# pandashield.net
KiCad netlist of a schematic drawn in EAGLE
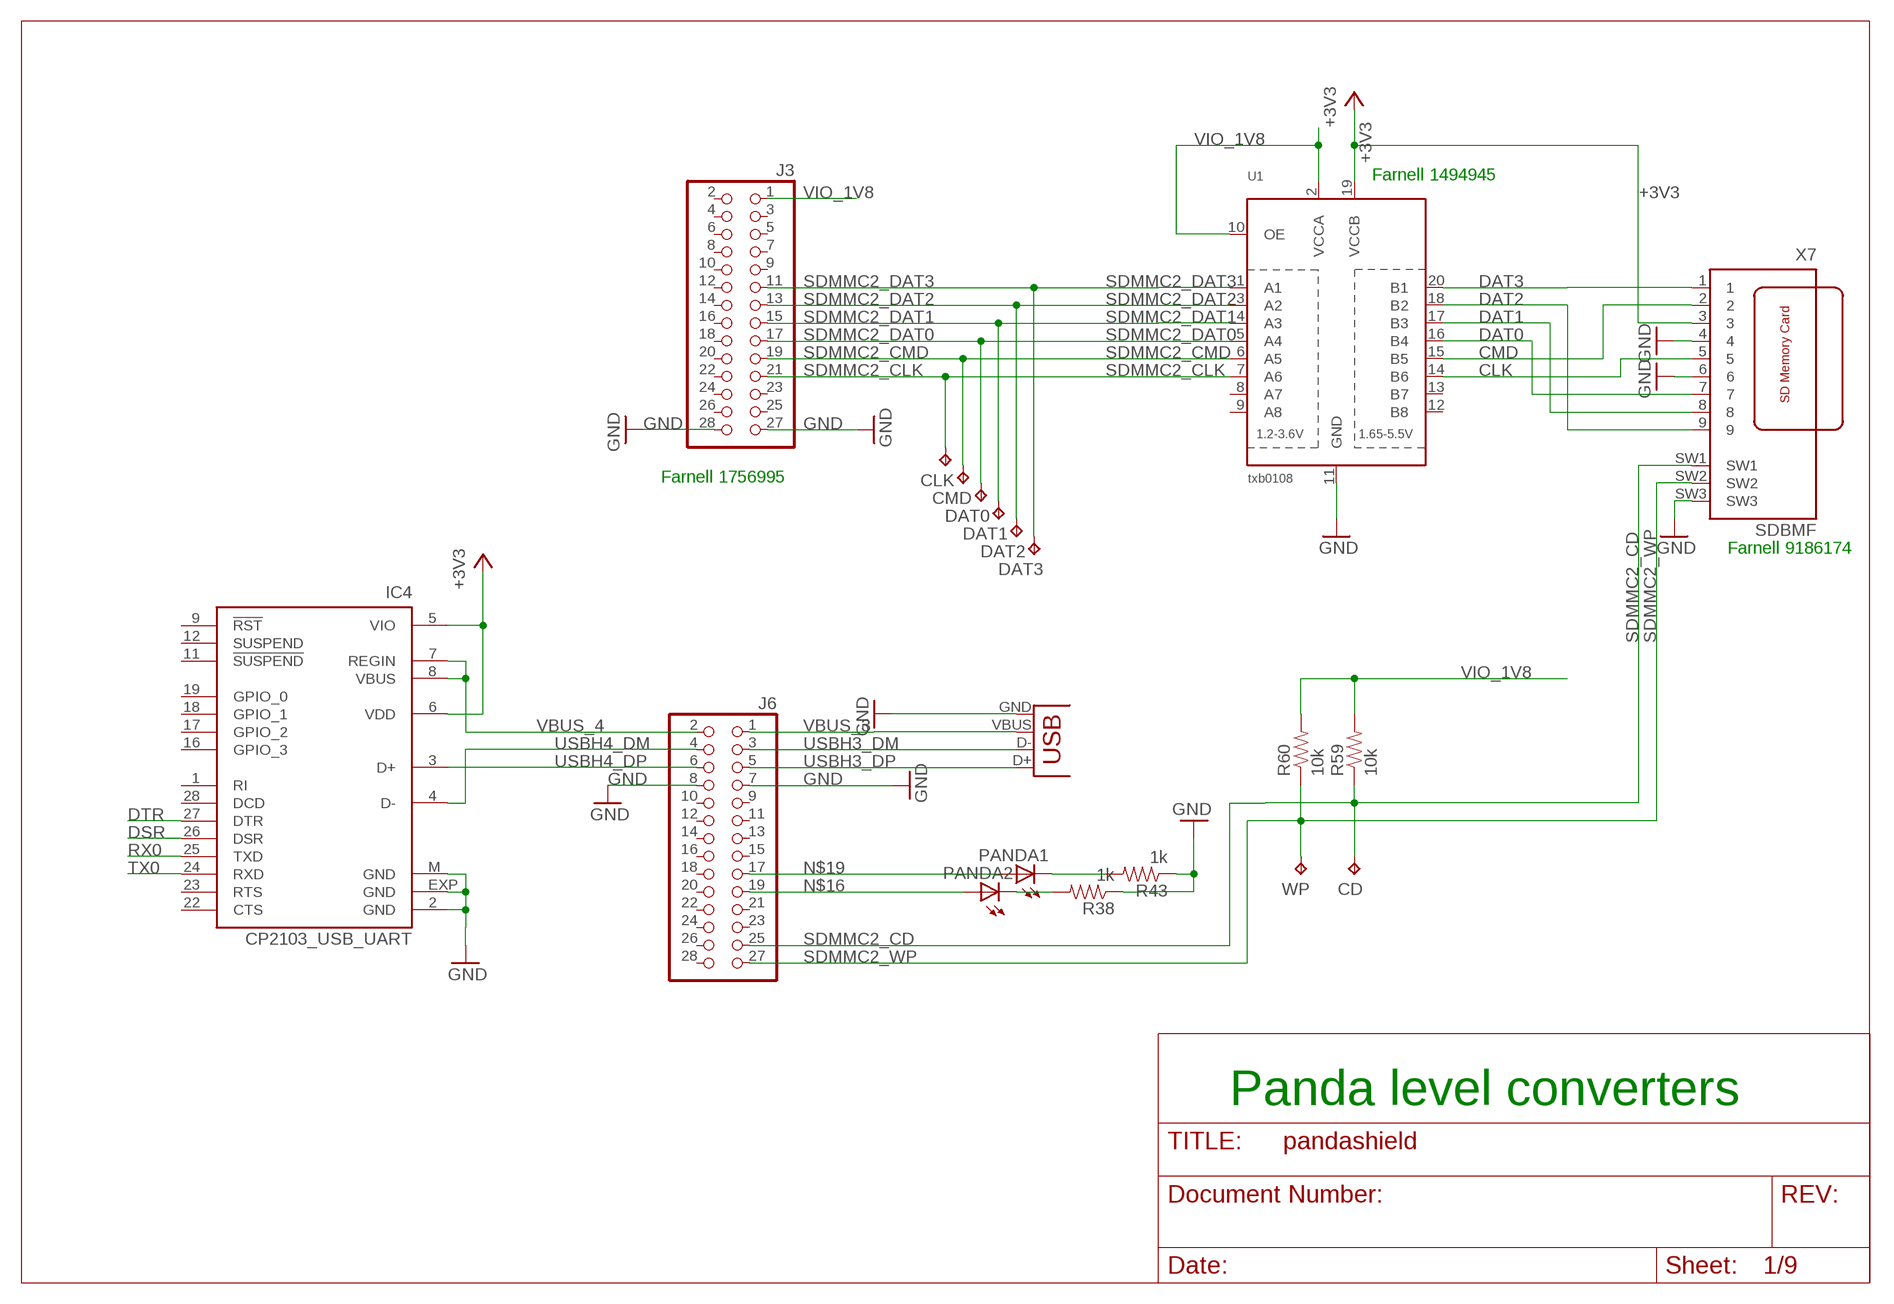
[diagram p0: schematic, sheet 1]
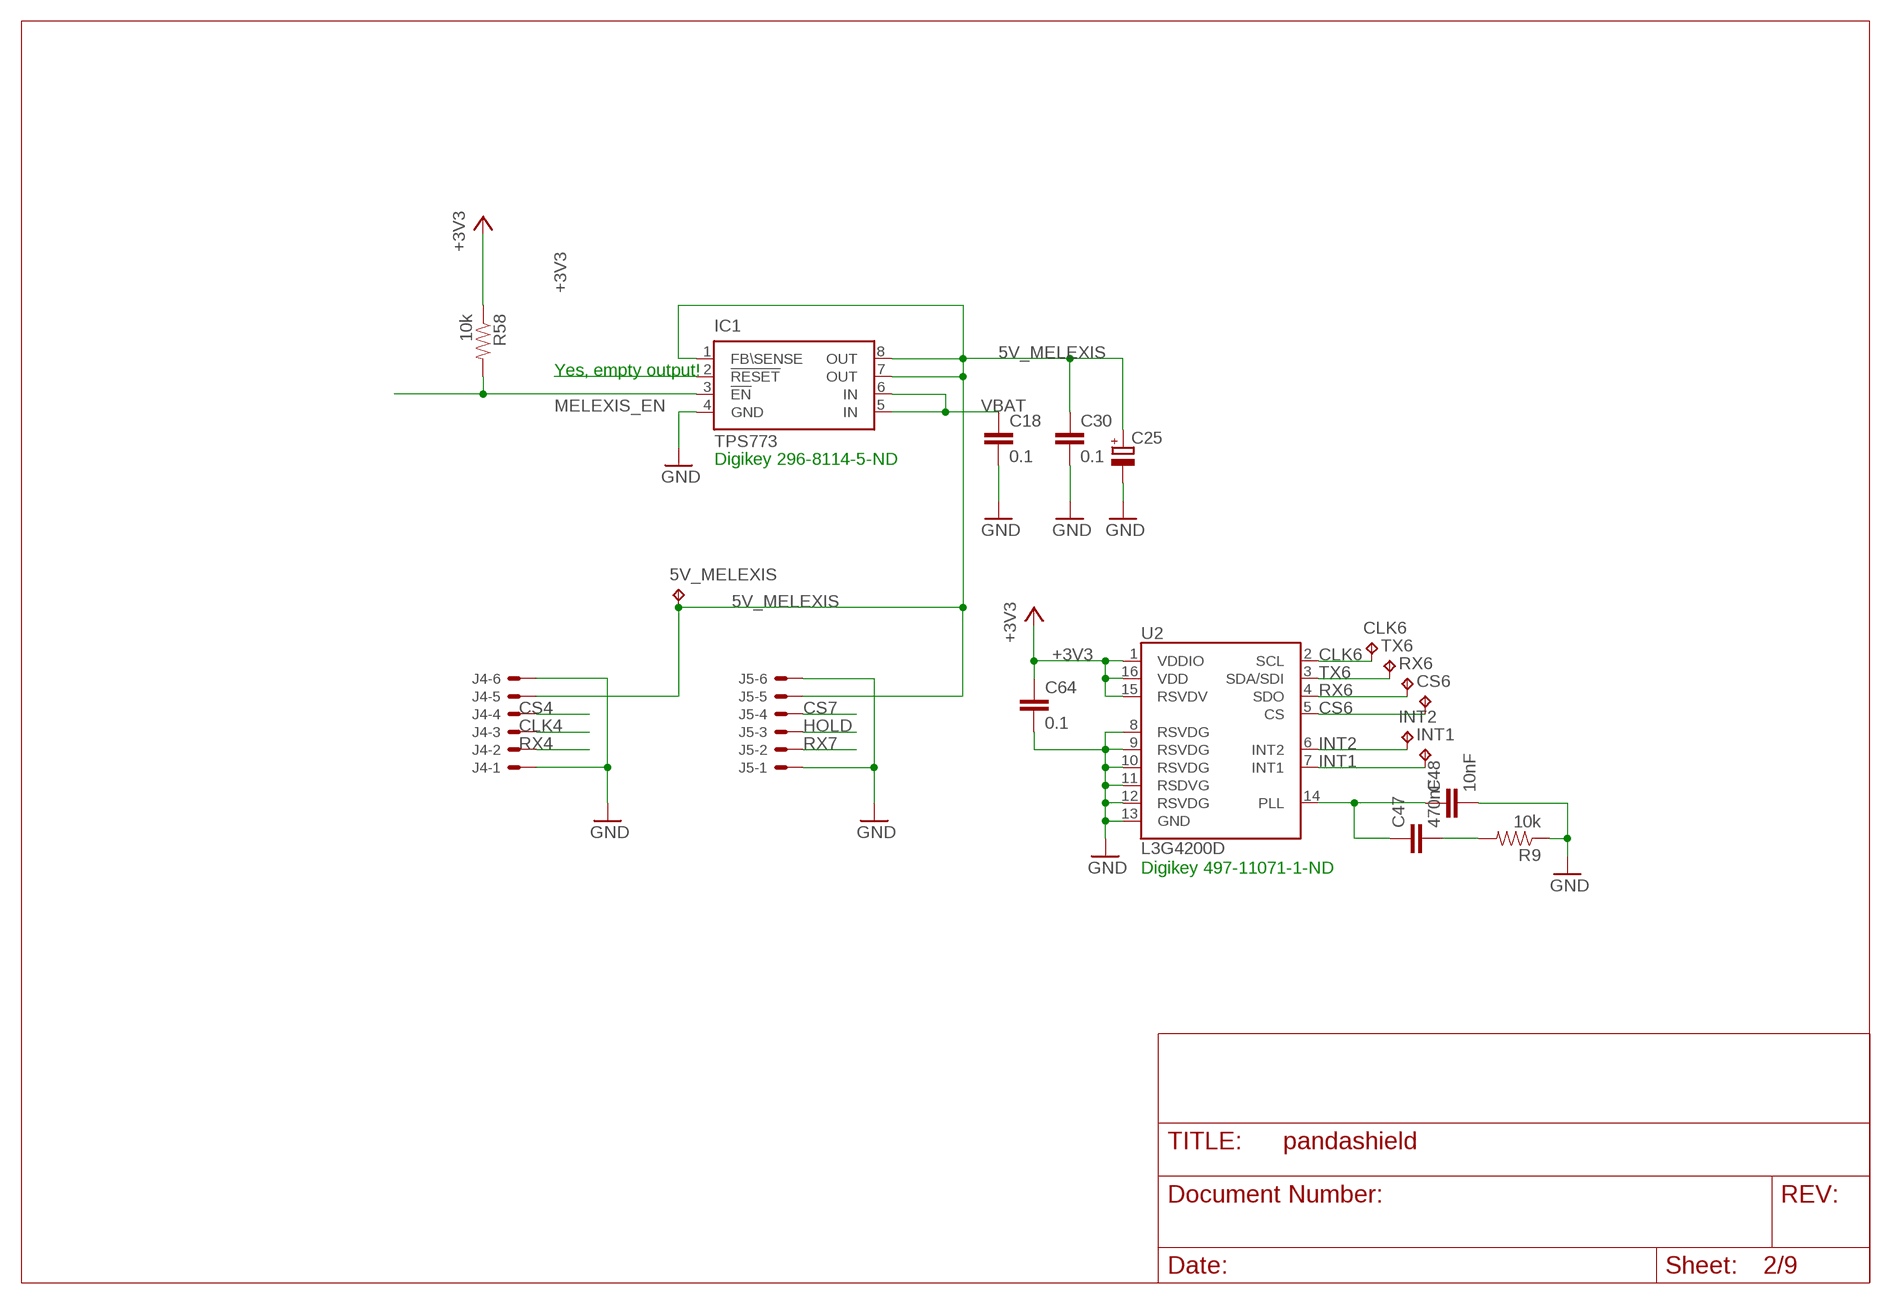
[diagram p1: schematic, sheet 2]
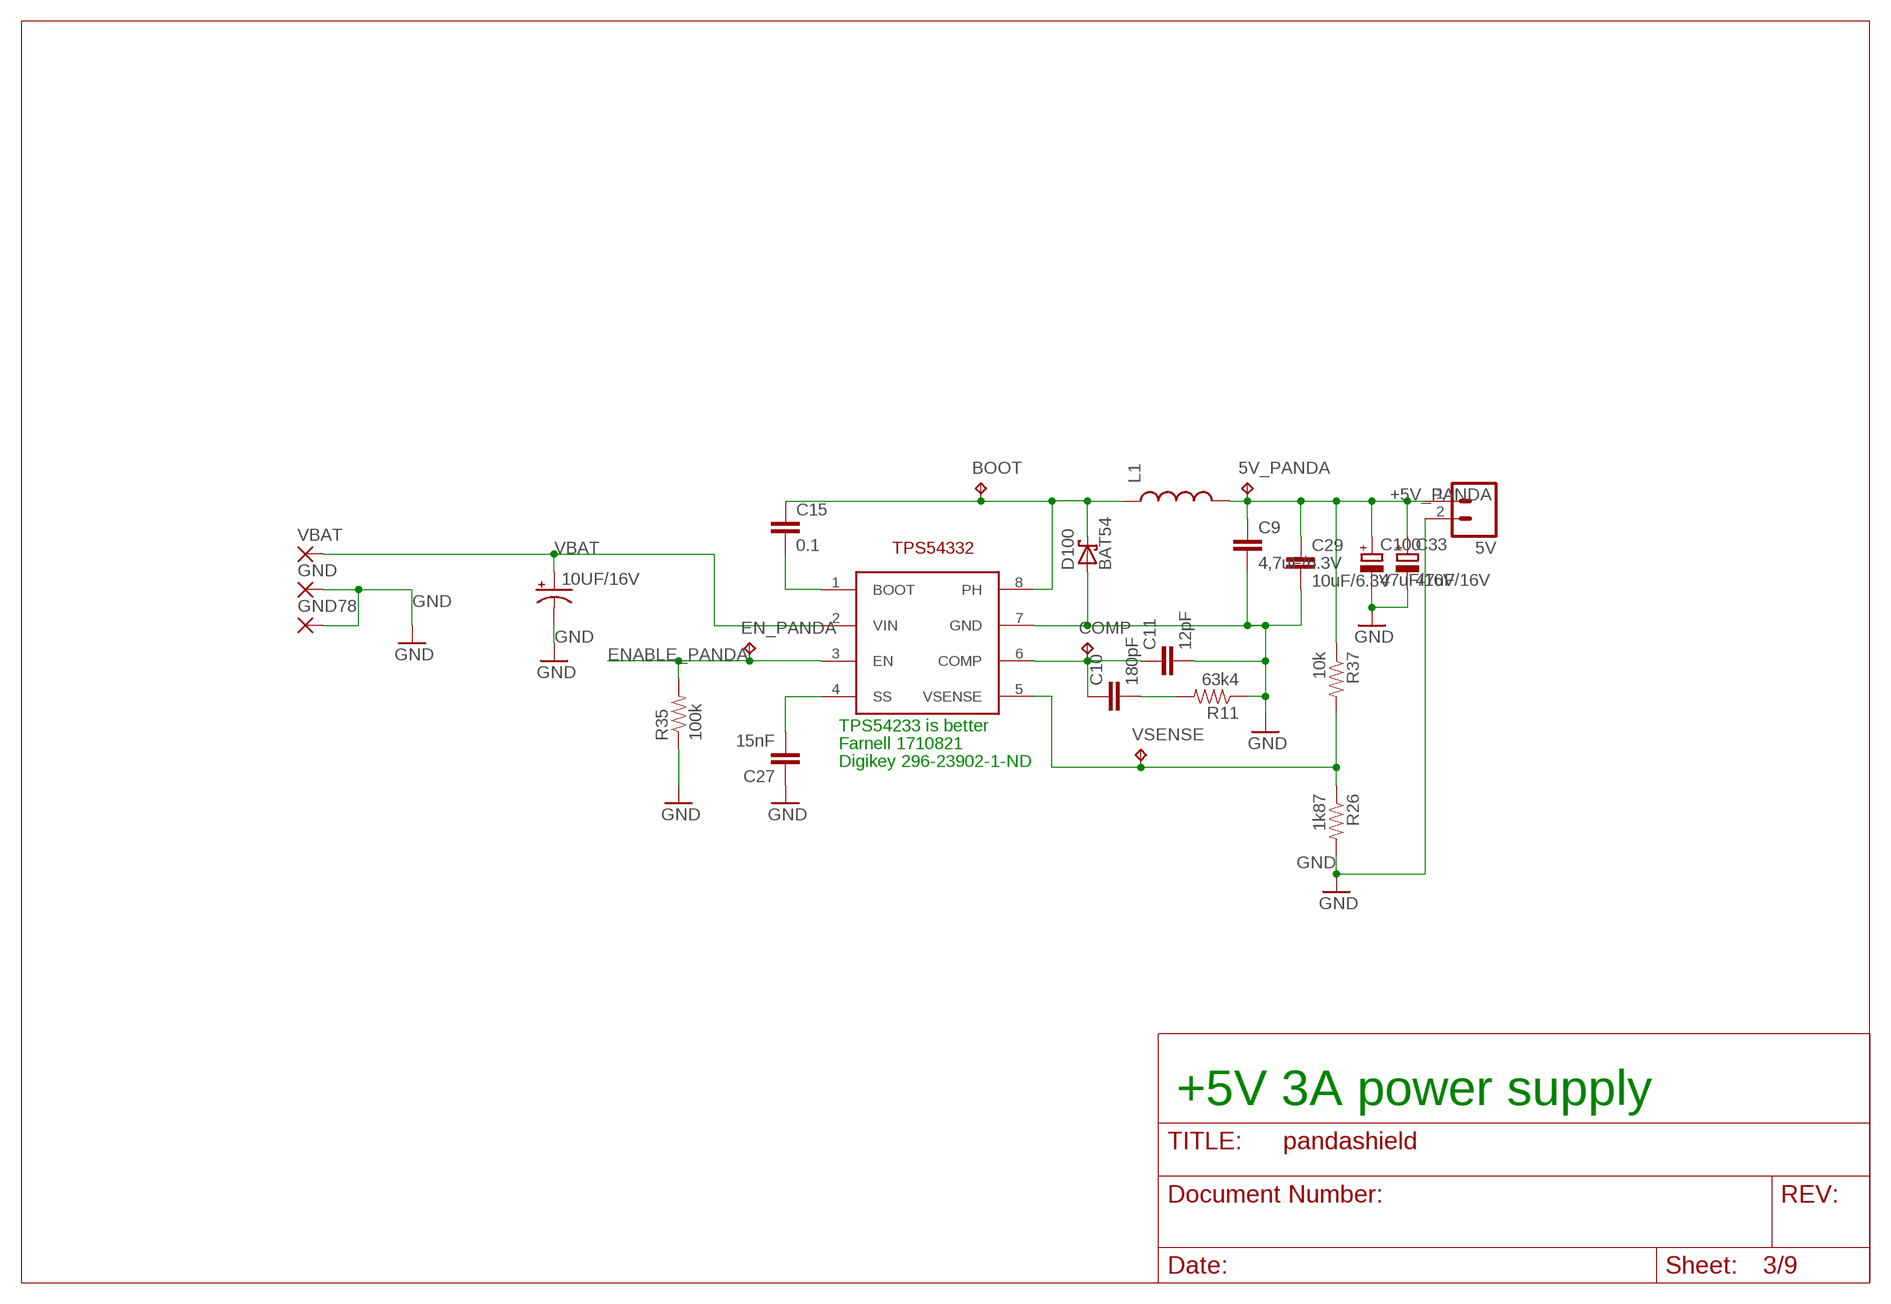
[diagram p2: schematic, sheet 3]
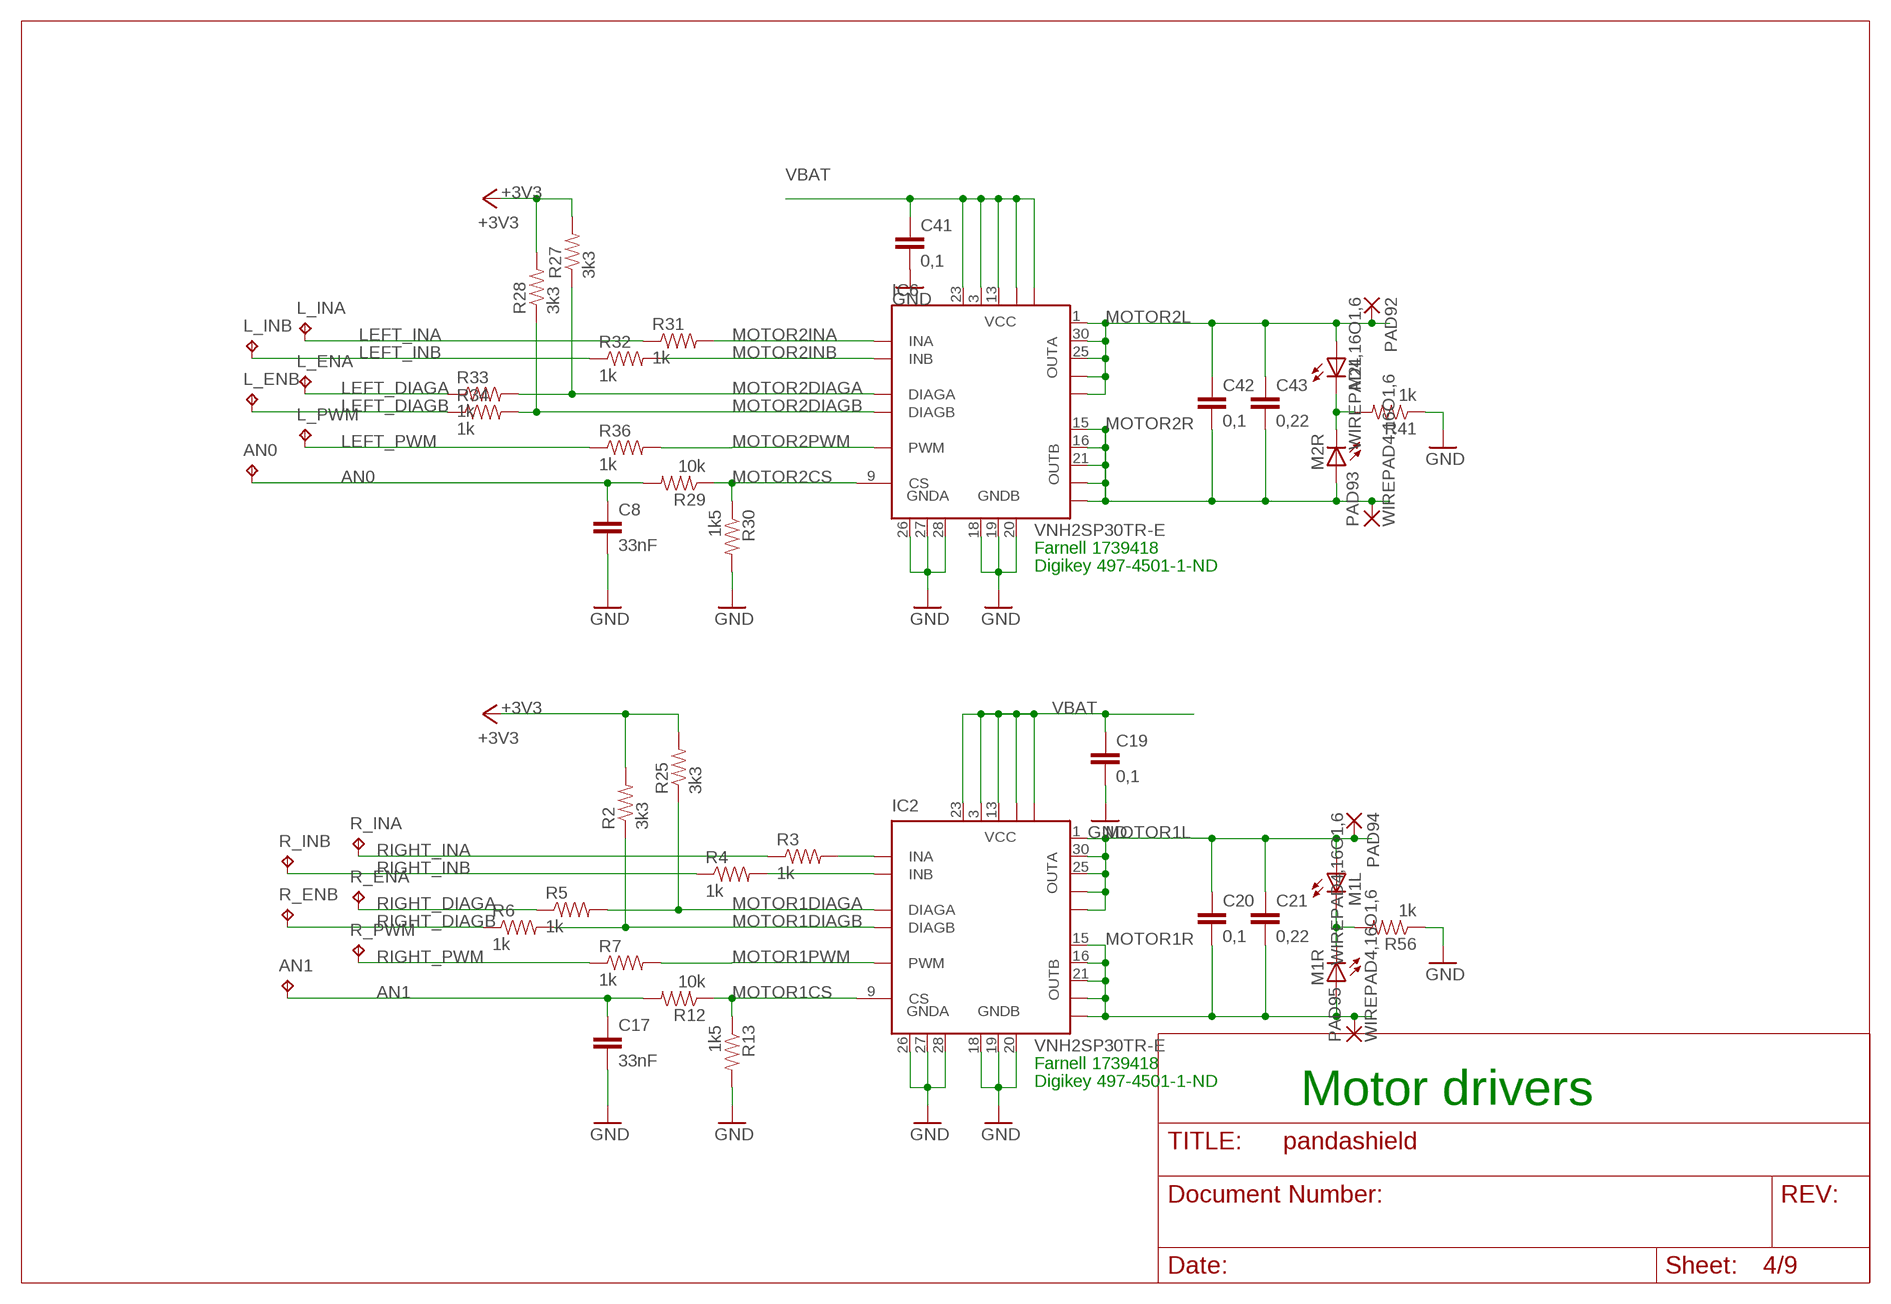
[diagram p3: schematic, sheet 4]
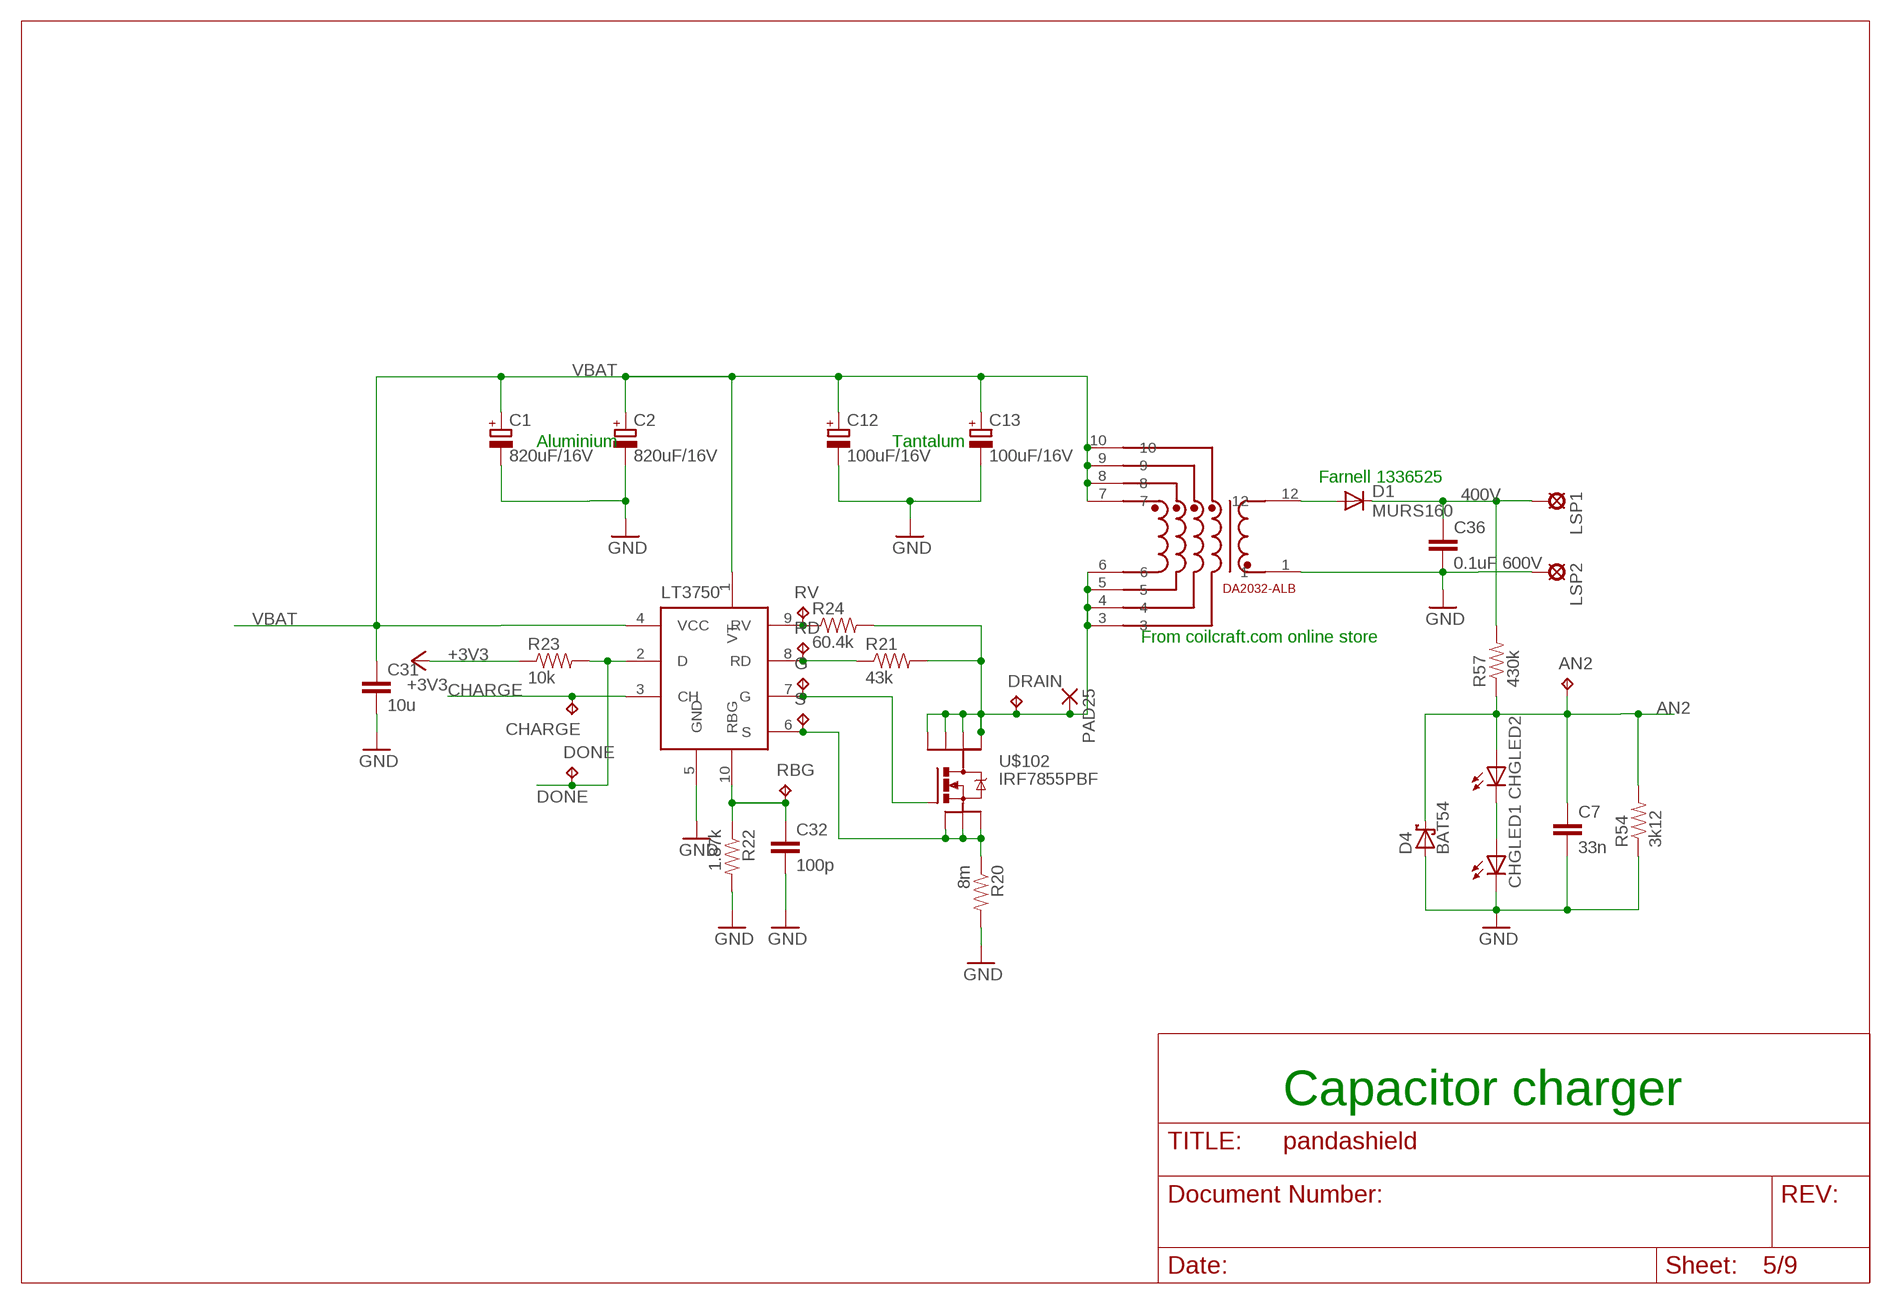
[diagram p4: schematic, sheet 5]
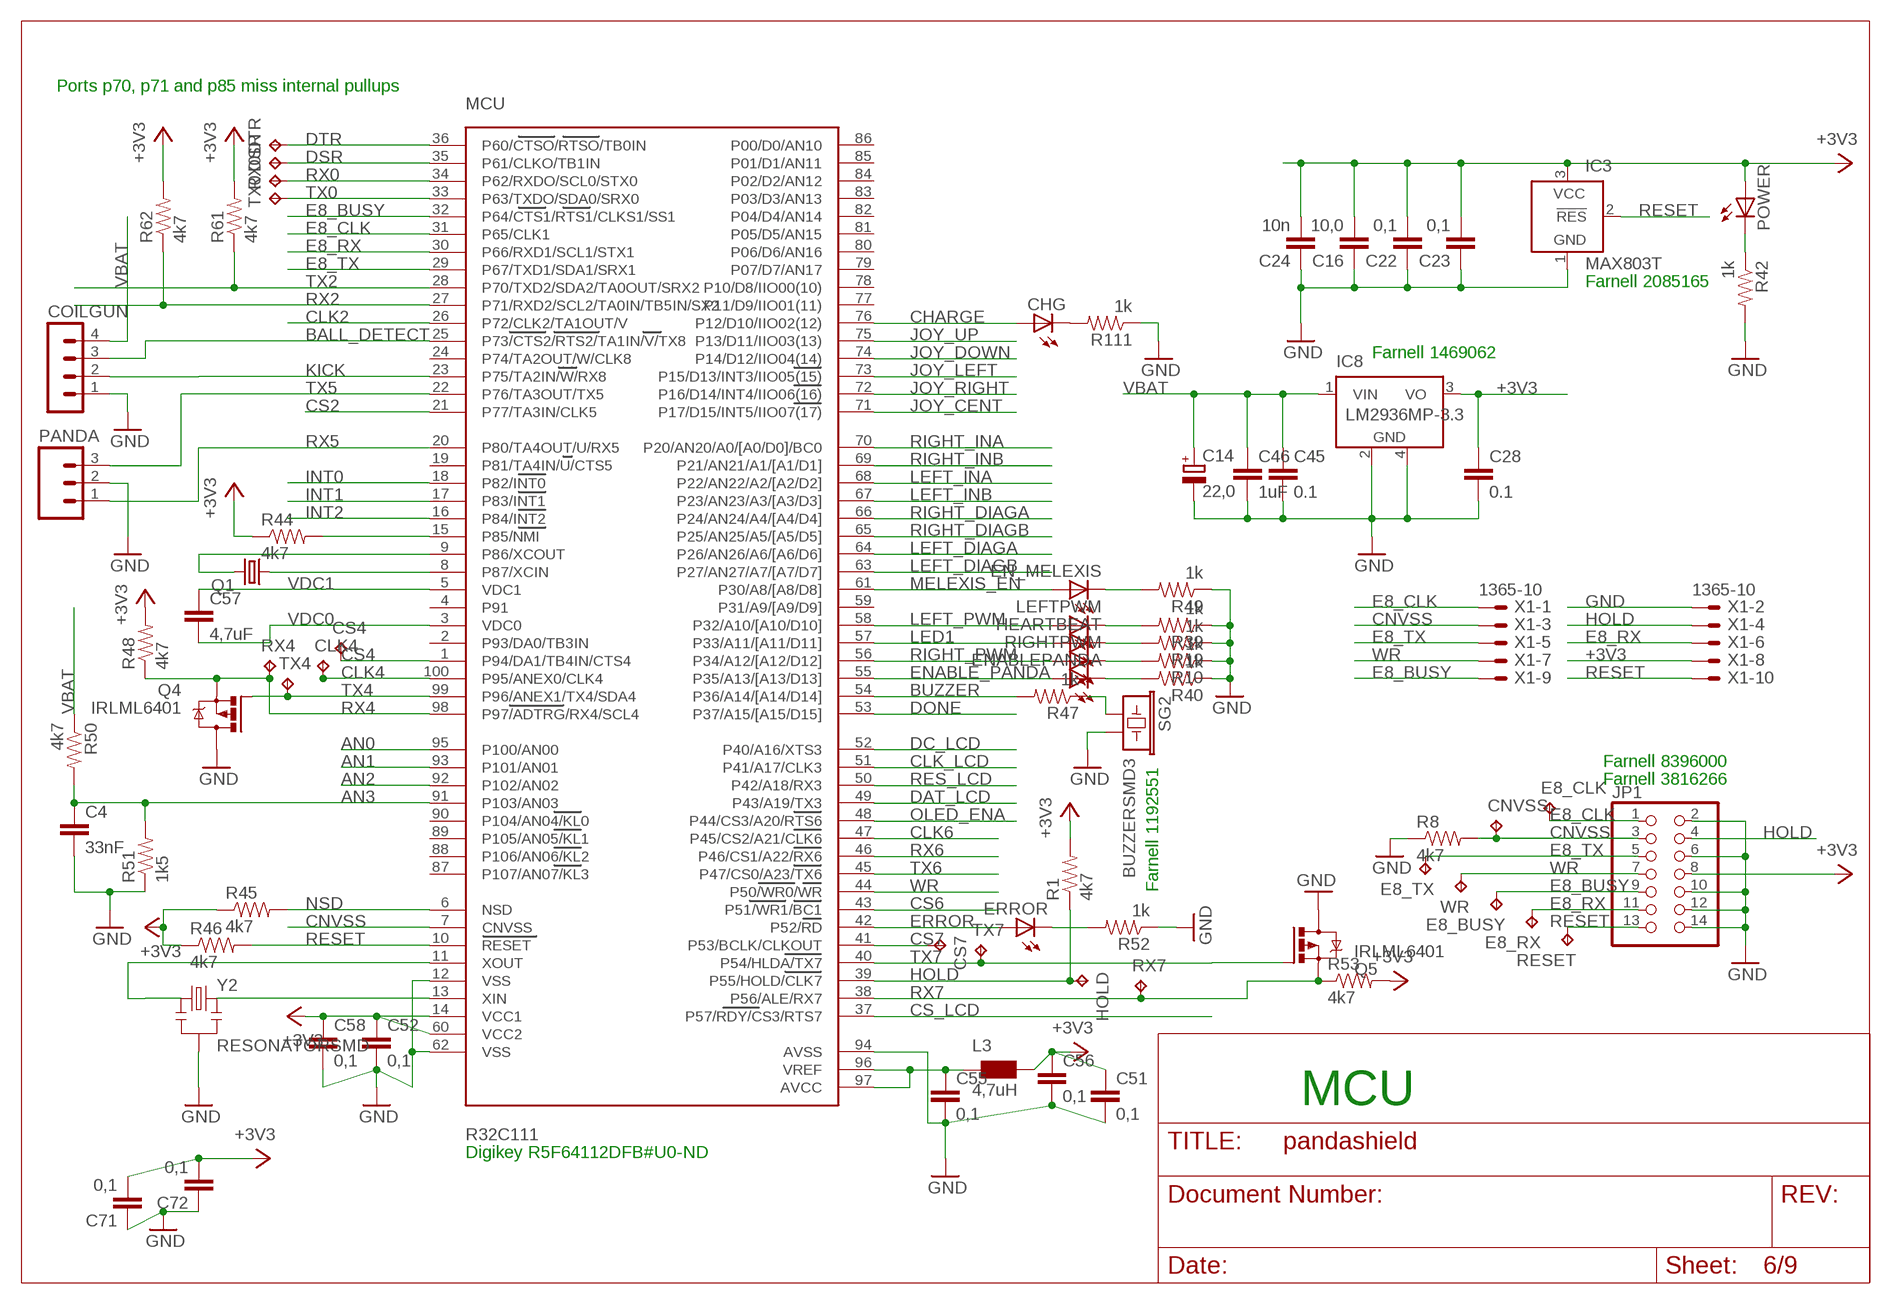
[diagram p5: schematic, sheet 6]
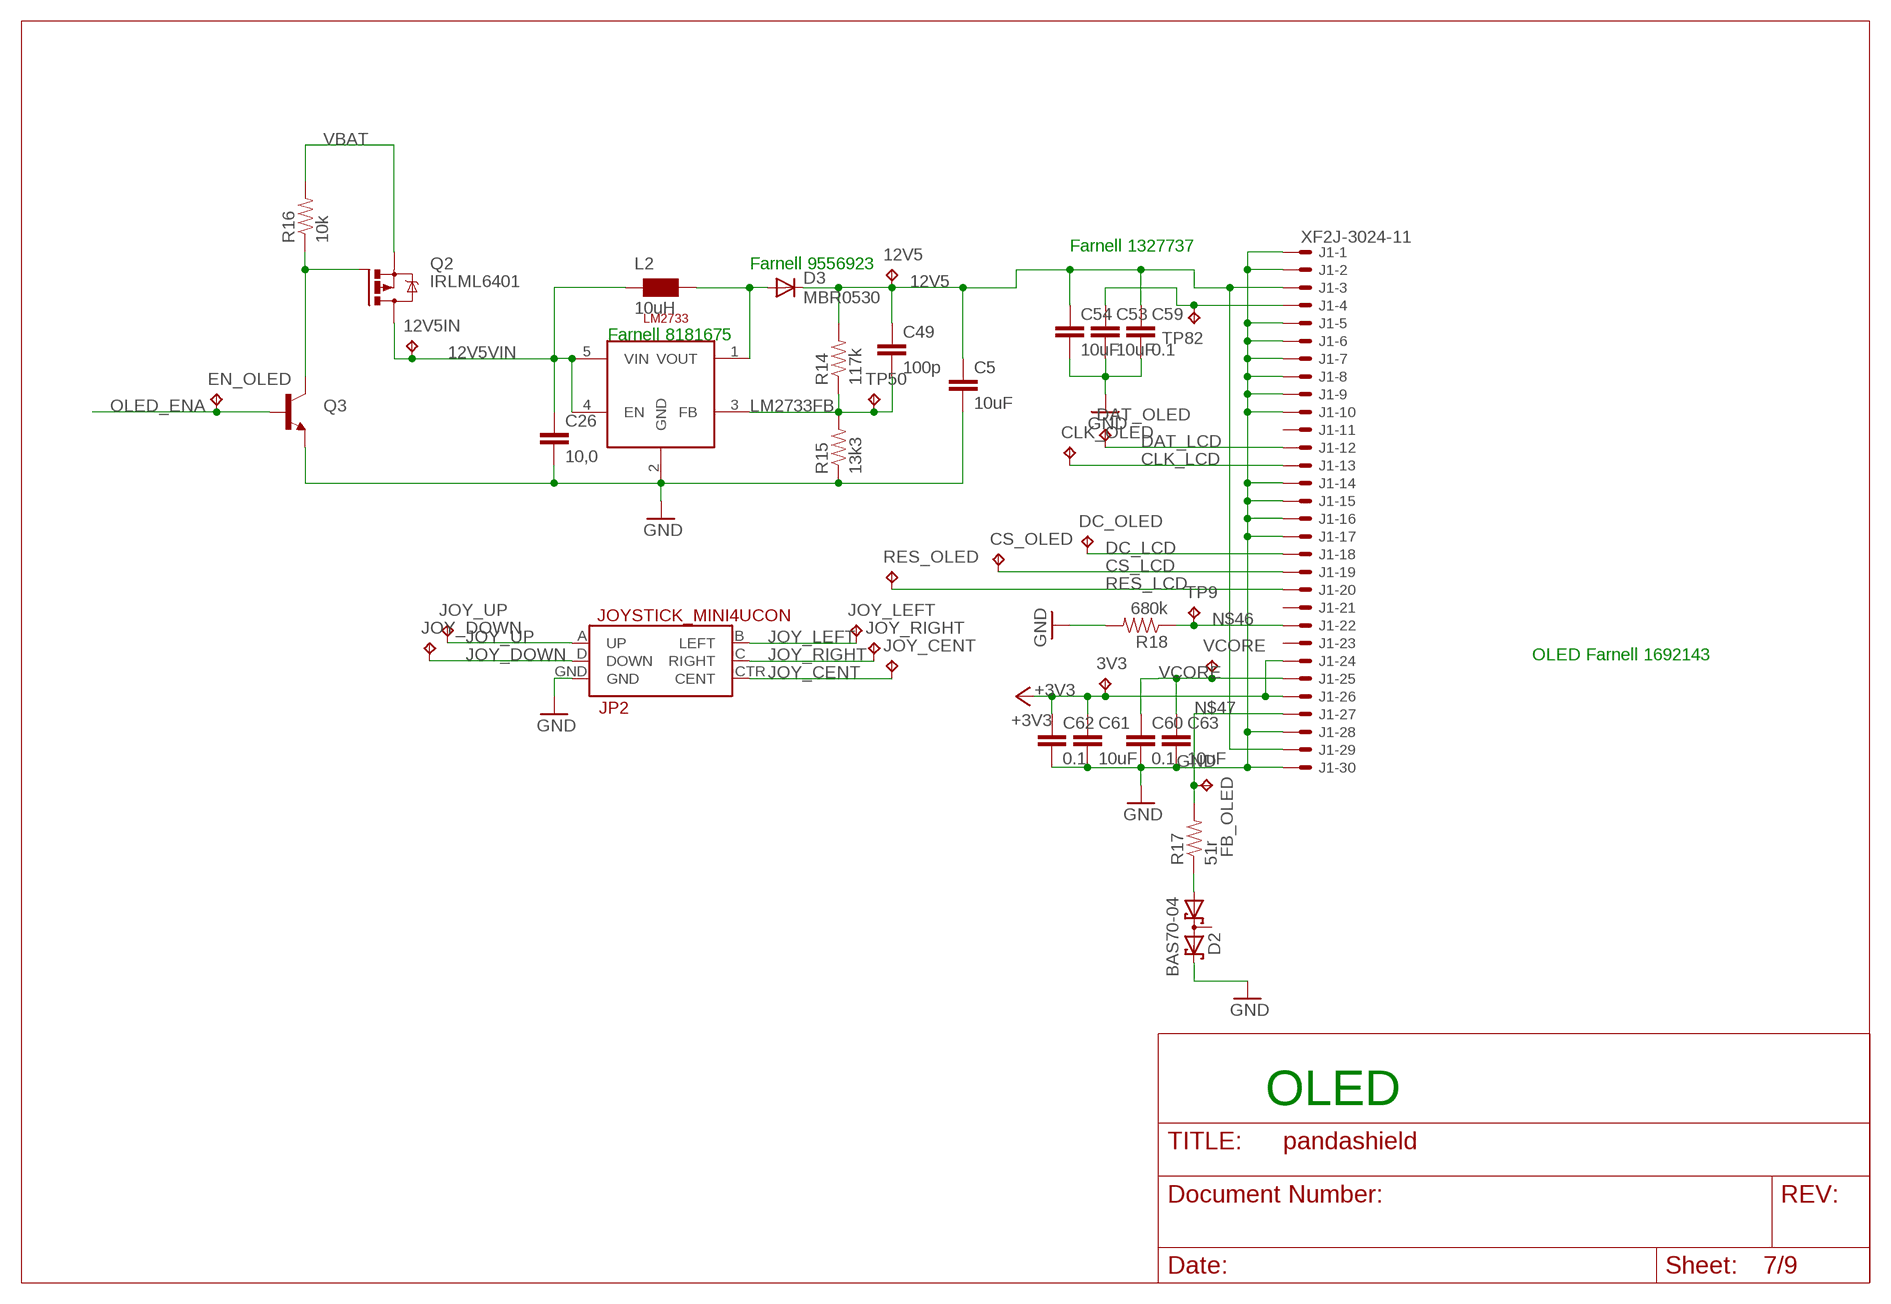
[diagram p6: schematic, sheet 7]
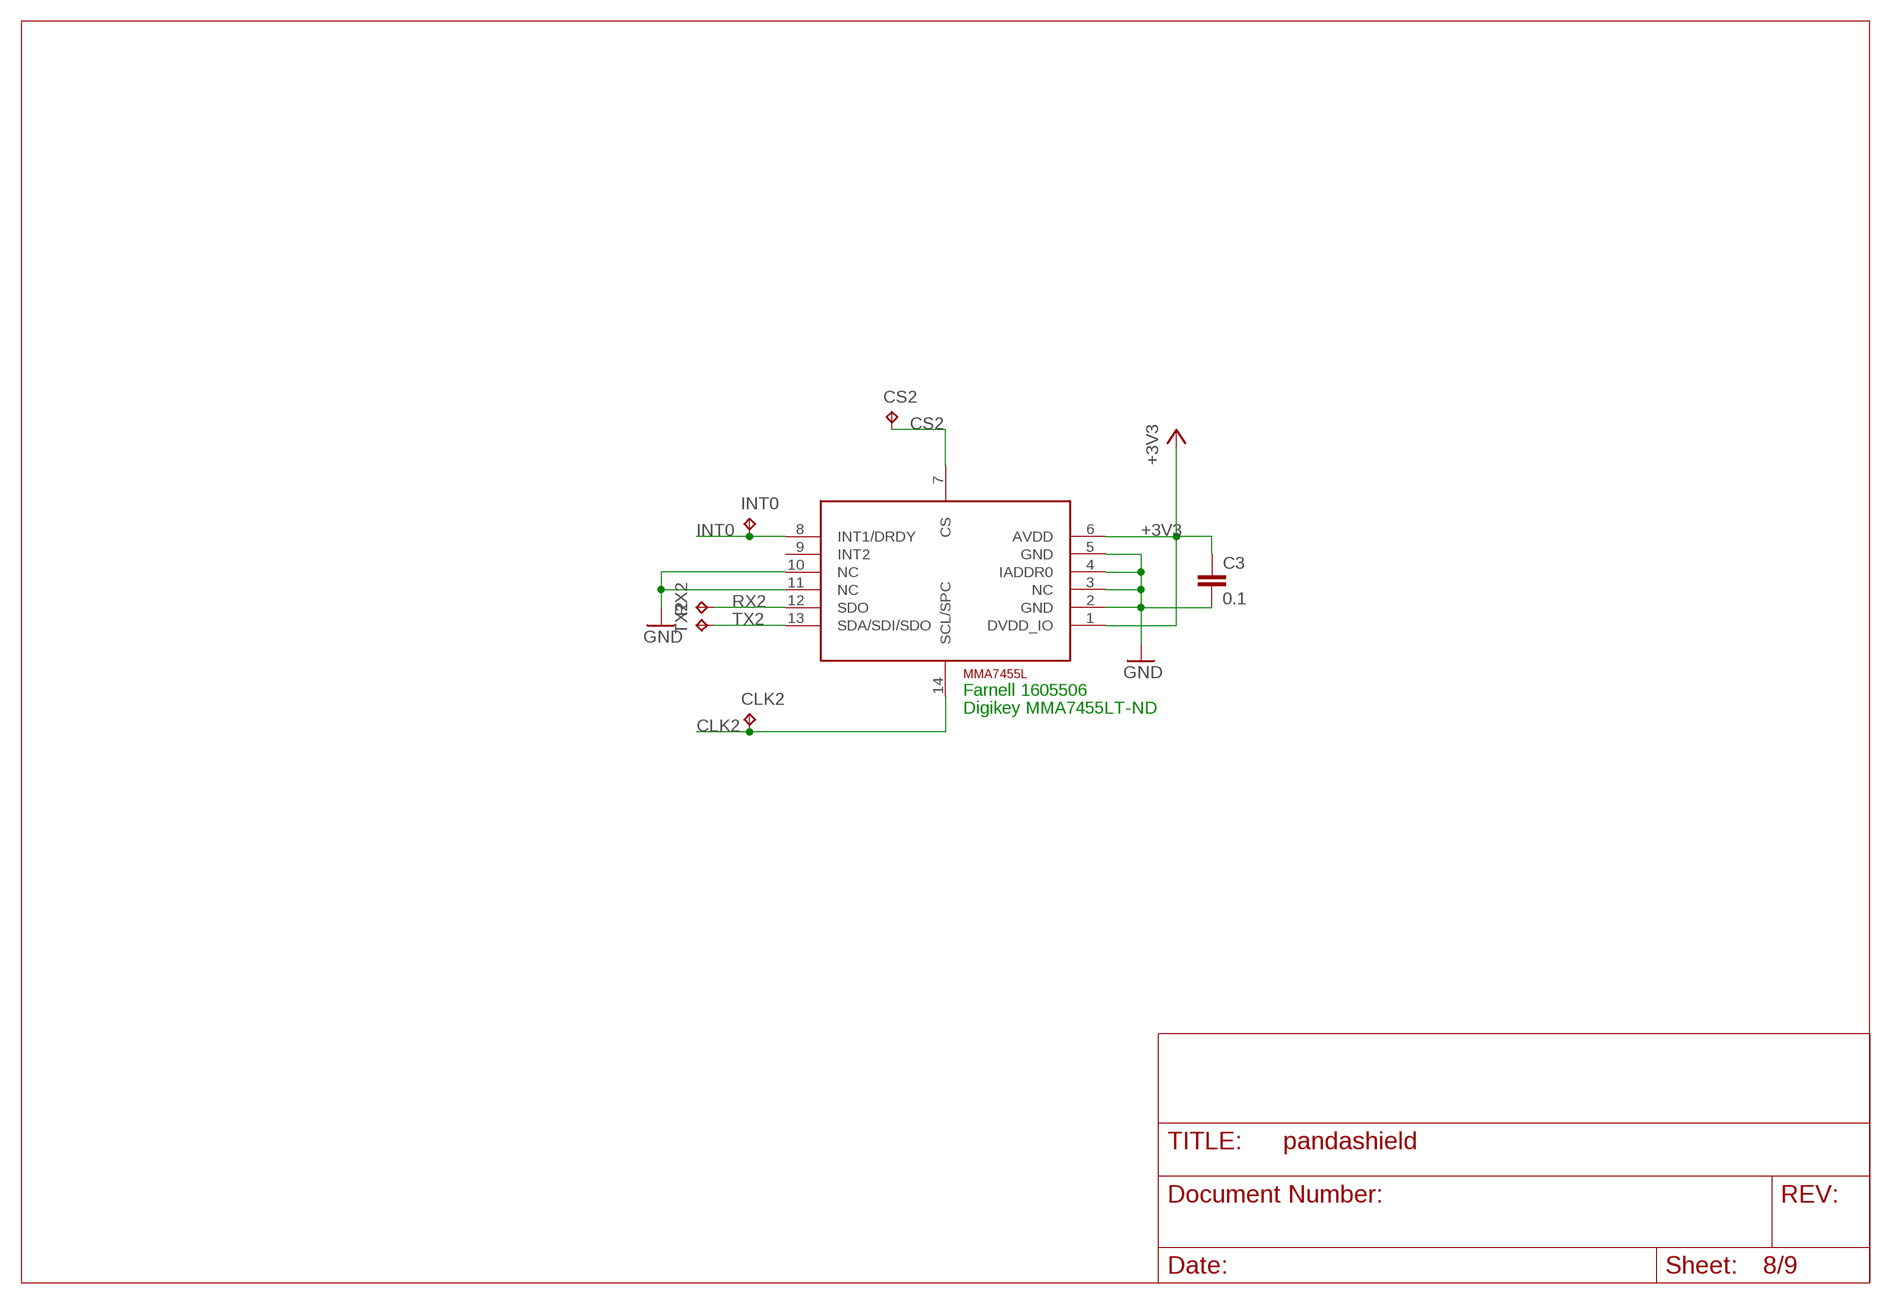
[diagram p7: schematic, sheet 8]
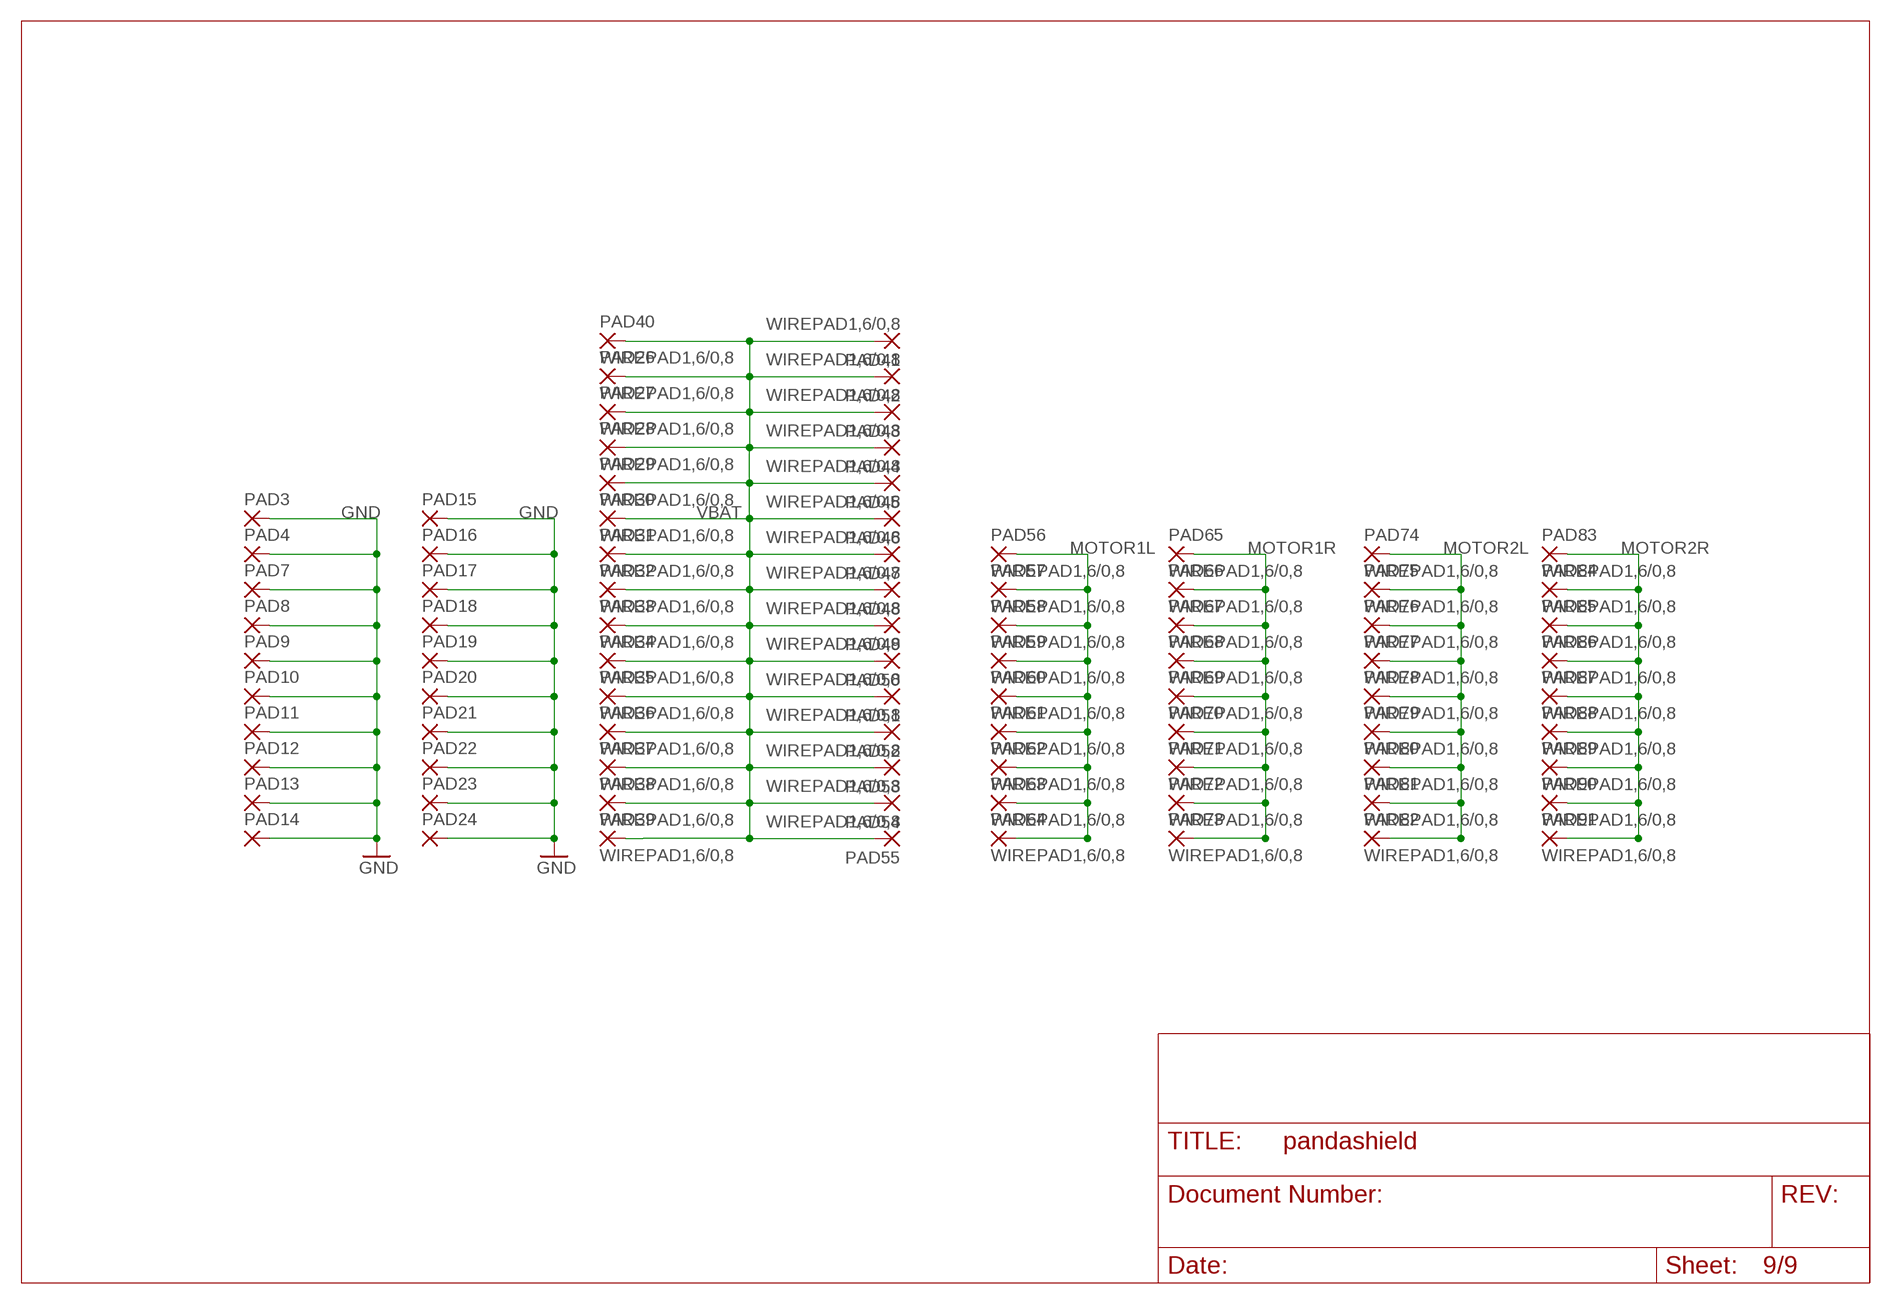
[diagram p8: schematic, sheet 9]

(export (version "E")
  (design (tool "Eeschema 10.0.6"))
  (components
    (comp (ref "AN2")
      (value "TPB1,27")
      (footprint "eagle-import:B1,27")
      (libsource (lib "eagle-import") (part "TPB1,27"))
    )
    (comp (ref "C1")
      (value "820uF/16V")
      (footprint "eagle-import:153CLV-1014")
      (libsource (lib "eagle-import") (part "CPOL-EU153CLV-1014"))
    )
    (comp (ref "C2")
      (value "820uF/16V")
      (footprint "eagle-import:153CLV-1014")
      (libsource (lib "eagle-import") (part "CPOL-EU153CLV-1014"))
    )
    (comp (ref "C7")
      (value "33n")
      (footprint "eagle-import:0603-CAP")
      (libsource (lib "eagle-import") (part "CAP0603-CAP"))
    )
    (comp (ref "C12")
      (value "100uF/16V")
      (footprint "eagle-import:C_6032-28R")
      (libsource (lib "eagle-import") (part "CPOL-EUC/6032-28R"))
    )
    (comp (ref "C13")
      (value "100uF/16V")
      (footprint "eagle-import:C_6032-28R")
      (libsource (lib "eagle-import") (part "CPOL-EUC/6032-28R"))
    )
    (comp (ref "C31")
      (value "10u")
      (footprint "eagle-import:C1210")
      (libsource (lib "eagle-import") (part "C-EUC1210"))
    )
    (comp (ref "C32")
      (value "100p")
      (footprint "eagle-import:0603-CAP")
      (libsource (lib "eagle-import") (part "CAP0603-CAP"))
    )
    (comp (ref "C36")
      (value "0.1uF 600V")
      (footprint "eagle-import:C1812")
      (libsource (lib "eagle-import") (part "C-EUC1812"))
    )
    (comp (ref "CHARGE")
      (value "TPB1,27")
      (footprint "eagle-import:B1,27")
      (libsource (lib "eagle-import") (part "TPB1,27"))
    )
    (comp (ref "CHGLED1")
      (value "LEDCHIPLED_0603")
      (footprint "eagle-import:CHIPLED_0603")
      (libsource (lib "eagle-import") (part "LEDCHIPLED_0603"))
    )
    (comp (ref "CHGLED2")
      (value "LEDCHIPLED_0603")
      (footprint "eagle-import:CHIPLED_0603")
      (libsource (lib "eagle-import") (part "LEDCHIPLED_0603"))
    )
    (comp (ref "D1")
      (value "MURS160")
      (footprint "eagle-import:SMB")
      (libsource (lib "eagle-import") (part "ES2D"))
    )
    (comp (ref "D4")
      (value "BAT54")
      (footprint "eagle-import:SOT23")
      (libsource (lib "eagle-import") (part "BAT54"))
    )
    (comp (ref "DONE")
      (value "TPB1,27")
      (footprint "eagle-import:B1,27")
      (libsource (lib "eagle-import") (part "TPB1,27"))
    )
    (comp (ref "DRAIN")
      (value "TPB1,27")
      (footprint "eagle-import:B1,27")
      (libsource (lib "eagle-import") (part "TPB1,27"))
    )
    (comp (ref "G")
      (value "TPB1,27")
      (footprint "eagle-import:B1,27")
      (libsource (lib "eagle-import") (part "TPB1,27"))
    )
    (comp (ref "LSP1")
      (value "LSP11")
      (footprint "eagle-import:LSP11")
      (libsource (lib "eagle-import") (part "LSP11"))
    )
    (comp (ref "LSP2")
      (value "LSP11")
      (footprint "eagle-import:LSP11")
      (libsource (lib "eagle-import") (part "LSP11"))
    )
    (comp (ref "LT3750")
      (value "LT3750")
      (footprint "eagle-import:MSOP")
      (libsource (lib "eagle-import") (part "LT3750"))
    )
    (comp (ref "PAD25")
      (value "1,6/0,9")
      (footprint "eagle-import:1,6_0,9")
      (libsource (lib "eagle-import") (part "1,6/0,9"))
    )
    (comp (ref "R20")
      (value "8m")
      (footprint "eagle-import:1206")
      (libsource (lib "eagle-import") (part "RESISTOR1206"))
    )
    (comp (ref "R21")
      (value "43k")
      (footprint "eagle-import:0603-RES")
      (libsource (lib "eagle-import") (part "RESISTOR0603-RES"))
    )
    (comp (ref "R22")
      (value "1.87k")
      (footprint "eagle-import:0603-RES")
      (libsource (lib "eagle-import") (part "RESISTOR0603-RES"))
    )
    (comp (ref "R23")
      (value "10k")
      (footprint "eagle-import:0603-RES")
      (libsource (lib "eagle-import") (part "RESISTOR0603-RES"))
    )
    (comp (ref "R24")
      (value "60.4k")
      (footprint "eagle-import:0603-RES")
      (libsource (lib "eagle-import") (part "RESISTOR0603-RES"))
    )
    (comp (ref "R54")
      (value "3k12")
      (footprint "eagle-import:0603-RES")
      (libsource (lib "eagle-import") (part "RESISTOR0603-RES"))
    )
    (comp (ref "R57")
      (value "430k")
      (footprint "eagle-import:1206")
      (libsource (lib "eagle-import") (part "RESISTOR1206"))
    )
    (comp (ref "RBG")
      (value "TPB1,27")
      (footprint "eagle-import:B1,27")
      (libsource (lib "eagle-import") (part "TPB1,27"))
    )
    (comp (ref "RD")
      (value "TPB1,27")
      (footprint "eagle-import:B1,27")
      (libsource (lib "eagle-import") (part "TPB1,27"))
    )
    (comp (ref "RV")
      (value "TPB1,27")
      (footprint "eagle-import:B1,27")
      (libsource (lib "eagle-import") (part "TPB1,27"))
    )
    (comp (ref "S")
      (value "TPB1,27")
      (footprint "eagle-import:B1,27")
      (libsource (lib "eagle-import") (part "TPB1,27"))
    )
    (comp (ref "U$1")
      (value "DA2032-ALBDA2032-ALB")
      (footprint "eagle-import:DA2032-ALB")
      (libsource (lib "eagle-import") (part "DA2032-ALBDA2032-ALB"))
    )
    (comp (ref "U$102")
      (value "IRF7855PBF")
      (footprint "eagle-import:SO8")
      (libsource (lib "eagle-import") (part "IRF8252"))
    )
    (comp (ref "C4")
      (value "33nF")
      (footprint "eagle-import:0603-CAP")
      (libsource (lib "eagle-import") (part "CAP0603-CAP"))
    )
    (comp (ref "C14")
      (value "22,0")
      (footprint "eagle-import:CT3528")
      (libsource (lib "eagle-import") (part "CPOL-EUCT3528"))
    )
    (comp (ref "C16")
      (value "10,0")
      (footprint "eagle-import:1210")
      (libsource (lib "eagle-import") (part "CAP1210"))
    )
    (comp (ref "C22")
      (value "0,1")
      (footprint "eagle-import:0603-CAP")
      (libsource (lib "eagle-import") (part "CAP0603-CAP"))
    )
    (comp (ref "C23")
      (value "0,1")
      (footprint "eagle-import:0603-CAP")
      (libsource (lib "eagle-import") (part "CAP0603-CAP"))
    )
    (comp (ref "C24")
      (value "10n")
      (footprint "eagle-import:0603-CAP")
      (libsource (lib "eagle-import") (part "CAP0603-CAP"))
    )
    (comp (ref "C28")
      (value "0.1")
      (footprint "eagle-import:0603-CAP")
      (libsource (lib "eagle-import") (part "CAP0603-CAP"))
    )
    (comp (ref "C45")
      (value "0.1")
      (footprint "eagle-import:0603-CAP")
      (libsource (lib "eagle-import") (part "CAP0603-CAP"))
    )
    (comp (ref "C46")
      (value "1uF")
      (footprint "eagle-import:0603-CAP")
      (libsource (lib "eagle-import") (part "CAP0603-CAP"))
    )
    (comp (ref "C51")
      (value "0,1")
      (footprint "eagle-import:0603-CAP")
      (libsource (lib "eagle-import") (part "CAP0603-CAP"))
    )
    (comp (ref "C52")
      (value "0,1")
      (footprint "eagle-import:0603-CAP")
      (libsource (lib "eagle-import") (part "CAP0603-CAP"))
    )
    (comp (ref "C55")
      (value "0,1")
      (footprint "eagle-import:0603-CAP")
      (libsource (lib "eagle-import") (part "CAP0603-CAP"))
    )
    (comp (ref "C56")
      (value "0,1")
      (footprint "eagle-import:0603-CAP")
      (libsource (lib "eagle-import") (part "CAP0603-CAP"))
    )
    (comp (ref "C57")
      (value "4,7uF")
      (footprint "eagle-import:0805")
      (libsource (lib "eagle-import") (part "CAP0805"))
    )
    (comp (ref "C58")
      (value "0,1")
      (footprint "eagle-import:0603-CAP")
      (libsource (lib "eagle-import") (part "CAP0603-CAP"))
    )
    (comp (ref "C71")
      (value "0,1")
      (footprint "eagle-import:0603-CAP")
      (libsource (lib "eagle-import") (part "CAP0603-CAP"))
    )
    (comp (ref "C72")
      (value "0,1")
      (footprint "eagle-import:0603-CAP")
      (libsource (lib "eagle-import") (part "CAP0603-CAP"))
    )
    (comp (ref "CHG")
      (value "LED0603")
      (footprint "eagle-import:LED-0603")
      (libsource (lib "eagle-import") (part "LED0603"))
    )
    (comp (ref "CLK4")
      (value "TPB1,27")
      (footprint "eagle-import:B1,27")
      (libsource (lib "eagle-import") (part "TPB1,27"))
    )
    (comp (ref "CNVSS")
      (value "TPB1,27")
      (footprint "eagle-import:B1,27")
      (libsource (lib "eagle-import") (part "TPB1,27"))
    )
    (comp (ref "COILGUN")
      (value "MA04-1")
      (footprint "eagle-import:MA04-1")
      (libsource (lib "eagle-import") (part "MA04-1"))
    )
    (comp (ref "CS4")
      (value "TPB1,27")
      (footprint "eagle-import:B1,27")
      (libsource (lib "eagle-import") (part "TPB1,27"))
    )
    (comp (ref "CS7")
      (value "TPB1,27")
      (footprint "eagle-import:B1,27")
      (libsource (lib "eagle-import") (part "TPB1,27"))
    )
    (comp (ref "DSR")
      (value "TPB1,27")
      (footprint "eagle-import:B1,27")
      (libsource (lib "eagle-import") (part "TPB1,27"))
    )
    (comp (ref "DTR")
      (value "TPB1,27")
      (footprint "eagle-import:B1,27")
      (libsource (lib "eagle-import") (part "TPB1,27"))
    )
    (comp (ref "E8_BUSY")
      (value "TPB1,27")
      (footprint "eagle-import:B1,27")
      (libsource (lib "eagle-import") (part "TPB1,27"))
    )
    (comp (ref "E8_CLK")
      (value "TPB1,27")
      (footprint "eagle-import:B1,27")
      (libsource (lib "eagle-import") (part "TPB1,27"))
    )
    (comp (ref "E8_RX")
      (value "TPB1,27")
      (footprint "eagle-import:B1,27")
      (libsource (lib "eagle-import") (part "TPB1,27"))
    )
    (comp (ref "E8_TX")
      (value "TPB1,27")
      (footprint "eagle-import:B1,27")
      (libsource (lib "eagle-import") (part "TPB1,27"))
    )
    (comp (ref "ENABLEPANDA")
      (value "LED0603")
      (footprint "eagle-import:LED-0603")
      (libsource (lib "eagle-import") (part "LED0603"))
    )
    (comp (ref "EN_MELEXIS")
      (value "LED0603")
      (footprint "eagle-import:LED-0603")
      (libsource (lib "eagle-import") (part "LED0603"))
    )
    (comp (ref "ERROR")
      (value "LED0603")
      (footprint "eagle-import:LED-0603")
      (libsource (lib "eagle-import") (part "LED0603"))
    )
    (comp (ref "HEARTBEAT")
      (value "LED0603")
      (footprint "eagle-import:LED-0603")
      (libsource (lib "eagle-import") (part "LED0603"))
    )
    (comp (ref "HOLD")
      (value "TPB1,27")
      (footprint "eagle-import:B1,27")
      (libsource (lib "eagle-import") (part "TPB1,27"))
    )
    (comp (ref "IC3")
      (value "MAX803T")
      (footprint "eagle-import:SOT23B-3")
      (fields (field (name "MF") "MICROCHIP") (field (name "MPN") "TCM809MENB713"))
      (libsource (lib "eagle-import") (part "TCM809"))
    )
    (comp (ref "IC8")
      (value "LM2936MP-3.3")
      (footprint "eagle-import:SOT223")
      (fields (field (name "MF") "NATIONAL SEMICONDUCTOR") (field (name "MPN") "LM2936MP-3.0/NOPB"))
      (libsource (lib "eagle-import") (part "LM2936MP?-3.0"))
    )
    (comp (ref "JP1")
      (value "PINHD-2X7")
      (footprint "eagle-import:2X07")
      (libsource (lib "eagle-import") (part "PINHD-2X7"))
    )
    (comp (ref "L3")
      (value "4,7uH")
      (footprint "eagle-import:WE-KI_0805_B")
      (libsource (lib "eagle-import") (part "WE-KIHQ_0805"))
    )
    (comp (ref "LEFTPWM")
      (value "LED0603")
      (footprint "eagle-import:LED-0603")
      (libsource (lib "eagle-import") (part "LED0603"))
    )
    (comp (ref "MCU")
      (value "R32C111")
      (footprint "eagle-import:100P6Q-A")
      (libsource (lib "eagle-import") (part "R32C111"))
    )
    (comp (ref "PANDA")
      (value "MA03")
      (footprint "eagle-import:03P")
      (libsource (lib "eagle-import") (part "MA03"))
    )
    (comp (ref "POWER")
      (value "LED0603")
      (footprint "eagle-import:LED-0603")
      (libsource (lib "eagle-import") (part "LED0603"))
    )
    (comp (ref "Q1")
      (value "CRYSTALMM20SS")
      (footprint "eagle-import:MM20SS")
      (libsource (lib "eagle-import") (part "CRYSTALMM20SS"))
    )
    (comp (ref "Q4")
      (value "IRLML6401")
      (footprint "eagle-import:MICRO3")
      (libsource (lib "eagle-import") (part "IRLML5203"))
    )
    (comp (ref "Q5")
      (value "IRLML6401")
      (footprint "eagle-import:MICRO3")
      (libsource (lib "eagle-import") (part "IRLML5203"))
    )
    (comp (ref "R1")
      (value "4k7")
      (footprint "eagle-import:0603-RES")
      (libsource (lib "eagle-import") (part "RESISTOR0603-RES"))
    )
    (comp (ref "R8")
      (value "4k7")
      (footprint "eagle-import:0603-RES")
      (libsource (lib "eagle-import") (part "RESISTOR0603-RES"))
    )
    (comp (ref "R10")
      (value "1k")
      (footprint "eagle-import:0603-RES")
      (libsource (lib "eagle-import") (part "RESISTOR0603-RES"))
    )
    (comp (ref "R19")
      (value "1k")
      (footprint "eagle-import:0603-RES")
      (libsource (lib "eagle-import") (part "RESISTOR0603-RES"))
    )
    (comp (ref "R39")
      (value "1k")
      (footprint "eagle-import:0603-RES")
      (libsource (lib "eagle-import") (part "RESISTOR0603-RES"))
    )
    (comp (ref "R40")
      (value "1k")
      (footprint "eagle-import:0603-RES")
      (libsource (lib "eagle-import") (part "RESISTOR0603-RES"))
    )
    (comp (ref "R42")
      (value "1k")
      (footprint "eagle-import:0603-RES")
      (libsource (lib "eagle-import") (part "RESISTOR0603-RES"))
    )
    (comp (ref "R44")
      (value "4k7")
      (footprint "eagle-import:0603-RES")
      (libsource (lib "eagle-import") (part "RESISTOR0603-RES"))
    )
    (comp (ref "R45")
      (value "4k7")
      (footprint "eagle-import:0603-RES")
      (libsource (lib "eagle-import") (part "RESISTOR0603-RES"))
    )
    (comp (ref "R46")
      (value "4k7")
      (footprint "eagle-import:0603-RES")
      (libsource (lib "eagle-import") (part "RESISTOR0603-RES"))
    )
    (comp (ref "R47")
      (value "1k")
      (footprint "eagle-import:0603-RES")
      (libsource (lib "eagle-import") (part "RESISTOR0603-RES"))
    )
    (comp (ref "R48")
      (value "4k7")
      (footprint "eagle-import:0603-RES")
      (libsource (lib "eagle-import") (part "RESISTOR0603-RES"))
    )
    (comp (ref "R49")
      (value "1k")
      (footprint "eagle-import:0603-RES")
      (libsource (lib "eagle-import") (part "RESISTOR0603-RES"))
    )
    (comp (ref "R50")
      (value "4k7")
      (footprint "eagle-import:0603-RES")
      (libsource (lib "eagle-import") (part "RESISTOR0603-RES"))
    )
    (comp (ref "R51")
      (value "1k5")
      (footprint "eagle-import:0603-RES")
      (libsource (lib "eagle-import") (part "RESISTOR0603-RES"))
    )
    (comp (ref "R52")
      (value "1k")
      (footprint "eagle-import:0603-RES")
      (libsource (lib "eagle-import") (part "RESISTOR0603-RES"))
    )
    (comp (ref "R53")
      (value "4k7")
      (footprint "eagle-import:0603-RES")
      (libsource (lib "eagle-import") (part "RESISTOR0603-RES"))
    )
    (comp (ref "R61")
      (value "4k7")
      (footprint "eagle-import:0603-RES")
      (libsource (lib "eagle-import") (part "RESISTOR0603-RES"))
    )
    (comp (ref "R62")
      (value "4k7")
      (footprint "eagle-import:0603-RES")
      (libsource (lib "eagle-import") (part "RESISTOR0603-RES"))
    )
    (comp (ref "R111")
      (value "1k")
      (footprint "eagle-import:0603-RES")
      (libsource (lib "eagle-import") (part "RESISTOR0603-RES"))
    )
    (comp (ref "RESET")
      (value "TPB1,27")
      (footprint "eagle-import:B1,27")
      (libsource (lib "eagle-import") (part "TPB1,27"))
    )
    (comp (ref "RIGHTPWM")
      (value "LED0603")
      (footprint "eagle-import:LED-0603")
      (libsource (lib "eagle-import") (part "LED0603"))
    )
    (comp (ref "RX0")
      (value "TPB1,27")
      (footprint "eagle-import:B1,27")
      (libsource (lib "eagle-import") (part "TPB1,27"))
    )
    (comp (ref "RX4")
      (value "TPB1,27")
      (footprint "eagle-import:B1,27")
      (libsource (lib "eagle-import") (part "TPB1,27"))
    )
    (comp (ref "RX7")
      (value "TPB1,27")
      (footprint "eagle-import:B1,27")
      (libsource (lib "eagle-import") (part "TPB1,27"))
    )
    (comp (ref "SG2")
      (value "BUZZERSMD3")
      (footprint "eagle-import:BUZZER-CMT1102")
      (libsource (lib "eagle-import") (part "BUZZERSMD3"))
    )
    (comp (ref "TX0")
      (value "TPB1,27")
      (footprint "eagle-import:B1,27")
      (libsource (lib "eagle-import") (part "TPB1,27"))
    )
    (comp (ref "TX4")
      (value "TPB1,27")
      (footprint "eagle-import:B1,27")
      (libsource (lib "eagle-import") (part "TPB1,27"))
    )
    (comp (ref "TX7")
      (value "TPB1,27")
      (footprint "eagle-import:B1,27")
      (libsource (lib "eagle-import") (part "TPB1,27"))
    )
    (comp (ref "WR")
      (value "TPB1,27")
      (footprint "eagle-import:B1,27")
      (libsource (lib "eagle-import") (part "TPB1,27"))
    )
    (comp (ref "X1")
      (value "1365-10")
      (footprint "eagle-import:1365-10")
      (libsource (lib "eagle-import") (part "1365-10"))
    )
    (comp (ref "Y2")
      (value "RESONATORSMD")
      (footprint "eagle-import:RESONATOR-SMD")
      (libsource (lib "eagle-import") (part "RESONATORSMD"))
    )
    (comp (ref "AN0")
      (value "TPB1,27")
      (footprint "eagle-import:B1,27")
      (libsource (lib "eagle-import") (part "TPB1,27"))
    )
    (comp (ref "AN1")
      (value "TPB1,27")
      (footprint "eagle-import:B1,27")
      (libsource (lib "eagle-import") (part "TPB1,27"))
    )
    (comp (ref "C8")
      (value "33nF")
      (footprint "eagle-import:0603-CAP")
      (libsource (lib "eagle-import") (part "CAP0603-CAP"))
    )
    (comp (ref "C17")
      (value "33nF")
      (footprint "eagle-import:0603-CAP")
      (libsource (lib "eagle-import") (part "CAP0603-CAP"))
    )
    (comp (ref "C19")
      (value "0,1")
      (footprint "eagle-import:0603-CAP")
      (libsource (lib "eagle-import") (part "CAP0603-CAP"))
    )
    (comp (ref "C20")
      (value "0,1")
      (footprint "eagle-import:0603-CAP")
      (libsource (lib "eagle-import") (part "CAP0603-CAP"))
    )
    (comp (ref "C21")
      (value "0,22")
      (footprint "eagle-import:0603-CAP")
      (libsource (lib "eagle-import") (part "CAP0603-CAP"))
    )
    (comp (ref "C41")
      (value "0,1")
      (footprint "eagle-import:0603-CAP")
      (libsource (lib "eagle-import") (part "CAP0603-CAP"))
    )
    (comp (ref "C42")
      (value "0,1")
      (footprint "eagle-import:0603-CAP")
      (libsource (lib "eagle-import") (part "CAP0603-CAP"))
    )
    (comp (ref "C43")
      (value "0,22")
      (footprint "eagle-import:0603-CAP")
      (libsource (lib "eagle-import") (part "CAP0603-CAP"))
    )
    (comp (ref "IC2")
      (value "VNH2SP30TR-E")
      (footprint "eagle-import:MULTIPOWERSO-30")
      (libsource (lib "eagle-import") (part "VNH3ASP30-E"))
    )
    (comp (ref "IC6")
      (value "VNH2SP30TR-E")
      (footprint "eagle-import:MULTIPOWERSO-30")
      (libsource (lib "eagle-import") (part "VNH3ASP30-E"))
    )
    (comp (ref "L_ENA")
      (value "TPB1,27")
      (footprint "eagle-import:B1,27")
      (libsource (lib "eagle-import") (part "TPB1,27"))
    )
    (comp (ref "L_ENB")
      (value "TPB1,27")
      (footprint "eagle-import:B1,27")
      (libsource (lib "eagle-import") (part "TPB1,27"))
    )
    (comp (ref "L_INA")
      (value "TPB1,27")
      (footprint "eagle-import:B1,27")
      (libsource (lib "eagle-import") (part "TPB1,27"))
    )
    (comp (ref "L_INB")
      (value "TPB1,27")
      (footprint "eagle-import:B1,27")
      (libsource (lib "eagle-import") (part "TPB1,27"))
    )
    (comp (ref "L_PWM")
      (value "TPB1,27")
      (footprint "eagle-import:B1,27")
      (libsource (lib "eagle-import") (part "TPB1,27"))
    )
    (comp (ref "M1L")
      (value "LEDCHIP-LED0603")
      (footprint "eagle-import:CHIP-LED0603")
      (libsource (lib "eagle-import") (part "LEDCHIP-LED0603"))
    )
    (comp (ref "M1R")
      (value "LEDCHIP-LED0603")
      (footprint "eagle-import:CHIP-LED0603")
      (libsource (lib "eagle-import") (part "LEDCHIP-LED0603"))
    )
    (comp (ref "M2L")
      (value "LEDCHIP-LED0603")
      (footprint "eagle-import:CHIP-LED0603")
      (libsource (lib "eagle-import") (part "LEDCHIP-LED0603"))
    )
    (comp (ref "M2R")
      (value "LEDCHIP-LED0603")
      (footprint "eagle-import:CHIP-LED0603")
      (libsource (lib "eagle-import") (part "LEDCHIP-LED0603"))
    )
    (comp (ref "PAD92")
      (value "WIREPAD4,16O1,6")
      (footprint "eagle-import:4,16O1,6")
      (libsource (lib "eagle-import") (part "WIREPAD4,16O1,6"))
    )
    (comp (ref "PAD93")
      (value "WIREPAD4,16O1,6")
      (footprint "eagle-import:4,16O1,6")
      (libsource (lib "eagle-import") (part "WIREPAD4,16O1,6"))
    )
    (comp (ref "PAD94")
      (value "WIREPAD4,16O1,6")
      (footprint "eagle-import:4,16O1,6")
      (libsource (lib "eagle-import") (part "WIREPAD4,16O1,6"))
    )
    (comp (ref "PAD95")
      (value "WIREPAD4,16O1,6")
      (footprint "eagle-import:4,16O1,6")
      (libsource (lib "eagle-import") (part "WIREPAD4,16O1,6"))
    )
    (comp (ref "R2")
      (value "3k3")
      (footprint "eagle-import:0603-RES")
      (libsource (lib "eagle-import") (part "RESISTOR0603-RES"))
    )
    (comp (ref "R3")
      (value "1k")
      (footprint "eagle-import:0603-RES")
      (libsource (lib "eagle-import") (part "RESISTOR0603-RES"))
    )
    (comp (ref "R4")
      (value "1k")
      (footprint "eagle-import:0603-RES")
      (libsource (lib "eagle-import") (part "RESISTOR0603-RES"))
    )
    (comp (ref "R5")
      (value "1k")
      (footprint "eagle-import:0603-RES")
      (libsource (lib "eagle-import") (part "RESISTOR0603-RES"))
    )
    (comp (ref "R6")
      (value "1k")
      (footprint "eagle-import:0603-RES")
      (libsource (lib "eagle-import") (part "RESISTOR0603-RES"))
    )
    (comp (ref "R7")
      (value "1k")
      (footprint "eagle-import:0603-RES")
      (libsource (lib "eagle-import") (part "RESISTOR0603-RES"))
    )
    (comp (ref "R12")
      (value "10k")
      (footprint "eagle-import:0603-RES")
      (libsource (lib "eagle-import") (part "RESISTOR0603-RES"))
    )
    (comp (ref "R13")
      (value "1k5")
      (footprint "eagle-import:0603-RES")
      (libsource (lib "eagle-import") (part "RESISTOR0603-RES"))
    )
    (comp (ref "R25")
      (value "3k3")
      (footprint "eagle-import:0603-RES")
      (libsource (lib "eagle-import") (part "RESISTOR0603-RES"))
    )
    (comp (ref "R27")
      (value "3k3")
      (footprint "eagle-import:0603-RES")
      (libsource (lib "eagle-import") (part "RESISTOR0603-RES"))
    )
    (comp (ref "R28")
      (value "3k3")
      (footprint "eagle-import:0603-RES")
      (libsource (lib "eagle-import") (part "RESISTOR0603-RES"))
    )
    (comp (ref "R29")
      (value "10k")
      (footprint "eagle-import:0603-RES")
      (libsource (lib "eagle-import") (part "RESISTOR0603-RES"))
    )
    (comp (ref "R30")
      (value "1k5")
      (footprint "eagle-import:0603-RES")
      (libsource (lib "eagle-import") (part "RESISTOR0603-RES"))
    )
    (comp (ref "R31")
      (value "1k")
      (footprint "eagle-import:0603-RES")
      (libsource (lib "eagle-import") (part "RESISTOR0603-RES"))
    )
    (comp (ref "R32")
      (value "1k")
      (footprint "eagle-import:0603-RES")
      (libsource (lib "eagle-import") (part "RESISTOR0603-RES"))
    )
    (comp (ref "R33")
      (value "1k")
      (footprint "eagle-import:0603-RES")
      (libsource (lib "eagle-import") (part "RESISTOR0603-RES"))
    )
    (comp (ref "R34")
      (value "1k")
      (footprint "eagle-import:0603-RES")
      (libsource (lib "eagle-import") (part "RESISTOR0603-RES"))
    )
    (comp (ref "R36")
      (value "1k")
      (footprint "eagle-import:0603-RES")
      (libsource (lib "eagle-import") (part "RESISTOR0603-RES"))
    )
    (comp (ref "R41")
      (value "1k")
      (footprint "eagle-import:0603-RES")
      (libsource (lib "eagle-import") (part "RESISTOR0603-RES"))
    )
    (comp (ref "R56")
      (value "1k")
      (footprint "eagle-import:0603-RES")
      (libsource (lib "eagle-import") (part "RESISTOR0603-RES"))
    )
    (comp (ref "R_ENA")
      (value "TPB1,27")
      (footprint "eagle-import:B1,27")
      (libsource (lib "eagle-import") (part "TPB1,27"))
    )
    (comp (ref "R_ENB")
      (value "TPB1,27")
      (footprint "eagle-import:B1,27")
      (libsource (lib "eagle-import") (part "TPB1,27"))
    )
    (comp (ref "R_INA")
      (value "TPB1,27")
      (footprint "eagle-import:B1,27")
      (libsource (lib "eagle-import") (part "TPB1,27"))
    )
    (comp (ref "R_INB")
      (value "TPB1,27")
      (footprint "eagle-import:B1,27")
      (libsource (lib "eagle-import") (part "TPB1,27"))
    )
    (comp (ref "R_PWM")
      (value "TPB1,27")
      (footprint "eagle-import:B1,27")
      (libsource (lib "eagle-import") (part "TPB1,27"))
    )
    (comp (ref "3V3")
      (value "TPB1,27")
      (footprint "eagle-import:B1,27")
      (libsource (lib "eagle-import") (part "TPB1,27"))
    )
    (comp (ref "12V5")
      (value "TPB1,27")
      (footprint "eagle-import:B1,27")
      (libsource (lib "eagle-import") (part "TPB1,27"))
    )
    (comp (ref "12V5IN")
      (value "TPB1,27")
      (footprint "eagle-import:B1,27")
      (libsource (lib "eagle-import") (part "TPB1,27"))
    )
    (comp (ref "C5")
      (value "10uF")
      (footprint "eagle-import:1210")
      (libsource (lib "eagle-import") (part "CAP1210"))
    )
    (comp (ref "C26")
      (value "10,0")
      (footprint "eagle-import:1210")
      (libsource (lib "eagle-import") (part "CAP1210"))
    )
    (comp (ref "C49")
      (value "100p")
      (footprint "eagle-import:0603-CAP")
      (libsource (lib "eagle-import") (part "CAP0603-CAP"))
    )
    (comp (ref "C53")
      (value "10uF")
      (footprint "eagle-import:1210")
      (libsource (lib "eagle-import") (part "CAP1210"))
    )
    (comp (ref "C54")
      (value "10uF")
      (footprint "eagle-import:1210")
      (libsource (lib "eagle-import") (part "CAP1210"))
    )
    (comp (ref "C59")
      (value "0.1")
      (footprint "eagle-import:0603-CAP")
      (libsource (lib "eagle-import") (part "CAP0603-CAP"))
    )
    (comp (ref "C60")
      (value "0.1")
      (footprint "eagle-import:0603-CAP")
      (libsource (lib "eagle-import") (part "CAP0603-CAP"))
    )
    (comp (ref "C61")
      (value "10uF")
      (footprint "eagle-import:1210")
      (libsource (lib "eagle-import") (part "CAP1210"))
    )
    (comp (ref "C62")
      (value "0.1")
      (footprint "eagle-import:0603-CAP")
      (libsource (lib "eagle-import") (part "CAP0603-CAP"))
    )
    (comp (ref "C63")
      (value "10uF")
      (footprint "eagle-import:1210")
      (libsource (lib "eagle-import") (part "CAP1210"))
    )
    (comp (ref "CLK_OLED")
      (value "TPB1,27")
      (footprint "eagle-import:B1,27")
      (libsource (lib "eagle-import") (part "TPB1,27"))
    )
    (comp (ref "CS_OLED")
      (value "TPB1,27")
      (footprint "eagle-import:B1,27")
      (libsource (lib "eagle-import") (part "TPB1,27"))
    )
    (comp (ref "D2")
      (value "BAS70-04")
      (footprint "eagle-import:SOT23")
      (libsource (lib "eagle-import") (part "BAS70-04"))
    )
    (comp (ref "D3")
      (value "MBR0530")
      (footprint "eagle-import:SOD123")
      (libsource (lib "eagle-import") (part "MBR0520LT"))
    )
    (comp (ref "DAT_OLED")
      (value "TPB1,27")
      (footprint "eagle-import:B1,27")
      (libsource (lib "eagle-import") (part "TPB1,27"))
    )
    (comp (ref "DC_OLED")
      (value "TPB1,27")
      (footprint "eagle-import:B1,27")
      (libsource (lib "eagle-import") (part "TPB1,27"))
    )
    (comp (ref "EN_OLED")
      (value "TPB1,27")
      (footprint "eagle-import:B1,27")
      (libsource (lib "eagle-import") (part "TPB1,27"))
    )
    (comp (ref "FB_OLED")
      (value "TPB1,27")
      (footprint "eagle-import:B1,27")
      (libsource (lib "eagle-import") (part "TPB1,27"))
    )
    (comp (ref "J1")
      (value "XF2J-3024-11")
      (footprint "eagle-import:XF2J-3024-11")
      (libsource (lib "eagle-import") (part "XF2-30?24-11J"))
    )
    (comp (ref "JOY_CENT")
      (value "TPB1,27")
      (footprint "eagle-import:B1,27")
      (libsource (lib "eagle-import") (part "TPB1,27"))
    )
    (comp (ref "JOY_DOWN")
      (value "TPB1,27")
      (footprint "eagle-import:B1,27")
      (libsource (lib "eagle-import") (part "TPB1,27"))
    )
    (comp (ref "JOY_LEFT")
      (value "TPB1,27")
      (footprint "eagle-import:B1,27")
      (libsource (lib "eagle-import") (part "TPB1,27"))
    )
    (comp (ref "JOY_RIGHT")
      (value "TPB1,27")
      (footprint "eagle-import:B1,27")
      (libsource (lib "eagle-import") (part "TPB1,27"))
    )
    (comp (ref "JOY_UP")
      (value "TPB1,27")
      (footprint "eagle-import:B1,27")
      (libsource (lib "eagle-import") (part "TPB1,27"))
    )
    (comp (ref "JP2")
      (value "JOYSTICK_MINI4UCON")
      (footprint "eagle-import:JOYSTICK_MINI")
      (libsource (lib "eagle-import") (part "JOYSTICK_MINI4UCON"))
    )
    (comp (ref "L2")
      (value "10uH")
      (footprint "eagle-import:WE-KI_0805_B")
      (libsource (lib "eagle-import") (part "WE-KIHQ_0805"))
    )
    (comp (ref "Q2")
      (value "IRLML6401")
      (footprint "eagle-import:MICRO3")
      (libsource (lib "eagle-import") (part "IRLML5203"))
    )
    (comp (ref "Q3")
      (value "TRANSISTOR_NPNSOT23-3")
      (footprint "eagle-import:SOT23-3")
      (libsource (lib "eagle-import") (part "TRANSISTOR_NPNSOT23-3"))
    )
    (comp (ref "R14")
      (value "117k")
      (footprint "eagle-import:0603-RES")
      (libsource (lib "eagle-import") (part "RESISTOR0603-RES"))
    )
    (comp (ref "R15")
      (value "13k3")
      (footprint "eagle-import:0603-RES")
      (libsource (lib "eagle-import") (part "RESISTOR0603-RES"))
    )
    (comp (ref "R16")
      (value "10k")
      (footprint "eagle-import:0603-RES")
      (libsource (lib "eagle-import") (part "RESISTOR0603-RES"))
    )
    (comp (ref "R17")
      (value "51r")
      (footprint "eagle-import:0603-RES")
      (libsource (lib "eagle-import") (part "RESISTOR0603-RES"))
    )
    (comp (ref "R18")
      (value "680k")
      (footprint "eagle-import:0603-RES")
      (libsource (lib "eagle-import") (part "RESISTOR0603-RES"))
    )
    (comp (ref "RES_OLED")
      (value "TPB1,27")
      (footprint "eagle-import:B1,27")
      (libsource (lib "eagle-import") (part "TPB1,27"))
    )
    (comp (ref "TP9")
      (value "TPB1,27")
      (footprint "eagle-import:B1,27")
      (libsource (lib "eagle-import") (part "TPB1,27"))
    )
    (comp (ref "TP50")
      (value "TPB1,27")
      (footprint "eagle-import:B1,27")
      (libsource (lib "eagle-import") (part "TPB1,27"))
    )
    (comp (ref "TP82")
      (value "TPB1,27")
      (footprint "eagle-import:B1,27")
      (libsource (lib "eagle-import") (part "TPB1,27"))
    )
    (comp (ref "U$2")
      (value "LM2733")
      (footprint "eagle-import:SOT23-DBV")
      (libsource (lib "eagle-import") (part "LM2733"))
    )
    (comp (ref "VCORE")
      (value "TPB1,27")
      (footprint "eagle-import:B1,27")
      (libsource (lib "eagle-import") (part "TPB1,27"))
    )
    (comp (ref "PAD3")
      (value "1,6/0,9")
      (footprint "eagle-import:1,6_0,9")
      (libsource (lib "eagle-import") (part "1,6/0,9"))
    )
    (comp (ref "PAD4")
      (value "1,6/0,9")
      (footprint "eagle-import:1,6_0,9")
      (libsource (lib "eagle-import") (part "1,6/0,9"))
    )
    (comp (ref "PAD7")
      (value "1,6/0,9")
      (footprint "eagle-import:1,6_0,9")
      (libsource (lib "eagle-import") (part "1,6/0,9"))
    )
    (comp (ref "PAD8")
      (value "1,6/0,9")
      (footprint "eagle-import:1,6_0,9")
      (libsource (lib "eagle-import") (part "1,6/0,9"))
    )
    (comp (ref "PAD9")
      (value "1,6/0,9")
      (footprint "eagle-import:1,6_0,9")
      (libsource (lib "eagle-import") (part "1,6/0,9"))
    )
    (comp (ref "PAD10")
      (value "1,6/0,9")
      (footprint "eagle-import:1,6_0,9")
      (libsource (lib "eagle-import") (part "1,6/0,9"))
    )
    (comp (ref "PAD11")
      (value "1,6/0,9")
      (footprint "eagle-import:1,6_0,9")
      (libsource (lib "eagle-import") (part "1,6/0,9"))
    )
    (comp (ref "PAD12")
      (value "1,6/0,9")
      (footprint "eagle-import:1,6_0,9")
      (libsource (lib "eagle-import") (part "1,6/0,9"))
    )
    (comp (ref "PAD13")
      (value "1,6/0,9")
      (footprint "eagle-import:1,6_0,9")
      (libsource (lib "eagle-import") (part "1,6/0,9"))
    )
    (comp (ref "PAD14")
      (value "1,6/0,9")
      (footprint "eagle-import:1,6_0,9")
      (libsource (lib "eagle-import") (part "1,6/0,9"))
    )
    (comp (ref "PAD15")
      (value "1,6/0,9")
      (footprint "eagle-import:1,6_0,9")
      (libsource (lib "eagle-import") (part "1,6/0,9"))
    )
    (comp (ref "PAD16")
      (value "1,6/0,9")
      (footprint "eagle-import:1,6_0,9")
      (libsource (lib "eagle-import") (part "1,6/0,9"))
    )
    (comp (ref "PAD17")
      (value "1,6/0,9")
      (footprint "eagle-import:1,6_0,9")
      (libsource (lib "eagle-import") (part "1,6/0,9"))
    )
    (comp (ref "PAD18")
      (value "1,6/0,9")
      (footprint "eagle-import:1,6_0,9")
      (libsource (lib "eagle-import") (part "1,6/0,9"))
    )
    (comp (ref "PAD19")
      (value "1,6/0,9")
      (footprint "eagle-import:1,6_0,9")
      (libsource (lib "eagle-import") (part "1,6/0,9"))
    )
    (comp (ref "PAD20")
      (value "1,6/0,9")
      (footprint "eagle-import:1,6_0,9")
      (libsource (lib "eagle-import") (part "1,6/0,9"))
    )
    (comp (ref "PAD21")
      (value "1,6/0,9")
      (footprint "eagle-import:1,6_0,9")
      (libsource (lib "eagle-import") (part "1,6/0,9"))
    )
    (comp (ref "PAD22")
      (value "1,6/0,9")
      (footprint "eagle-import:1,6_0,9")
      (libsource (lib "eagle-import") (part "1,6/0,9"))
    )
    (comp (ref "PAD23")
      (value "1,6/0,9")
      (footprint "eagle-import:1,6_0,9")
      (libsource (lib "eagle-import") (part "1,6/0,9"))
    )
    (comp (ref "PAD24")
      (value "1,6/0,9")
      (footprint "eagle-import:1,6_0,9")
      (libsource (lib "eagle-import") (part "1,6/0,9"))
    )
    (comp (ref "PAD26")
      (value "WIREPAD1,6/0,8")
      (footprint "eagle-import:1,6_0,8")
      (libsource (lib "eagle-import") (part "WIREPAD1,6/0,8"))
    )
    (comp (ref "PAD27")
      (value "WIREPAD1,6/0,8")
      (footprint "eagle-import:1,6_0,8")
      (libsource (lib "eagle-import") (part "WIREPAD1,6/0,8"))
    )
    (comp (ref "PAD28")
      (value "WIREPAD1,6/0,8")
      (footprint "eagle-import:1,6_0,8")
      (libsource (lib "eagle-import") (part "WIREPAD1,6/0,8"))
    )
    (comp (ref "PAD29")
      (value "WIREPAD1,6/0,8")
      (footprint "eagle-import:1,6_0,8")
      (libsource (lib "eagle-import") (part "WIREPAD1,6/0,8"))
    )
    (comp (ref "PAD30")
      (value "WIREPAD1,6/0,8")
      (footprint "eagle-import:1,6_0,8")
      (libsource (lib "eagle-import") (part "WIREPAD1,6/0,8"))
    )
    (comp (ref "PAD31")
      (value "WIREPAD1,6/0,8")
      (footprint "eagle-import:1,6_0,8")
      (libsource (lib "eagle-import") (part "WIREPAD1,6/0,8"))
    )
    (comp (ref "PAD32")
      (value "WIREPAD1,6/0,8")
      (footprint "eagle-import:1,6_0,8")
      (libsource (lib "eagle-import") (part "WIREPAD1,6/0,8"))
    )
    (comp (ref "PAD33")
      (value "WIREPAD1,6/0,8")
      (footprint "eagle-import:1,6_0,8")
      (libsource (lib "eagle-import") (part "WIREPAD1,6/0,8"))
    )
    (comp (ref "PAD34")
      (value "WIREPAD1,6/0,8")
      (footprint "eagle-import:1,6_0,8")
      (libsource (lib "eagle-import") (part "WIREPAD1,6/0,8"))
    )
    (comp (ref "PAD35")
      (value "WIREPAD1,6/0,8")
      (footprint "eagle-import:1,6_0,8")
      (libsource (lib "eagle-import") (part "WIREPAD1,6/0,8"))
    )
    (comp (ref "PAD36")
      (value "WIREPAD1,6/0,8")
      (footprint "eagle-import:1,6_0,8")
      (libsource (lib "eagle-import") (part "WIREPAD1,6/0,8"))
    )
    (comp (ref "PAD37")
      (value "WIREPAD1,6/0,8")
      (footprint "eagle-import:1,6_0,8")
      (libsource (lib "eagle-import") (part "WIREPAD1,6/0,8"))
    )
    (comp (ref "PAD38")
      (value "WIREPAD1,6/0,8")
      (footprint "eagle-import:1,6_0,8")
      (libsource (lib "eagle-import") (part "WIREPAD1,6/0,8"))
    )
    (comp (ref "PAD39")
      (value "WIREPAD1,6/0,8")
      (footprint "eagle-import:1,6_0,8")
      (libsource (lib "eagle-import") (part "WIREPAD1,6/0,8"))
    )
    (comp (ref "PAD40")
      (value "WIREPAD1,6/0,8")
      (footprint "eagle-import:1,6_0,8")
      (libsource (lib "eagle-import") (part "WIREPAD1,6/0,8"))
    )
    (comp (ref "PAD41")
      (value "WIREPAD1,6/0,8")
      (footprint "eagle-import:1,6_0,8")
      (libsource (lib "eagle-import") (part "WIREPAD1,6/0,8"))
    )
    (comp (ref "PAD42")
      (value "WIREPAD1,6/0,8")
      (footprint "eagle-import:1,6_0,8")
      (libsource (lib "eagle-import") (part "WIREPAD1,6/0,8"))
    )
    (comp (ref "PAD43")
      (value "WIREPAD1,6/0,8")
      (footprint "eagle-import:1,6_0,8")
      (libsource (lib "eagle-import") (part "WIREPAD1,6/0,8"))
    )
    (comp (ref "PAD44")
      (value "WIREPAD1,6/0,8")
      (footprint "eagle-import:1,6_0,8")
      (libsource (lib "eagle-import") (part "WIREPAD1,6/0,8"))
    )
    (comp (ref "PAD45")
      (value "WIREPAD1,6/0,8")
      (footprint "eagle-import:1,6_0,8")
      (libsource (lib "eagle-import") (part "WIREPAD1,6/0,8"))
    )
    (comp (ref "PAD46")
      (value "WIREPAD1,6/0,8")
      (footprint "eagle-import:1,6_0,8")
      (libsource (lib "eagle-import") (part "WIREPAD1,6/0,8"))
    )
    (comp (ref "PAD47")
      (value "WIREPAD1,6/0,8")
      (footprint "eagle-import:1,6_0,8")
      (libsource (lib "eagle-import") (part "WIREPAD1,6/0,8"))
    )
    (comp (ref "PAD48")
      (value "WIREPAD1,6/0,8")
      (footprint "eagle-import:1,6_0,8")
      (libsource (lib "eagle-import") (part "WIREPAD1,6/0,8"))
    )
    (comp (ref "PAD49")
      (value "WIREPAD1,6/0,8")
      (footprint "eagle-import:1,6_0,8")
      (libsource (lib "eagle-import") (part "WIREPAD1,6/0,8"))
    )
    (comp (ref "PAD50")
      (value "WIREPAD1,6/0,8")
      (footprint "eagle-import:1,6_0,8")
      (libsource (lib "eagle-import") (part "WIREPAD1,6/0,8"))
    )
    (comp (ref "PAD51")
      (value "WIREPAD1,6/0,8")
      (footprint "eagle-import:1,6_0,8")
      (libsource (lib "eagle-import") (part "WIREPAD1,6/0,8"))
    )
    (comp (ref "PAD52")
      (value "WIREPAD1,6/0,8")
      (footprint "eagle-import:1,6_0,8")
      (libsource (lib "eagle-import") (part "WIREPAD1,6/0,8"))
    )
    (comp (ref "PAD53")
      (value "WIREPAD1,6/0,8")
      (footprint "eagle-import:1,6_0,8")
      (libsource (lib "eagle-import") (part "WIREPAD1,6/0,8"))
    )
    (comp (ref "PAD54")
      (value "WIREPAD1,6/0,8")
      (footprint "eagle-import:1,6_0,8")
      (libsource (lib "eagle-import") (part "WIREPAD1,6/0,8"))
    )
    (comp (ref "PAD55")
      (value "WIREPAD1,6/0,8")
      (footprint "eagle-import:1,6_0,8")
      (libsource (lib "eagle-import") (part "WIREPAD1,6/0,8"))
    )
    (comp (ref "PAD56")
      (value "WIREPAD1,6/0,8")
      (footprint "eagle-import:1,6_0,8")
      (libsource (lib "eagle-import") (part "WIREPAD1,6/0,8"))
    )
    (comp (ref "PAD57")
      (value "WIREPAD1,6/0,8")
      (footprint "eagle-import:1,6_0,8")
      (libsource (lib "eagle-import") (part "WIREPAD1,6/0,8"))
    )
    (comp (ref "PAD58")
      (value "WIREPAD1,6/0,8")
      (footprint "eagle-import:1,6_0,8")
      (libsource (lib "eagle-import") (part "WIREPAD1,6/0,8"))
    )
    (comp (ref "PAD59")
      (value "WIREPAD1,6/0,8")
      (footprint "eagle-import:1,6_0,8")
      (libsource (lib "eagle-import") (part "WIREPAD1,6/0,8"))
    )
    (comp (ref "PAD60")
      (value "WIREPAD1,6/0,8")
      (footprint "eagle-import:1,6_0,8")
      (libsource (lib "eagle-import") (part "WIREPAD1,6/0,8"))
    )
    (comp (ref "PAD61")
      (value "WIREPAD1,6/0,8")
      (footprint "eagle-import:1,6_0,8")
      (libsource (lib "eagle-import") (part "WIREPAD1,6/0,8"))
    )
    (comp (ref "PAD62")
      (value "WIREPAD1,6/0,8")
      (footprint "eagle-import:1,6_0,8")
      (libsource (lib "eagle-import") (part "WIREPAD1,6/0,8"))
    )
    (comp (ref "PAD63")
      (value "WIREPAD1,6/0,8")
      (footprint "eagle-import:1,6_0,8")
      (libsource (lib "eagle-import") (part "WIREPAD1,6/0,8"))
    )
    (comp (ref "PAD64")
      (value "WIREPAD1,6/0,8")
      (footprint "eagle-import:1,6_0,8")
      (libsource (lib "eagle-import") (part "WIREPAD1,6/0,8"))
    )
    (comp (ref "PAD65")
      (value "WIREPAD1,6/0,8")
      (footprint "eagle-import:1,6_0,8")
      (libsource (lib "eagle-import") (part "WIREPAD1,6/0,8"))
    )
    (comp (ref "PAD66")
      (value "WIREPAD1,6/0,8")
      (footprint "eagle-import:1,6_0,8")
      (libsource (lib "eagle-import") (part "WIREPAD1,6/0,8"))
    )
    (comp (ref "PAD67")
      (value "WIREPAD1,6/0,8")
      (footprint "eagle-import:1,6_0,8")
      (libsource (lib "eagle-import") (part "WIREPAD1,6/0,8"))
    )
    (comp (ref "PAD68")
      (value "WIREPAD1,6/0,8")
      (footprint "eagle-import:1,6_0,8")
      (libsource (lib "eagle-import") (part "WIREPAD1,6/0,8"))
    )
    (comp (ref "PAD69")
      (value "WIREPAD1,6/0,8")
      (footprint "eagle-import:1,6_0,8")
      (libsource (lib "eagle-import") (part "WIREPAD1,6/0,8"))
    )
    (comp (ref "PAD70")
      (value "WIREPAD1,6/0,8")
      (footprint "eagle-import:1,6_0,8")
      (libsource (lib "eagle-import") (part "WIREPAD1,6/0,8"))
    )
    (comp (ref "PAD71")
      (value "WIREPAD1,6/0,8")
      (footprint "eagle-import:1,6_0,8")
      (libsource (lib "eagle-import") (part "WIREPAD1,6/0,8"))
    )
    (comp (ref "PAD72")
      (value "WIREPAD1,6/0,8")
      (footprint "eagle-import:1,6_0,8")
      (libsource (lib "eagle-import") (part "WIREPAD1,6/0,8"))
    )
    (comp (ref "PAD73")
      (value "WIREPAD1,6/0,8")
      (footprint "eagle-import:1,6_0,8")
      (libsource (lib "eagle-import") (part "WIREPAD1,6/0,8"))
    )
    (comp (ref "PAD74")
      (value "WIREPAD1,6/0,8")
      (footprint "eagle-import:1,6_0,8")
      (libsource (lib "eagle-import") (part "WIREPAD1,6/0,8"))
    )
    (comp (ref "PAD75")
      (value "WIREPAD1,6/0,8")
      (footprint "eagle-import:1,6_0,8")
      (libsource (lib "eagle-import") (part "WIREPAD1,6/0,8"))
    )
    (comp (ref "PAD76")
      (value "WIREPAD1,6/0,8")
      (footprint "eagle-import:1,6_0,8")
      (libsource (lib "eagle-import") (part "WIREPAD1,6/0,8"))
    )
    (comp (ref "PAD77")
      (value "WIREPAD1,6/0,8")
      (footprint "eagle-import:1,6_0,8")
      (libsource (lib "eagle-import") (part "WIREPAD1,6/0,8"))
    )
    (comp (ref "PAD78")
      (value "WIREPAD1,6/0,8")
      (footprint "eagle-import:1,6_0,8")
      (libsource (lib "eagle-import") (part "WIREPAD1,6/0,8"))
    )
    (comp (ref "PAD79")
      (value "WIREPAD1,6/0,8")
      (footprint "eagle-import:1,6_0,8")
      (libsource (lib "eagle-import") (part "WIREPAD1,6/0,8"))
    )
    (comp (ref "PAD80")
      (value "WIREPAD1,6/0,8")
      (footprint "eagle-import:1,6_0,8")
      (libsource (lib "eagle-import") (part "WIREPAD1,6/0,8"))
    )
    (comp (ref "PAD81")
      (value "WIREPAD1,6/0,8")
      (footprint "eagle-import:1,6_0,8")
      (libsource (lib "eagle-import") (part "WIREPAD1,6/0,8"))
    )
    (comp (ref "PAD82")
      (value "WIREPAD1,6/0,8")
      (footprint "eagle-import:1,6_0,8")
      (libsource (lib "eagle-import") (part "WIREPAD1,6/0,8"))
    )
    (comp (ref "PAD83")
      (value "WIREPAD1,6/0,8")
      (footprint "eagle-import:1,6_0,8")
      (libsource (lib "eagle-import") (part "WIREPAD1,6/0,8"))
    )
    (comp (ref "PAD84")
      (value "WIREPAD1,6/0,8")
      (footprint "eagle-import:1,6_0,8")
      (libsource (lib "eagle-import") (part "WIREPAD1,6/0,8"))
    )
    (comp (ref "PAD85")
      (value "WIREPAD1,6/0,8")
      (footprint "eagle-import:1,6_0,8")
      (libsource (lib "eagle-import") (part "WIREPAD1,6/0,8"))
    )
    (comp (ref "PAD86")
      (value "WIREPAD1,6/0,8")
      (footprint "eagle-import:1,6_0,8")
      (libsource (lib "eagle-import") (part "WIREPAD1,6/0,8"))
    )
    (comp (ref "PAD87")
      (value "WIREPAD1,6/0,8")
      (footprint "eagle-import:1,6_0,8")
      (libsource (lib "eagle-import") (part "WIREPAD1,6/0,8"))
    )
    (comp (ref "PAD88")
      (value "WIREPAD1,6/0,8")
      (footprint "eagle-import:1,6_0,8")
      (libsource (lib "eagle-import") (part "WIREPAD1,6/0,8"))
    )
    (comp (ref "PAD89")
      (value "WIREPAD1,6/0,8")
      (footprint "eagle-import:1,6_0,8")
      (libsource (lib "eagle-import") (part "WIREPAD1,6/0,8"))
    )
    (comp (ref "PAD90")
      (value "WIREPAD1,6/0,8")
      (footprint "eagle-import:1,6_0,8")
      (libsource (lib "eagle-import") (part "WIREPAD1,6/0,8"))
    )
    (comp (ref "PAD91")
      (value "WIREPAD1,6/0,8")
      (footprint "eagle-import:1,6_0,8")
      (libsource (lib "eagle-import") (part "WIREPAD1,6/0,8"))
    )
    (comp (ref "C3")
      (value "0.1")
      (footprint "eagle-import:0603-CAP")
      (libsource (lib "eagle-import") (part "CAP0603-CAP"))
    )
    (comp (ref "CLK2")
      (value "TPB1,27")
      (footprint "eagle-import:B1,27")
      (libsource (lib "eagle-import") (part "TPB1,27"))
    )
    (comp (ref "CS2")
      (value "TPB1,27")
      (footprint "eagle-import:B1,27")
      (libsource (lib "eagle-import") (part "TPB1,27"))
    )
    (comp (ref "INT0")
      (value "TPB1,27")
      (footprint "eagle-import:B1,27")
      (libsource (lib "eagle-import") (part "TPB1,27"))
    )
    (comp (ref "RX2")
      (value "TPB1,27")
      (footprint "eagle-import:B1,27")
      (libsource (lib "eagle-import") (part "TPB1,27"))
    )
    (comp (ref "TX2")
      (value "TPB1,27")
      (footprint "eagle-import:B1,27")
      (libsource (lib "eagle-import") (part "TPB1,27"))
    )
    (comp (ref "U$5")
      (value "MMA7455L")
      (footprint "eagle-import:LGA14")
      (libsource (lib "eagle-import") (part "MMA7455L"))
    )
    (comp (ref "5V_MELEXIS")
      (value "TPB1,27")
      (footprint "eagle-import:B1,27")
      (libsource (lib "eagle-import") (part "TPB1,27"))
    )
    (comp (ref "C18")
      (value "0.1")
      (footprint "eagle-import:0603-CAP")
      (libsource (lib "eagle-import") (part "CAP0603-CAP"))
    )
    (comp (ref "C25")
      (value "CPOL-EUD/7343-31R")
      (footprint "eagle-import:D_7343-31R")
      (libsource (lib "eagle-import") (part "CPOL-EUD/7343-31R"))
    )
    (comp (ref "C30")
      (value "0.1")
      (footprint "eagle-import:0603-CAP")
      (libsource (lib "eagle-import") (part "CAP0603-CAP"))
    )
    (comp (ref "C47")
      (value "470nF")
      (footprint "eagle-import:0603-CAP")
      (libsource (lib "eagle-import") (part "CAP0603-CAP"))
    )
    (comp (ref "C48")
      (value "10nF")
      (footprint "eagle-import:0603-CAP")
      (libsource (lib "eagle-import") (part "CAP0603-CAP"))
    )
    (comp (ref "C64")
      (value "0.1")
      (footprint "eagle-import:0603-CAP")
      (libsource (lib "eagle-import") (part "CAP0603-CAP"))
    )
    (comp (ref "CLK6")
      (value "TPB1,27")
      (footprint "eagle-import:B1,27")
      (libsource (lib "eagle-import") (part "TPB1,27"))
    )
    (comp (ref "CS6")
      (value "TPB1,27")
      (footprint "eagle-import:B1,27")
      (libsource (lib "eagle-import") (part "TPB1,27"))
    )
    (comp (ref "IC1")
      (value "TPS773")
      (footprint "eagle-import:MSOP8")
      (libsource (lib "eagle-import") (part "TPS773"))
    )
    (comp (ref "INT1")
      (value "TPB1,27")
      (footprint "eagle-import:B1,27")
      (libsource (lib "eagle-import") (part "TPB1,27"))
    )
    (comp (ref "INT2")
      (value "TPB1,27")
      (footprint "eagle-import:B1,27")
      (libsource (lib "eagle-import") (part "TPB1,27"))
    )
    (comp (ref "J4")
      (value "XF2L-0625-1")
      (footprint "eagle-import:XF2L-0625-1")
      (fields (field (name "MF") "OMRON COMPONENTS USA"))
      (libsource (lib "eagle-import") (part "XF2-06?25-1L"))
    )
    (comp (ref "J5")
      (value "XF2L-0625-1")
      (footprint "eagle-import:XF2L-0625-1")
      (fields (field (name "MF") "OMRON COMPONENTS USA"))
      (libsource (lib "eagle-import") (part "XF2-06?25-1L"))
    )
    (comp (ref "R9")
      (value "10k")
      (footprint "eagle-import:0603-RES")
      (libsource (lib "eagle-import") (part "RESISTOR0603-RES"))
    )
    (comp (ref "R58")
      (value "10k")
      (footprint "eagle-import:0603-RES")
      (libsource (lib "eagle-import") (part "RESISTOR0603-RES"))
    )
    (comp (ref "RX6")
      (value "TPB1,27")
      (footprint "eagle-import:B1,27")
      (libsource (lib "eagle-import") (part "TPB1,27"))
    )
    (comp (ref "TX6")
      (value "TPB1,27")
      (footprint "eagle-import:B1,27")
      (libsource (lib "eagle-import") (part "TPB1,27"))
    )
    (comp (ref "U2")
      (value "L3G4200D")
      (footprint "eagle-import:LGA16-4X4")
      (libsource (lib "eagle-import") (part "L3G4200D"))
    )
    (comp (ref "5V")
      (value "M02")
      (footprint "eagle-import:02P")
      (libsource (lib "eagle-import") (part "M02"))
    )
    (comp (ref "5V_PANDA")
      (value "TPB1,27")
      (footprint "eagle-import:B1,27")
      (libsource (lib "eagle-import") (part "TPB1,27"))
    )
    (comp (ref "10UF/16V")
      (value "CAP_POL6032")
      (footprint "eagle-import:EIA6032")
      (libsource (lib "eagle-import") (part "CAP_POL6032"))
    )
    (comp (ref "BOOT")
      (value "TPB1,27")
      (footprint "eagle-import:B1,27")
      (libsource (lib "eagle-import") (part "TPB1,27"))
    )
    (comp (ref "C9")
      (value "4,7uF/6.3V")
      (footprint "eagle-import:0805")
      (libsource (lib "eagle-import") (part "CAP0805"))
    )
    (comp (ref "C10")
      (value "180pF")
      (footprint "eagle-import:0603-CAP")
      (libsource (lib "eagle-import") (part "CAP0603-CAP"))
    )
    (comp (ref "C11")
      (value "12pF")
      (footprint "eagle-import:0603-CAP")
      (libsource (lib "eagle-import") (part "CAP0603-CAP"))
    )
    (comp (ref "C15")
      (value "0.1")
      (footprint "eagle-import:0603-CAP")
      (libsource (lib "eagle-import") (part "CAP0603-CAP"))
    )
    (comp (ref "C27")
      (value "15nF")
      (footprint "eagle-import:0603-CAP")
      (libsource (lib "eagle-import") (part "CAP0603-CAP"))
    )
    (comp (ref "C29")
      (value "10uF/6.3V")
      (footprint "eagle-import:1210")
      (libsource (lib "eagle-import") (part "CAP1210"))
    )
    (comp (ref "C33")
      (value "47uF/16V")
      (footprint "eagle-import:C_6032-28R")
      (libsource (lib "eagle-import") (part "CPOL-EUC/6032-28R"))
    )
    (comp (ref "C100")
      (value "47uF/16V")
      (footprint "eagle-import:C_6032-28R")
      (libsource (lib "eagle-import") (part "CPOL-EUC/6032-28R"))
    )
    (comp (ref "COMP")
      (value "TPB1,27")
      (footprint "eagle-import:B1,27")
      (libsource (lib "eagle-import") (part "TPB1,27"))
    )
    (comp (ref "D100")
      (value "BAT54")
      (footprint "eagle-import:SOT23")
      (libsource (lib "eagle-import") (part "BAT54"))
    )
    (comp (ref "EN_PANDA")
      (value "TPB1,27")
      (footprint "eagle-import:B1,27")
      (libsource (lib "eagle-import") (part "TPB1,27"))
    )
    (comp (ref "GND")
      (value "3,81/1,4")
      (footprint "eagle-import:3,81_1,4")
      (libsource (lib "eagle-import") (part "3,81/1,4"))
    )
    (comp (ref "GND78")
      (value "3,81/1,4")
      (footprint "eagle-import:3,81_1,4")
      (libsource (lib "eagle-import") (part "3,81/1,4"))
    )
    (comp (ref "L1")
      (value "INDUCTORSRU1038")
      (footprint "eagle-import:SRU1038")
      (libsource (lib "eagle-import") (part "INDUCTORSRU1038"))
    )
    (comp (ref "R11")
      (value "63k4")
      (footprint "eagle-import:0603-RES")
      (libsource (lib "eagle-import") (part "RESISTOR0603-RES"))
    )
    (comp (ref "R26")
      (value "1k87")
      (footprint "eagle-import:0603-RES")
      (libsource (lib "eagle-import") (part "RESISTOR0603-RES"))
    )
    (comp (ref "R35")
      (value "100k")
      (footprint "eagle-import:0603-RES")
      (libsource (lib "eagle-import") (part "RESISTOR0603-RES"))
    )
    (comp (ref "R37")
      (value "10k")
      (footprint "eagle-import:0603-RES")
      (libsource (lib "eagle-import") (part "RESISTOR0603-RES"))
    )
    (comp (ref "U$3")
      (value "TPS54233")
      (footprint "eagle-import:SO8")
      (libsource (lib "eagle-import") (part "TPS54332"))
    )
    (comp (ref "VBAT")
      (value "3,81/1,4")
      (footprint "eagle-import:3,81_1,4")
      (libsource (lib "eagle-import") (part "3,81/1,4"))
    )
    (comp (ref "VSENSE")
      (value "TPB1,27")
      (footprint "eagle-import:B1,27")
      (libsource (lib "eagle-import") (part "TPB1,27"))
    )
    (comp (ref "CD")
      (value "TPB1,27")
      (footprint "eagle-import:B1,27")
      (libsource (lib "eagle-import") (part "TPB1,27"))
    )
    (comp (ref "CLK")
      (value "TPB1,27")
      (footprint "eagle-import:B1,27")
      (libsource (lib "eagle-import") (part "TPB1,27"))
    )
    (comp (ref "CMD")
      (value "TPB1,27")
      (footprint "eagle-import:B1,27")
      (libsource (lib "eagle-import") (part "TPB1,27"))
    )
    (comp (ref "DAT0")
      (value "TPB1,27")
      (footprint "eagle-import:B1,27")
      (libsource (lib "eagle-import") (part "TPB1,27"))
    )
    (comp (ref "DAT1")
      (value "TPB1,27")
      (footprint "eagle-import:B1,27")
      (libsource (lib "eagle-import") (part "TPB1,27"))
    )
    (comp (ref "DAT2")
      (value "TPB1,27")
      (footprint "eagle-import:B1,27")
      (libsource (lib "eagle-import") (part "TPB1,27"))
    )
    (comp (ref "DAT3")
      (value "TPB1,27")
      (footprint "eagle-import:B1,27")
      (libsource (lib "eagle-import") (part "TPB1,27"))
    )
    (comp (ref "IC4")
      (value "CP2103_USB_UART")
      (footprint "eagle-import:MLP28")
      (libsource (lib "eagle-import") (part "CP2103_USB_UART"))
    )
    (comp (ref "J3")
      (value "PINHD-2X14")
      (footprint "eagle-import:2X14")
      (libsource (lib "eagle-import") (part "PINHD-2X14"))
    )
    (comp (ref "J6")
      (value "PINHD-2X14")
      (footprint "eagle-import:2X14")
      (libsource (lib "eagle-import") (part "PINHD-2X14"))
    )
    (comp (ref "PANDA1")
      (value "LED0603")
      (footprint "eagle-import:LED-0603")
      (libsource (lib "eagle-import") (part "LED0603"))
    )
    (comp (ref "PANDA2")
      (value "LED0603")
      (footprint "eagle-import:LED-0603")
      (libsource (lib "eagle-import") (part "LED0603"))
    )
    (comp (ref "R38")
      (value "1k")
      (footprint "eagle-import:0603-RES")
      (libsource (lib "eagle-import") (part "RESISTOR0603-RES"))
    )
    (comp (ref "R43")
      (value "1k")
      (footprint "eagle-import:0603-RES")
      (libsource (lib "eagle-import") (part "RESISTOR0603-RES"))
    )
    (comp (ref "R59")
      (value "10k")
      (footprint "eagle-import:0603-RES")
      (libsource (lib "eagle-import") (part "RESISTOR0603-RES"))
    )
    (comp (ref "R60")
      (value "10k")
      (footprint "eagle-import:0603-RES")
      (libsource (lib "eagle-import") (part "RESISTOR0603-RES"))
    )
    (comp (ref "U1")
      (value "txb0108")
      (footprint "eagle-import:TSSOP20")
      (libsource (lib "eagle-import") (part "TXB0108PWR"))
    )
    (comp (ref "WP")
      (value "TPB1,27")
      (footprint "eagle-import:B1,27")
      (libsource (lib "eagle-import") (part "TPB1,27"))
    )
    (comp (ref "X4")
      (value "USB-A-S")
      (footprint "eagle-import:USB-A-S")
      (libsource (lib "eagle-import") (part "USB-A-S"))
    )
    (comp (ref "X7")
      (value "SDBMF")
      (footprint "eagle-import:SDBMF-009XXBXX2")
      (libsource (lib "eagle-import") (part "SDBMF"))
    )
  )
  (nets
    (net (code "1") (name "+3V3") (class "Default")
      (node (ref "3V3") (pin "TP") (pinfunction "TP_TP") (pintype "input"))
      (node (ref "C16") (pin "2") (pinfunction "2_2") (pintype "passive"))
      (node (ref "C22") (pin "2") (pinfunction "2_2") (pintype "passive"))
      (node (ref "C23") (pin "2") (pinfunction "2_2") (pintype "passive"))
      (node (ref "C24") (pin "2") (pinfunction "2_2") (pintype "passive"))
      (node (ref "C28") (pin "1") (pinfunction "1_1") (pintype "passive"))
      (node (ref "C3") (pin "1") (pinfunction "1_1") (pintype "passive"))
      (node (ref "C51") (pin "1") (pinfunction "1_1") (pintype "passive"))
      (node (ref "C52") (pin "1") (pinfunction "1_1") (pintype "passive"))
      (node (ref "C56") (pin "1") (pinfunction "1_1") (pintype "passive"))
      (node (ref "C58") (pin "1") (pinfunction "1_1") (pintype "passive"))
      (node (ref "C61") (pin "1") (pinfunction "1_1") (pintype "passive"))
      (node (ref "C62") (pin "1") (pinfunction "1_1") (pintype "passive"))
      (node (ref "C64") (pin "1") (pinfunction "1_1") (pintype "passive"))
      (node (ref "C71") (pin "2") (pinfunction "2_2") (pintype "passive"))
      (node (ref "C72") (pin "2") (pinfunction "2_2") (pintype "passive"))
      (node (ref "IC3") (pin "3") (pinfunction "VCC_3") (pintype "power_in"))
      (node (ref "IC4") (pin "5") (pinfunction "VIO_5") (pintype "power_in"))
      (node (ref "IC4") (pin "6") (pinfunction "VDD_6") (pintype "power_in"))
      (node (ref "IC8") (pin "3") (pinfunction "VO_3") (pintype "passive"))
      (node (ref "J1") (pin "24") (pinfunction "MS_24") (pintype "passive"))
      (node (ref "J1") (pin "26") (pinfunction "MS_26") (pintype "passive"))
      (node (ref "JP1") (pin "8") (pinfunction "8_8") (pintype "passive"))
      (node (ref "L3") (pin "1") (pinfunction "2_1") (pintype "passive"))
      (node (ref "MCU") (pin "14") (pinfunction "VCC1_14") (pintype "power_in"))
      (node (ref "MCU") (pin "60") (pinfunction "VCC2_60") (pintype "power_in"))
      (node (ref "POWER") (pin "A") (pinfunction "A_A") (pintype "passive"))
      (node (ref "R1") (pin "2") (pinfunction "2_2") (pintype "passive"))
      (node (ref "R2") (pin "2") (pinfunction "2_2") (pintype "passive"))
      (node (ref "R23") (pin "1") (pinfunction "1_1") (pintype "passive"))
      (node (ref "R25") (pin "2") (pinfunction "2_2") (pintype "passive"))
      (node (ref "R27") (pin "2") (pinfunction "2_2") (pintype "passive"))
      (node (ref "R28") (pin "2") (pinfunction "2_2") (pintype "passive"))
      (node (ref "R44") (pin "1") (pinfunction "1_1") (pintype "passive"))
      (node (ref "R45") (pin "1") (pinfunction "1_1") (pintype "passive"))
      (node (ref "R46") (pin "1") (pinfunction "1_1") (pintype "passive"))
      (node (ref "R48") (pin "2") (pinfunction "2_2") (pintype "passive"))
      (node (ref "R53") (pin "2") (pinfunction "2_2") (pintype "passive"))
      (node (ref "R58") (pin "1") (pinfunction "1_1") (pintype "passive"))
      (node (ref "R61") (pin "2") (pinfunction "2_2") (pintype "passive"))
      (node (ref "R62") (pin "2") (pinfunction "2_2") (pintype "passive"))
      (node (ref "U$5") (pin "1") (pinfunction "DVDD_IO_1") (pintype "bidirectional"))
      (node (ref "U$5") (pin "6") (pinfunction "AVDD_6") (pintype "bidirectional"))
      (node (ref "U1") (pin "19") (pinfunction "VCCB_19") (pintype "bidirectional"))
      (node (ref "U2") (pin "1") (pinfunction "VDDIO_1") (pintype "bidirectional"))
      (node (ref "U2") (pin "15") (pinfunction "RSVDV_15") (pintype "bidirectional"))
      (node (ref "U2") (pin "16") (pinfunction "VDD_16") (pintype "bidirectional"))
      (node (ref "X1") (pin "8") (pinfunction "S_8") (pintype "passive"))
      (node (ref "X7") (pin "3") (pinfunction "3_3") (pintype "passive"))
    )
    (net (code "2") (name "+5V_PANDA") (class "Default")
      (node (ref "5V") (pin "1") (pinfunction "1_1") (pintype "passive"))
      (node (ref "5V_PANDA") (pin "TP") (pinfunction "TP_TP") (pintype "input"))
      (node (ref "C100") (pin "+") (pinfunction "+_+") (pintype "passive"))
      (node (ref "C29") (pin "1") (pinfunction "1_1") (pintype "passive"))
      (node (ref "C33") (pin "+") (pinfunction "+_+") (pintype "passive"))
      (node (ref "C9") (pin "1") (pinfunction "1_1") (pintype "passive"))
      (node (ref "L1") (pin "2") (pinfunction "2_2") (pintype "passive"))
      (node (ref "R37") (pin "1") (pinfunction "1_1") (pintype "passive"))
    )
    (net (code "3") (name "5V_MELEXIS") (class "Default")
      (node (ref "5V_MELEXIS") (pin "TP") (pinfunction "TP_TP") (pintype "input"))
      (node (ref "C25") (pin "+") (pinfunction "+_+") (pintype "passive"))
      (node (ref "C30") (pin "1") (pinfunction "1_1") (pintype "passive"))
      (node (ref "IC1") (pin "1") (pinfunction "FB\\SENSE_1") (pintype "input"))
      (node (ref "IC1") (pin "7") (pinfunction "OUT_7") (pintype "output"))
      (node (ref "IC1") (pin "8") (pinfunction "OUT_8") (pintype "passive"))
      (node (ref "J4") (pin "5") (pinfunction "MS_5") (pintype "passive"))
      (node (ref "J5") (pin "5") (pinfunction "MS_5") (pintype "passive"))
    )
    (net (code "4") (name "12V5") (class "Default")
      (node (ref "12V5") (pin "TP") (pinfunction "TP_TP") (pintype "input"))
      (node (ref "C49") (pin "1") (pinfunction "1_1") (pintype "passive"))
      (node (ref "C5") (pin "1") (pinfunction "1_1") (pintype "passive"))
      (node (ref "C54") (pin "1") (pinfunction "1_1") (pintype "passive"))
      (node (ref "C59") (pin "1") (pinfunction "1_1") (pintype "passive"))
      (node (ref "D3") (pin "C") (pinfunction "C_C") (pintype "passive"))
      (node (ref "J1") (pin "29") (pinfunction "MS_29") (pintype "passive"))
      (node (ref "J1") (pin "3") (pinfunction "MS_3") (pintype "passive"))
      (node (ref "R14") (pin "2") (pinfunction "2_2") (pintype "passive"))
    )
    (net (code "5") (name "12V5VIN") (class "Default")
      (node (ref "12V5IN") (pin "TP") (pinfunction "TP_TP") (pintype "input"))
      (node (ref "C26") (pin "1") (pinfunction "1_1") (pintype "passive"))
      (node (ref "L2") (pin "2") (pinfunction "1_2") (pintype "passive"))
      (node (ref "Q2") (pin "3") (pinfunction "D_3") (pintype "passive"))
      (node (ref "U$2") (pin "4") (pinfunction "EN_4") (pintype "input"))
      (node (ref "U$2") (pin "5") (pinfunction "VIN_5") (pintype "power_in"))
    )
    (net (code "6") (name "400V") (class "Default")
      (node (ref "C36") (pin "1") (pinfunction "1_1") (pintype "passive"))
      (node (ref "D1") (pin "C") (pinfunction "C_C") (pintype "passive"))
      (node (ref "LSP1") (pin "MP") (pinfunction "MP_MP") (pintype "passive"))
      (node (ref "R57") (pin "2") (pinfunction "2_2") (pintype "passive"))
    )
    (net (code "7") (name "AN0") (class "Default")
      (node (ref "AN0") (pin "TP") (pinfunction "TP_TP") (pintype "input"))
      (node (ref "C8") (pin "1") (pinfunction "1_1") (pintype "passive"))
      (node (ref "MCU") (pin "95") (pinfunction "P100/AN00_95") (pintype "bidirectional"))
      (node (ref "R29") (pin "2") (pinfunction "2_2") (pintype "passive"))
    )
    (net (code "8") (name "AN1") (class "Default")
      (node (ref "AN1") (pin "TP") (pinfunction "TP_TP") (pintype "input"))
      (node (ref "C17") (pin "1") (pinfunction "1_1") (pintype "passive"))
      (node (ref "MCU") (pin "93") (pinfunction "P101/AN01_93") (pintype "bidirectional"))
      (node (ref "R12") (pin "2") (pinfunction "2_2") (pintype "passive"))
    )
    (net (code "9") (name "AN2") (class "Default")
      (node (ref "AN2") (pin "TP") (pinfunction "TP_TP") (pintype "input"))
      (node (ref "C7") (pin "1") (pinfunction "1_1") (pintype "passive"))
      (node (ref "CHGLED2") (pin "A") (pinfunction "A_A") (pintype "passive"))
      (node (ref "D4") (pin "3") (pinfunction "C_3") (pintype "passive"))
      (node (ref "MCU") (pin "92") (pinfunction "P102/AN02_92") (pintype "bidirectional"))
      (node (ref "R54") (pin "2") (pinfunction "2_2") (pintype "passive"))
      (node (ref "R57") (pin "1") (pinfunction "1_1") (pintype "passive"))
    )
    (net (code "10") (name "AN3") (class "Default")
      (node (ref "C4") (pin "1") (pinfunction "1_1") (pintype "passive"))
      (node (ref "MCU") (pin "91") (pinfunction "P103/AN03_91") (pintype "bidirectional"))
      (node (ref "R50") (pin "2") (pinfunction "2_2") (pintype "passive"))
      (node (ref "R51") (pin "2") (pinfunction "2_2") (pintype "passive"))
    )
    (net (code "11") (name "BALL_DETECT") (class "Default")
      (node (ref "COILGUN") (pin "3") (pinfunction "3_3") (pintype "passive"))
      (node (ref "MCU") (pin "25") (pinfunction "P73/CTS2/RTS2/TA1IN/V/TX8_25") (pintype "bidirectional"))
    )
    (net (code "12") (name "BUZZER") (class "Default")
      (node (ref "MCU") (pin "54") (pinfunction "P36/A14/[A14/D14]_54") (pintype "bidirectional"))
      (node (ref "R47") (pin "2") (pinfunction "2_2") (pintype "passive"))
    )
    (net (code "13") (name "CHARGE") (class "Default")
      (node (ref "CHARGE") (pin "TP") (pinfunction "TP_TP") (pintype "input"))
      (node (ref "CHG") (pin "A") (pinfunction "A_A") (pintype "passive"))
      (node (ref "LT3750") (pin "3") (pinfunction "CH_3") (pintype "bidirectional"))
      (node (ref "MCU") (pin "76") (pinfunction "P12/D10/IIO02(12)_76") (pintype "bidirectional"))
    )
    (net (code "14") (name "CLK") (class "Default")
      (node (ref "U1") (pin "14") (pinfunction "B6_14") (pintype "bidirectional"))
      (node (ref "X7") (pin "5") (pinfunction "5_5") (pintype "passive"))
    )
    (net (code "15") (name "CLK2") (class "Default")
      (node (ref "CLK2") (pin "TP") (pinfunction "TP_TP") (pintype "input"))
      (node (ref "MCU") (pin "26") (pinfunction "P72/CLK2/TA1OUT/V_26") (pintype "bidirectional"))
      (node (ref "U$5") (pin "14") (pinfunction "SCL/SPC_14") (pintype "bidirectional"))
    )
    (net (code "16") (name "CLK4") (class "Default")
      (node (ref "CLK4") (pin "TP") (pinfunction "TP_TP") (pintype "input"))
      (node (ref "J4") (pin "3") (pinfunction "MS_3") (pintype "passive"))
      (node (ref "MCU") (pin "100") (pinfunction "P95/ANEX0/CLK4_100") (pintype "bidirectional"))
    )
    (net (code "17") (name "CLK6") (class "Default")
      (node (ref "CLK6") (pin "TP") (pinfunction "TP_TP") (pintype "input"))
      (node (ref "MCU") (pin "47") (pinfunction "P45/CS2/A21/CLK6_47") (pintype "bidirectional"))
      (node (ref "U2") (pin "2") (pinfunction "SCL_2") (pintype "bidirectional"))
    )
    (net (code "18") (name "CLK_LCD") (class "Default")
      (node (ref "CLK_OLED") (pin "TP") (pinfunction "TP_TP") (pintype "input"))
      (node (ref "J1") (pin "13") (pinfunction "MS_13") (pintype "passive"))
      (node (ref "MCU") (pin "51") (pinfunction "P41/A17/CLK3_51") (pintype "bidirectional"))
    )
    (net (code "19") (name "CMD") (class "Default")
      (node (ref "U1") (pin "15") (pinfunction "B5_15") (pintype "bidirectional"))
      (node (ref "X7") (pin "2") (pinfunction "2_2") (pintype "passive"))
    )
    (net (code "20") (name "CNVSS") (class "Default")
      (node (ref "CNVSS") (pin "TP") (pinfunction "TP_TP") (pintype "input"))
      (node (ref "JP1") (pin "3") (pinfunction "3_3") (pintype "passive"))
      (node (ref "MCU") (pin "7") (pinfunction "CNVSS_7") (pintype "input"))
      (node (ref "R8") (pin "2") (pinfunction "2_2") (pintype "passive"))
      (node (ref "X1") (pin "3") (pinfunction "S_3") (pintype "passive"))
    )
    (net (code "21") (name "CS2") (class "Default")
      (node (ref "CS2") (pin "TP") (pinfunction "TP_TP") (pintype "input"))
      (node (ref "MCU") (pin "21") (pinfunction "P77/TA3IN/CLK5_21") (pintype "bidirectional"))
      (node (ref "U$5") (pin "7") (pinfunction "CS_7") (pintype "bidirectional"))
    )
    (net (code "22") (name "CS4") (class "Default")
      (node (ref "CS4") (pin "TP") (pinfunction "TP_TP") (pintype "input"))
      (node (ref "J4") (pin "4") (pinfunction "MS_4") (pintype "passive"))
      (node (ref "MCU") (pin "1") (pinfunction "P94/DA1/TB4IN/CTS4_1") (pintype "bidirectional"))
    )
    (net (code "23") (name "CS6") (class "Default")
      (node (ref "CS6") (pin "TP") (pinfunction "TP_TP") (pintype "input"))
      (node (ref "MCU") (pin "43") (pinfunction "P51/WR1/BC1_43") (pintype "bidirectional"))
      (node (ref "U2") (pin "5") (pinfunction "CS_5") (pintype "bidirectional"))
    )
    (net (code "24") (name "CS7") (class "Default")
      (node (ref "CS7") (pin "TP") (pinfunction "TP_TP") (pintype "input"))
      (node (ref "J5") (pin "4") (pinfunction "MS_4") (pintype "passive"))
      (node (ref "MCU") (pin "41") (pinfunction "P53/BCLK/CLKOUT_41") (pintype "bidirectional"))
    )
    (net (code "25") (name "CS_LCD") (class "Default")
      (node (ref "CS_OLED") (pin "TP") (pinfunction "TP_TP") (pintype "input"))
      (node (ref "J1") (pin "19") (pinfunction "MS_19") (pintype "passive"))
      (node (ref "MCU") (pin "37") (pinfunction "P57/RDY/CS3/RTS7_37") (pintype "bidirectional"))
    )
    (net (code "26") (name "DAT0") (class "Default")
      (node (ref "U1") (pin "16") (pinfunction "B4_16") (pintype "bidirectional"))
      (node (ref "X7") (pin "7") (pinfunction "7_7") (pintype "passive"))
    )
    (net (code "27") (name "DAT1") (class "Default")
      (node (ref "U1") (pin "17") (pinfunction "B3_17") (pintype "bidirectional"))
      (node (ref "X7") (pin "8") (pinfunction "8_8") (pintype "passive"))
    )
    (net (code "28") (name "DAT2") (class "Default")
      (node (ref "U1") (pin "18") (pinfunction "B2_18") (pintype "bidirectional"))
      (node (ref "X7") (pin "9") (pinfunction "9_9") (pintype "passive"))
    )
    (net (code "29") (name "DAT3") (class "Default")
      (node (ref "U1") (pin "20") (pinfunction "B1_20") (pintype "bidirectional"))
      (node (ref "X7") (pin "1") (pinfunction "1_1") (pintype "passive"))
    )
    (net (code "30") (name "DAT_LCD") (class "Default")
      (node (ref "DAT_OLED") (pin "TP") (pinfunction "TP_TP") (pintype "input"))
      (node (ref "J1") (pin "12") (pinfunction "MS_12") (pintype "passive"))
      (node (ref "MCU") (pin "49") (pinfunction "P43/A19/TX3_49") (pintype "bidirectional"))
    )
    (net (code "31") (name "DC_LCD") (class "Default")
      (node (ref "DC_OLED") (pin "TP") (pinfunction "TP_TP") (pintype "input"))
      (node (ref "J1") (pin "18") (pinfunction "MS_18") (pintype "passive"))
      (node (ref "MCU") (pin "52") (pinfunction "P40/A16/XTS3_52") (pintype "bidirectional"))
    )
    (net (code "32") (name "DONE") (class "Default")
      (node (ref "DONE") (pin "TP") (pinfunction "TP_TP") (pintype "input"))
      (node (ref "LT3750") (pin "2") (pinfunction "D_2") (pintype "bidirectional"))
      (node (ref "MCU") (pin "53") (pinfunction "P37/A15/[A15/D15]_53") (pintype "bidirectional"))
      (node (ref "R23") (pin "2") (pinfunction "2_2") (pintype "passive"))
    )
    (net (code "33") (name "DSR") (class "Default")
      (node (ref "DSR") (pin "TP") (pinfunction "TP_TP") (pintype "input"))
      (node (ref "IC4") (pin "26") (pinfunction "DSR_26") (pintype "input"))
      (node (ref "MCU") (pin "35") (pinfunction "P61/CLKO/TB1IN_35") (pintype "bidirectional"))
    )
    (net (code "34") (name "DTR") (class "Default")
      (node (ref "DTR") (pin "TP") (pinfunction "TP_TP") (pintype "input"))
      (node (ref "IC4") (pin "27") (pinfunction "DTR_27") (pintype "output"))
      (node (ref "MCU") (pin "36") (pinfunction "P60/CTSO/RTSO/TB0IN_36") (pintype "bidirectional"))
    )
    (net (code "35") (name "E8_BUSY") (class "Default")
      (node (ref "E8_BUSY") (pin "TP") (pinfunction "TP_TP") (pintype "input"))
      (node (ref "JP1") (pin "9") (pinfunction "9_9") (pintype "passive"))
      (node (ref "MCU") (pin "32") (pinfunction "P64/CTS1/RTS1/CLKS1/SS1_32") (pintype "bidirectional"))
      (node (ref "X1") (pin "9") (pinfunction "S_9") (pintype "passive"))
    )
    (net (code "36") (name "E8_CLK") (class "Default")
      (node (ref "E8_CLK") (pin "TP") (pinfunction "TP_TP") (pintype "input"))
      (node (ref "JP1") (pin "1") (pinfunction "1_1") (pintype "passive"))
      (node (ref "MCU") (pin "31") (pinfunction "P65/CLK1_31") (pintype "bidirectional"))
      (node (ref "X1") (pin "1") (pinfunction "S_1") (pintype "passive"))
    )
    (net (code "37") (name "E8_RX") (class "Default")
      (node (ref "E8_RX") (pin "TP") (pinfunction "TP_TP") (pintype "input"))
      (node (ref "JP1") (pin "11") (pinfunction "11_11") (pintype "passive"))
      (node (ref "MCU") (pin "30") (pinfunction "P66/RXD1/SCL1/STX1_30") (pintype "bidirectional"))
      (node (ref "X1") (pin "6") (pinfunction "S_6") (pintype "passive"))
    )
    (net (code "38") (name "E8_TX") (class "Default")
      (node (ref "E8_TX") (pin "TP") (pinfunction "TP_TP") (pintype "input"))
      (node (ref "JP1") (pin "5") (pinfunction "5_5") (pintype "passive"))
      (node (ref "MCU") (pin "29") (pinfunction "P67/TXD1/SDA1/SRX1_29") (pintype "bidirectional"))
      (node (ref "X1") (pin "5") (pinfunction "S_5") (pintype "passive"))
    )
    (net (code "39") (name "ENABLE_PANDA") (class "Default")
      (node (ref "ENABLEPANDA") (pin "A") (pinfunction "A_A") (pintype "passive"))
      (node (ref "EN_PANDA") (pin "TP") (pinfunction "TP_TP") (pintype "input"))
      (node (ref "MCU") (pin "55") (pinfunction "P35/A13/[A13/D13]_55") (pintype "bidirectional"))
      (node (ref "R35") (pin "2") (pinfunction "2_2") (pintype "passive"))
      (node (ref "U$3") (pin "3") (pinfunction "EN_3") (pintype "bidirectional"))
    )
    (net (code "40") (name "ERROR") (class "Default")
      (node (ref "ERROR") (pin "A") (pinfunction "A_A") (pintype "passive"))
      (node (ref "MCU") (pin "42") (pinfunction "P52/RD_42") (pintype "bidirectional"))
    )
    (net (code "41") (name "GND") (class "Default")
      (node (ref "10UF/16V") (pin "P$2") (pinfunction "-_P$2") (pintype "passive"))
      (node (ref "5V") (pin "2") (pinfunction "2_2") (pintype "passive"))
      (node (ref "C1") (pin "-") (pinfunction "-_-") (pintype "passive"))
      (node (ref "C100") (pin "-") (pinfunction "-_-") (pintype "passive"))
      (node (ref "C11") (pin "2") (pinfunction "2_2") (pintype "passive"))
      (node (ref "C12") (pin "-") (pinfunction "-_-") (pintype "passive"))
      (node (ref "C13") (pin "-") (pinfunction "-_-") (pintype "passive"))
      (node (ref "C14") (pin "-") (pinfunction "-_-") (pintype "passive"))
      (node (ref "C16") (pin "1") (pinfunction "1_1") (pintype "passive"))
      (node (ref "C17") (pin "2") (pinfunction "2_2") (pintype "passive"))
      (node (ref "C18") (pin "2") (pinfunction "2_2") (pintype "passive"))
      (node (ref "C19") (pin "2") (pinfunction "2_2") (pintype "passive"))
      (node (ref "C2") (pin "-") (pinfunction "-_-") (pintype "passive"))
      (node (ref "C22") (pin "1") (pinfunction "1_1") (pintype "passive"))
      (node (ref "C23") (pin "1") (pinfunction "1_1") (pintype "passive"))
      (node (ref "C24") (pin "1") (pinfunction "1_1") (pintype "passive"))
      (node (ref "C25") (pin "-") (pinfunction "-_-") (pintype "passive"))
      (node (ref "C26") (pin "2") (pinfunction "2_2") (pintype "passive"))
      (node (ref "C27") (pin "1") (pinfunction "1_1") (pintype "passive"))
      (node (ref "C28") (pin "2") (pinfunction "2_2") (pintype "passive"))
      (node (ref "C29") (pin "2") (pinfunction "2_2") (pintype "passive"))
      (node (ref "C3") (pin "2") (pinfunction "2_2") (pintype "passive"))
      (node (ref "C30") (pin "2") (pinfunction "2_2") (pintype "passive"))
      (node (ref "C31") (pin "2") (pinfunction "2_2") (pintype "passive"))
      (node (ref "C32") (pin "2") (pinfunction "2_2") (pintype "passive"))
      (node (ref "C33") (pin "-") (pinfunction "-_-") (pintype "passive"))
      (node (ref "C36") (pin "2") (pinfunction "2_2") (pintype "passive"))
      (node (ref "C4") (pin "2") (pinfunction "2_2") (pintype "passive"))
      (node (ref "C41") (pin "2") (pinfunction "2_2") (pintype "passive"))
      (node (ref "C45") (pin "2") (pinfunction "2_2") (pintype "passive"))
      (node (ref "C46") (pin "2") (pinfunction "2_2") (pintype "passive"))
      (node (ref "C48") (pin "2") (pinfunction "2_2") (pintype "passive"))
      (node (ref "C5") (pin "2") (pinfunction "2_2") (pintype "passive"))
      (node (ref "C51") (pin "2") (pinfunction "2_2") (pintype "passive"))
      (node (ref "C52") (pin "2") (pinfunction "2_2") (pintype "passive"))
      (node (ref "C53") (pin "2") (pinfunction "2_2") (pintype "passive"))
      (node (ref "C54") (pin "2") (pinfunction "2_2") (pintype "passive"))
      (node (ref "C55") (pin "2") (pinfunction "2_2") (pintype "passive"))
      (node (ref "C56") (pin "2") (pinfunction "2_2") (pintype "passive"))
      (node (ref "C58") (pin "2") (pinfunction "2_2") (pintype "passive"))
      (node (ref "C59") (pin "2") (pinfunction "2_2") (pintype "passive"))
      (node (ref "C60") (pin "2") (pinfunction "2_2") (pintype "passive"))
      (node (ref "C61") (pin "2") (pinfunction "2_2") (pintype "passive"))
      (node (ref "C62") (pin "2") (pinfunction "2_2") (pintype "passive"))
      (node (ref "C63") (pin "2") (pinfunction "2_2") (pintype "passive"))
      (node (ref "C64") (pin "2") (pinfunction "2_2") (pintype "passive"))
      (node (ref "C7") (pin "2") (pinfunction "2_2") (pintype "passive"))
      (node (ref "C71") (pin "1") (pinfunction "1_1") (pintype "passive"))
      (node (ref "C72") (pin "1") (pinfunction "1_1") (pintype "passive"))
      (node (ref "C8") (pin "2") (pinfunction "2_2") (pintype "passive"))
      (node (ref "C9") (pin "2") (pinfunction "2_2") (pintype "passive"))
      (node (ref "CHGLED1") (pin "C") (pinfunction "C_C") (pintype "passive"))
      (node (ref "COILGUN") (pin "1") (pinfunction "1_1") (pintype "passive"))
      (node (ref "D100") (pin "1") (pinfunction "A_1") (pintype "passive"))
      (node (ref "D2") (pin "2") (pinfunction "C2_2") (pintype "passive"))
      (node (ref "D4") (pin "1") (pinfunction "A_1") (pintype "passive"))
      (node (ref "GND") (pin "1") (pinfunction "P_1") (pintype "passive"))
      (node (ref "GND78") (pin "1") (pinfunction "P_1") (pintype "passive"))
      (node (ref "IC1") (pin "4") (pinfunction "GND_4") (pintype "power_in"))
      (node (ref "IC2") (pin "18") (pinfunction "GNDB_18") (pintype "power_in"))
      (node (ref "IC2") (pin "19") (pinfunction "GNDB_19") (pintype "power_in"))
      (node (ref "IC2") (pin "20") (pinfunction "GNDB_20") (pintype "power_in"))
      (node (ref "IC2") (pin "26") (pinfunction "GNDA_26") (pintype "power_in"))
      (node (ref "IC2") (pin "27") (pinfunction "GNDA_27") (pintype "power_in"))
      (node (ref "IC2") (pin "28") (pinfunction "GNDA_28") (pintype "power_in"))
      (node (ref "IC3") (pin "1") (pinfunction "GND_1") (pintype "power_in"))
      (node (ref "IC4") (pin "2") (pinfunction "GND_2") (pintype "power_in"))
      (node (ref "IC4") (pin "EXP") (pinfunction "GND_EXP") (pintype "power_in"))
      (node (ref "IC4") (pin "M") (pinfunction "GND_M") (pintype "power_in"))
      (node (ref "IC6") (pin "18") (pinfunction "GNDB_18") (pintype "power_in"))
      (node (ref "IC6") (pin "19") (pinfunction "GNDB_19") (pintype "power_in"))
      (node (ref "IC6") (pin "20") (pinfunction "GNDB_20") (pintype "power_in"))
      (node (ref "IC6") (pin "26") (pinfunction "GNDA_26") (pintype "power_in"))
      (node (ref "IC6") (pin "27") (pinfunction "GNDA_27") (pintype "power_in"))
      (node (ref "IC6") (pin "28") (pinfunction "GNDA_28") (pintype "power_in"))
      (node (ref "IC8") (pin "2") (pinfunction "GND_2") (pintype "passive"))
      (node (ref "IC8") (pin "4") (pinfunction "GND_4") (pintype "passive"))
      (node (ref "J1") (pin "1") (pinfunction "MSV_1") (pintype "passive"))
      (node (ref "J1") (pin "10") (pinfunction "MS_10") (pintype "passive"))
      (node (ref "J1") (pin "14") (pinfunction "MS_14") (pintype "passive"))
      (node (ref "J1") (pin "15") (pinfunction "MS_15") (pintype "passive"))
      (node (ref "J1") (pin "16") (pinfunction "MS_16") (pintype "passive"))
      (node (ref "J1") (pin "17") (pinfunction "MS_17") (pintype "passive"))
      (node (ref "J1") (pin "2") (pinfunction "MS_2") (pintype "passive"))
      (node (ref "J1") (pin "28") (pinfunction "MS_28") (pintype "passive"))
      (node (ref "J1") (pin "30") (pinfunction "MS_30") (pintype "passive"))
      (node (ref "J1") (pin "5") (pinfunction "MS_5") (pintype "passive"))
      (node (ref "J1") (pin "6") (pinfunction "MS_6") (pintype "passive"))
      (node (ref "J1") (pin "7") (pinfunction "MS_7") (pintype "passive"))
      (node (ref "J1") (pin "8") (pinfunction "MS_8") (pintype "passive"))
      (node (ref "J1") (pin "9") (pinfunction "MS_9") (pintype "passive"))
      (node (ref "J3") (pin "27") (pinfunction "27_27") (pintype "passive"))
      (node (ref "J3") (pin "28") (pinfunction "28_28") (pintype "passive"))
      (node (ref "J4") (pin "1") (pinfunction "MS_1") (pintype "passive"))
      (node (ref "J4") (pin "6") (pinfunction "MS_6") (pintype "passive"))
      (node (ref "J5") (pin "1") (pinfunction "MS_1") (pintype "passive"))
      (node (ref "J5") (pin "6") (pinfunction "MS_6") (pintype "passive"))
      (node (ref "J6") (pin "7") (pinfunction "7_7") (pintype "passive"))
      (node (ref "J6") (pin "8") (pinfunction "8_8") (pintype "passive"))
      (node (ref "JP1") (pin "10") (pinfunction "10_10") (pintype "passive"))
      (node (ref "JP1") (pin "12") (pinfunction "12_12") (pintype "passive"))
      (node (ref "JP1") (pin "14") (pinfunction "14_14") (pintype "passive"))
      (node (ref "JP1") (pin "2") (pinfunction "2_2") (pintype "passive"))
      (node (ref "JP1") (pin "6") (pinfunction "6_6") (pintype "passive"))
      (node (ref "JP2") (pin "GND") (pinfunction "GND_GND") (pintype "bidirectional"))
      (node (ref "LSP2") (pin "MP") (pinfunction "MP_MP") (pintype "passive"))
      (node (ref "LT3750") (pin "5") (pinfunction "GND_5") (pintype "bidirectional"))
      (node (ref "MCU") (pin "12") (pinfunction "VSS_12") (pintype "power_in"))
      (node (ref "MCU") (pin "62") (pinfunction "VSS_62") (pintype "power_in"))
      (node (ref "MCU") (pin "94") (pinfunction "AVSS_94") (pintype "input"))
      (node (ref "PAD10") (pin "1") (pinfunction "P_1") (pintype "passive"))
      (node (ref "PAD11") (pin "1") (pinfunction "P_1") (pintype "passive"))
      (node (ref "PAD12") (pin "1") (pinfunction "P_1") (pintype "passive"))
      (node (ref "PAD13") (pin "1") (pinfunction "P_1") (pintype "passive"))
      (node (ref "PAD14") (pin "1") (pinfunction "P_1") (pintype "passive"))
      (node (ref "PAD15") (pin "1") (pinfunction "P_1") (pintype "passive"))
      (node (ref "PAD16") (pin "1") (pinfunction "P_1") (pintype "passive"))
      (node (ref "PAD17") (pin "1") (pinfunction "P_1") (pintype "passive"))
      (node (ref "PAD18") (pin "1") (pinfunction "P_1") (pintype "passive"))
      (node (ref "PAD19") (pin "1") (pinfunction "P_1") (pintype "passive"))
      (node (ref "PAD20") (pin "1") (pinfunction "P_1") (pintype "passive"))
      (node (ref "PAD21") (pin "1") (pinfunction "P_1") (pintype "passive"))
      (node (ref "PAD22") (pin "1") (pinfunction "P_1") (pintype "passive"))
      (node (ref "PAD23") (pin "1") (pinfunction "P_1") (pintype "passive"))
      (node (ref "PAD24") (pin "1") (pinfunction "P_1") (pintype "passive"))
      (node (ref "PAD3") (pin "1") (pinfunction "P_1") (pintype "passive"))
      (node (ref "PAD4") (pin "1") (pinfunction "P_1") (pintype "passive"))
      (node (ref "PAD7") (pin "1") (pinfunction "P_1") (pintype "passive"))
      (node (ref "PAD8") (pin "1") (pinfunction "P_1") (pintype "passive"))
      (node (ref "PAD9") (pin "1") (pinfunction "P_1") (pintype "passive"))
      (node (ref "PANDA") (pin "2") (pinfunction "2_2") (pintype "passive"))
      (node (ref "Q3") (pin "2") (pinfunction "E_2") (pintype "passive"))
      (node (ref "Q4") (pin "3") (pinfunction "D_3") (pintype "passive"))
      (node (ref "Q5") (pin "3") (pinfunction "D_3") (pintype "passive"))
      (node (ref "R10") (pin "1") (pinfunction "1_1") (pintype "passive"))
      (node (ref "R11") (pin "1") (pinfunction "1_1") (pintype "passive"))
      (node (ref "R111") (pin "1") (pinfunction "1_1") (pintype "passive"))
      (node (ref "R13") (pin "2") (pinfunction "2_2") (pintype "passive"))
      (node (ref "R15") (pin "1") (pinfunction "1_1") (pintype "passive"))
      (node (ref "R18") (pin "2") (pinfunction "2_2") (pintype "passive"))
      (node (ref "R19") (pin "1") (pinfunction "1_1") (pintype "passive"))
      (node (ref "R20") (pin "2") (pinfunction "2_2") (pintype "passive"))
      (node (ref "R22") (pin "2") (pinfunction "2_2") (pintype "passive"))
      (node (ref "R26") (pin "2") (pinfunction "2_2") (pintype "passive"))
      (node (ref "R30") (pin "2") (pinfunction "2_2") (pintype "passive"))
      (node (ref "R35") (pin "1") (pinfunction "1_1") (pintype "passive"))
      (node (ref "R38") (pin "1") (pinfunction "1_1") (pintype "passive"))
      (node (ref "R39") (pin "1") (pinfunction "1_1") (pintype "passive"))
      (node (ref "R40") (pin "1") (pinfunction "1_1") (pintype "passive"))
      (node (ref "R41") (pin "1") (pinfunction "1_1") (pintype "passive"))
      (node (ref "R42") (pin "2") (pinfunction "2_2") (pintype "passive"))
      (node (ref "R43") (pin "1") (pinfunction "1_1") (pintype "passive"))
      (node (ref "R49") (pin "1") (pinfunction "1_1") (pintype "passive"))
      (node (ref "R51") (pin "1") (pinfunction "1_1") (pintype "passive"))
      (node (ref "R52") (pin "1") (pinfunction "1_1") (pintype "passive"))
      (node (ref "R54") (pin "1") (pinfunction "1_1") (pintype "passive"))
      (node (ref "R56") (pin "1") (pinfunction "1_1") (pintype "passive"))
      (node (ref "R8") (pin "1") (pinfunction "1_1") (pintype "passive"))
      (node (ref "R9") (pin "1") (pinfunction "1_1") (pintype "passive"))
      (node (ref "SG2") (pin "2") (pinfunction "2_2") (pintype "passive"))
      (node (ref "U$1") (pin "1") (pinfunction "1_1") (pintype "bidirectional"))
      (node (ref "U$2") (pin "2") (pinfunction "GND_2") (pintype "power_in"))
      (node (ref "U$3") (pin "7") (pinfunction "GND_7") (pintype "bidirectional"))
      (node (ref "U$5") (pin "10") (pinfunction "NC_10") (pintype "bidirectional"))
      (node (ref "U$5") (pin "11") (pinfunction "NC_11") (pintype "bidirectional"))
      (node (ref "U$5") (pin "2") (pinfunction "GND_2") (pintype "bidirectional"))
      (node (ref "U$5") (pin "3") (pinfunction "NC_3") (pintype "bidirectional"))
      (node (ref "U$5") (pin "4") (pinfunction "IADDR0_4") (pintype "bidirectional"))
      (node (ref "U$5") (pin "5") (pinfunction "GND_5") (pintype "bidirectional"))
      (node (ref "U1") (pin "11") (pinfunction "GND_11") (pintype "bidirectional"))
      (node (ref "U2") (pin "10") (pinfunction "RSVDG_10") (pintype "bidirectional"))
      (node (ref "U2") (pin "11") (pinfunction "RSDVG_11") (pintype "bidirectional"))
      (node (ref "U2") (pin "12") (pinfunction "RSVDG_12") (pintype "bidirectional"))
      (node (ref "U2") (pin "13") (pinfunction "GND_13") (pintype "bidirectional"))
      (node (ref "U2") (pin "8") (pinfunction "RSVDG_8") (pintype "bidirectional"))
      (node (ref "U2") (pin "9") (pinfunction "RSVDG_9") (pintype "bidirectional"))
      (node (ref "X1") (pin "2") (pinfunction "S_2") (pintype "passive"))
      (node (ref "X4") (pin "GND") (pinfunction "GND_GND") (pintype "bidirectional"))
      (node (ref "X7") (pin "4") (pinfunction "4_4") (pintype "passive"))
      (node (ref "X7") (pin "6") (pinfunction "6_6") (pintype "passive"))
      (node (ref "X7") (pin "SW3") (pinfunction "SW3_SW3") (pintype "passive"))
      (node (ref "Y2") (pin "2") (pinfunction "2_2") (pintype "passive"))
    )
    (net (code "42") (name "HOLD") (class "Default")
      (node (ref "HOLD") (pin "TP") (pinfunction "TP_TP") (pintype "input"))
      (node (ref "J5") (pin "3") (pinfunction "MS_3") (pintype "passive"))
      (node (ref "JP1") (pin "4") (pinfunction "4_4") (pintype "passive"))
      (node (ref "MCU") (pin "39") (pinfunction "P55/HOLD/CLK7_39") (pintype "bidirectional"))
      (node (ref "R1") (pin "1") (pinfunction "1_1") (pintype "passive"))
      (node (ref "X1") (pin "4") (pinfunction "S_4") (pintype "passive"))
    )
    (net (code "43") (name "INT0") (class "Default")
      (node (ref "INT0") (pin "TP") (pinfunction "TP_TP") (pintype "input"))
      (node (ref "MCU") (pin "18") (pinfunction "P82/INT0_18") (pintype "bidirectional"))
      (node (ref "U$5") (pin "8") (pinfunction "INT1/DRDY_8") (pintype "bidirectional"))
    )
    (net (code "44") (name "INT1") (class "Default")
      (node (ref "INT1") (pin "TP") (pinfunction "TP_TP") (pintype "input"))
      (node (ref "MCU") (pin "17") (pinfunction "P83/INT1_17") (pintype "bidirectional"))
      (node (ref "U2") (pin "7") (pinfunction "INT1_7") (pintype "bidirectional"))
    )
    (net (code "45") (name "INT2") (class "Default")
      (node (ref "INT2") (pin "TP") (pinfunction "TP_TP") (pintype "input"))
      (node (ref "MCU") (pin "16") (pinfunction "P84/INT2_16") (pintype "bidirectional"))
      (node (ref "U2") (pin "6") (pinfunction "INT2_6") (pintype "bidirectional"))
    )
    (net (code "46") (name "JOY_CENT") (class "Default")
      (node (ref "JOY_CENT") (pin "TP") (pinfunction "TP_TP") (pintype "input"))
      (node (ref "JP2") (pin "CTR") (pinfunction "CENT_CTR") (pintype "bidirectional"))
      (node (ref "MCU") (pin "71") (pinfunction "P17/D15/INT5/IIO07(17)_71") (pintype "bidirectional"))
    )
    (net (code "47") (name "JOY_DOWN") (class "Default")
      (node (ref "JOY_DOWN") (pin "TP") (pinfunction "TP_TP") (pintype "input"))
      (node (ref "JP2") (pin "D") (pinfunction "DOWN_D") (pintype "bidirectional"))
      (node (ref "MCU") (pin "74") (pinfunction "P14/D12/IIO04(14)_74") (pintype "bidirectional"))
    )
    (net (code "48") (name "JOY_LEFT") (class "Default")
      (node (ref "JOY_LEFT") (pin "TP") (pinfunction "TP_TP") (pintype "input"))
      (node (ref "JP2") (pin "B") (pinfunction "LEFT_B") (pintype "bidirectional"))
      (node (ref "MCU") (pin "73") (pinfunction "P15/D13/INT3/IIO05(15)_73") (pintype "bidirectional"))
    )
    (net (code "49") (name "JOY_RIGHT") (class "Default")
      (node (ref "JOY_RIGHT") (pin "TP") (pinfunction "TP_TP") (pintype "input"))
      (node (ref "JP2") (pin "C") (pinfunction "RIGHT_C") (pintype "bidirectional"))
      (node (ref "MCU") (pin "72") (pinfunction "P16/D14/INT4/IIO06(16)_72") (pintype "bidirectional"))
    )
    (net (code "50") (name "JOY_UP") (class "Default")
      (node (ref "JOY_UP") (pin "TP") (pinfunction "TP_TP") (pintype "input"))
      (node (ref "JP2") (pin "A") (pinfunction "UP_A") (pintype "bidirectional"))
      (node (ref "MCU") (pin "75") (pinfunction "P13/D11/IIO03(13)_75") (pintype "bidirectional"))
    )
    (net (code "51") (name "KICK") (class "Default")
      (node (ref "COILGUN") (pin "2") (pinfunction "2_2") (pintype "passive"))
      (node (ref "MCU") (pin "23") (pinfunction "P75/TA2IN/W/RX8_23") (pintype "bidirectional"))
    )
    (net (code "52") (name "LED1") (class "Default")
      (node (ref "HEARTBEAT") (pin "A") (pinfunction "A_A") (pintype "passive"))
      (node (ref "MCU") (pin "57") (pinfunction "P33/A11/[A11/D11]_57") (pintype "bidirectional"))
    )
    (net (code "53") (name "LEFT_DIAGA") (class "Default")
      (node (ref "L_ENA") (pin "TP") (pinfunction "TP_TP") (pintype "input"))
      (node (ref "MCU") (pin "64") (pinfunction "P26/AN26/A6/[A6/D6]_64") (pintype "bidirectional"))
      (node (ref "R33") (pin "1") (pinfunction "1_1") (pintype "passive"))
    )
    (net (code "54") (name "LEFT_DIAGB") (class "Default")
      (node (ref "L_ENB") (pin "TP") (pinfunction "TP_TP") (pintype "input"))
      (node (ref "MCU") (pin "63") (pinfunction "P27/AN27/A7/[A7/D7]_63") (pintype "bidirectional"))
      (node (ref "R34") (pin "1") (pinfunction "1_1") (pintype "passive"))
    )
    (net (code "55") (name "LEFT_INA") (class "Default")
      (node (ref "L_INA") (pin "TP") (pinfunction "TP_TP") (pintype "input"))
      (node (ref "MCU") (pin "68") (pinfunction "P22/AN22/A2/[A2/D2]_68") (pintype "bidirectional"))
      (node (ref "R31") (pin "1") (pinfunction "1_1") (pintype "passive"))
    )
    (net (code "56") (name "LEFT_INB") (class "Default")
      (node (ref "L_INB") (pin "TP") (pinfunction "TP_TP") (pintype "input"))
      (node (ref "MCU") (pin "67") (pinfunction "P23/AN23/A3/[A3/D3]_67") (pintype "bidirectional"))
      (node (ref "R32") (pin "1") (pinfunction "1_1") (pintype "passive"))
    )
    (net (code "57") (name "LEFT_PWM") (class "Default")
      (node (ref "LEFTPWM") (pin "A") (pinfunction "A_A") (pintype "passive"))
      (node (ref "L_PWM") (pin "TP") (pinfunction "TP_TP") (pintype "input"))
      (node (ref "MCU") (pin "58") (pinfunction "P32/A10/[A10/D10]_58") (pintype "bidirectional"))
      (node (ref "R36") (pin "1") (pinfunction "1_1") (pintype "passive"))
    )
    (net (code "58") (name "LM2733FB") (class "Default")
      (node (ref "C49") (pin "2") (pinfunction "2_2") (pintype "passive"))
      (node (ref "R14") (pin "1") (pinfunction "1_1") (pintype "passive"))
      (node (ref "R15") (pin "2") (pinfunction "2_2") (pintype "passive"))
      (node (ref "TP50") (pin "TP") (pinfunction "TP_TP") (pintype "input"))
      (node (ref "U$2") (pin "3") (pinfunction "FB_3") (pintype "input"))
    )
    (net (code "59") (name "MELEXIS_EN") (class "Default")
      (node (ref "EN_MELEXIS") (pin "A") (pinfunction "A_A") (pintype "passive"))
      (node (ref "IC1") (pin "3") (pinfunction "~{EN}_3") (pintype "input"))
      (node (ref "MCU") (pin "61") (pinfunction "P30/A8/[A8/D8]_61") (pintype "bidirectional"))
      (node (ref "R58") (pin "2") (pinfunction "2_2") (pintype "passive"))
    )
    (net (code "60") (name "MOTOR1CS") (class "Default")
      (node (ref "IC2") (pin "9") (pinfunction "CS_9") (pintype "bidirectional"))
      (node (ref "R12") (pin "1") (pinfunction "1_1") (pintype "passive"))
      (node (ref "R13") (pin "1") (pinfunction "1_1") (pintype "passive"))
    )
    (net (code "61") (name "MOTOR1DIAGA") (class "Default")
      (node (ref "IC2") (pin "6") (pinfunction "DIAGA_6") (pintype "open_collector"))
      (node (ref "R25") (pin "1") (pinfunction "1_1") (pintype "passive"))
      (node (ref "R5") (pin "2") (pinfunction "2_2") (pintype "passive"))
    )
    (net (code "62") (name "MOTOR1DIAGB") (class "Default")
      (node (ref "IC2") (pin "10") (pinfunction "DIAGB_10") (pintype "open_collector"))
      (node (ref "R2") (pin "1") (pinfunction "1_1") (pintype "passive"))
      (node (ref "R6") (pin "2") (pinfunction "2_2") (pintype "passive"))
    )
    (net (code "63") (name "MOTOR1L") (class "Default")
      (node (ref "C20") (pin "1") (pinfunction "1_1") (pintype "passive"))
      (node (ref "C21") (pin "1") (pinfunction "1_1") (pintype "passive"))
      (node (ref "IC2") (pin "1") (pinfunction "OUTA_1") (pintype "output"))
      (node (ref "IC2") (pin "25") (pinfunction "OUTA_25") (pintype "passive"))
      (node (ref "IC2") (pin "30") (pinfunction "OUTA_30") (pintype "passive"))
      (node (ref "IC2") (pin "OUTA") (pinfunction "OUTA_OUTA") (pintype "passive"))
      (node (ref "IC2") (pin "OUTA@1") (pinfunction "OUTA_OUTA@1") (pintype "passive"))
      (node (ref "M1L") (pin "A") (pinfunction "A_A") (pintype "passive"))
      (node (ref "PAD56") (pin "1") (pinfunction "P_1") (pintype "passive"))
      (node (ref "PAD57") (pin "1") (pinfunction "P_1") (pintype "passive"))
      (node (ref "PAD58") (pin "1") (pinfunction "P_1") (pintype "passive"))
      (node (ref "PAD59") (pin "1") (pinfunction "P_1") (pintype "passive"))
      (node (ref "PAD60") (pin "1") (pinfunction "P_1") (pintype "passive"))
      (node (ref "PAD61") (pin "1") (pinfunction "P_1") (pintype "passive"))
      (node (ref "PAD62") (pin "1") (pinfunction "P_1") (pintype "passive"))
      (node (ref "PAD63") (pin "1") (pinfunction "P_1") (pintype "passive"))
      (node (ref "PAD64") (pin "1") (pinfunction "P_1") (pintype "passive"))
      (node (ref "PAD94") (pin "1") (pinfunction "P_1") (pintype "passive"))
    )
    (net (code "64") (name "MOTOR1PWM") (class "Default")
      (node (ref "IC2") (pin "8") (pinfunction "PWM_8") (pintype "input"))
      (node (ref "R7") (pin "2") (pinfunction "2_2") (pintype "passive"))
    )
    (net (code "65") (name "MOTOR1R") (class "Default")
      (node (ref "C20") (pin "2") (pinfunction "2_2") (pintype "passive"))
      (node (ref "C21") (pin "2") (pinfunction "2_2") (pintype "passive"))
      (node (ref "IC2") (pin "15") (pinfunction "OUTB_15") (pintype "output"))
      (node (ref "IC2") (pin "16") (pinfunction "OUTB_16") (pintype "passive"))
      (node (ref "IC2") (pin "21") (pinfunction "OUTB_21") (pintype "passive"))
      (node (ref "IC2") (pin "OUTB") (pinfunction "OUTB_OUTB") (pintype "passive"))
      (node (ref "IC2") (pin "OUTB@1") (pinfunction "OUTB_OUTB@1") (pintype "passive"))
      (node (ref "M1R") (pin "A") (pinfunction "A_A") (pintype "passive"))
      (node (ref "PAD65") (pin "1") (pinfunction "P_1") (pintype "passive"))
      (node (ref "PAD66") (pin "1") (pinfunction "P_1") (pintype "passive"))
      (node (ref "PAD67") (pin "1") (pinfunction "P_1") (pintype "passive"))
      (node (ref "PAD68") (pin "1") (pinfunction "P_1") (pintype "passive"))
      (node (ref "PAD69") (pin "1") (pinfunction "P_1") (pintype "passive"))
      (node (ref "PAD70") (pin "1") (pinfunction "P_1") (pintype "passive"))
      (node (ref "PAD71") (pin "1") (pinfunction "P_1") (pintype "passive"))
      (node (ref "PAD72") (pin "1") (pinfunction "P_1") (pintype "passive"))
      (node (ref "PAD73") (pin "1") (pinfunction "P_1") (pintype "passive"))
      (node (ref "PAD95") (pin "1") (pinfunction "P_1") (pintype "passive"))
    )
    (net (code "66") (name "MOTOR2CS") (class "Default")
      (node (ref "IC6") (pin "9") (pinfunction "CS_9") (pintype "bidirectional"))
      (node (ref "R29") (pin "1") (pinfunction "1_1") (pintype "passive"))
      (node (ref "R30") (pin "1") (pinfunction "1_1") (pintype "passive"))
    )
    (net (code "67") (name "MOTOR2DIAGA") (class "Default")
      (node (ref "IC6") (pin "6") (pinfunction "DIAGA_6") (pintype "open_collector"))
      (node (ref "R27") (pin "1") (pinfunction "1_1") (pintype "passive"))
      (node (ref "R33") (pin "2") (pinfunction "2_2") (pintype "passive"))
    )
    (net (code "68") (name "MOTOR2DIAGB") (class "Default")
      (node (ref "IC6") (pin "10") (pinfunction "DIAGB_10") (pintype "open_collector"))
      (node (ref "R28") (pin "1") (pinfunction "1_1") (pintype "passive"))
      (node (ref "R34") (pin "2") (pinfunction "2_2") (pintype "passive"))
    )
    (net (code "69") (name "MOTOR2INA") (class "Default")
      (node (ref "IC6") (pin "5") (pinfunction "INA_5") (pintype "input"))
      (node (ref "R31") (pin "2") (pinfunction "2_2") (pintype "passive"))
    )
    (net (code "70") (name "MOTOR2INB") (class "Default")
      (node (ref "IC6") (pin "11") (pinfunction "INB_11") (pintype "input"))
      (node (ref "R32") (pin "2") (pinfunction "2_2") (pintype "passive"))
    )
    (net (code "71") (name "MOTOR2L") (class "Default")
      (node (ref "C42") (pin "1") (pinfunction "1_1") (pintype "passive"))
      (node (ref "C43") (pin "1") (pinfunction "1_1") (pintype "passive"))
      (node (ref "IC6") (pin "1") (pinfunction "OUTA_1") (pintype "output"))
      (node (ref "IC6") (pin "25") (pinfunction "OUTA_25") (pintype "passive"))
      (node (ref "IC6") (pin "30") (pinfunction "OUTA_30") (pintype "passive"))
      (node (ref "IC6") (pin "OUTA") (pinfunction "OUTA_OUTA") (pintype "passive"))
      (node (ref "IC6") (pin "OUTA@1") (pinfunction "OUTA_OUTA@1") (pintype "passive"))
      (node (ref "M2L") (pin "A") (pinfunction "A_A") (pintype "passive"))
      (node (ref "PAD74") (pin "1") (pinfunction "P_1") (pintype "passive"))
      (node (ref "PAD75") (pin "1") (pinfunction "P_1") (pintype "passive"))
      (node (ref "PAD76") (pin "1") (pinfunction "P_1") (pintype "passive"))
      (node (ref "PAD77") (pin "1") (pinfunction "P_1") (pintype "passive"))
      (node (ref "PAD78") (pin "1") (pinfunction "P_1") (pintype "passive"))
      (node (ref "PAD79") (pin "1") (pinfunction "P_1") (pintype "passive"))
      (node (ref "PAD80") (pin "1") (pinfunction "P_1") (pintype "passive"))
      (node (ref "PAD81") (pin "1") (pinfunction "P_1") (pintype "passive"))
      (node (ref "PAD82") (pin "1") (pinfunction "P_1") (pintype "passive"))
      (node (ref "PAD92") (pin "1") (pinfunction "P_1") (pintype "passive"))
    )
    (net (code "72") (name "MOTOR2PWM") (class "Default")
      (node (ref "IC6") (pin "8") (pinfunction "PWM_8") (pintype "input"))
      (node (ref "R36") (pin "2") (pinfunction "2_2") (pintype "passive"))
    )
    (net (code "73") (name "MOTOR2R") (class "Default")
      (node (ref "C42") (pin "2") (pinfunction "2_2") (pintype "passive"))
      (node (ref "C43") (pin "2") (pinfunction "2_2") (pintype "passive"))
      (node (ref "IC6") (pin "15") (pinfunction "OUTB_15") (pintype "output"))
      (node (ref "IC6") (pin "16") (pinfunction "OUTB_16") (pintype "passive"))
      (node (ref "IC6") (pin "21") (pinfunction "OUTB_21") (pintype "passive"))
      (node (ref "IC6") (pin "OUTB") (pinfunction "OUTB_OUTB") (pintype "passive"))
      (node (ref "IC6") (pin "OUTB@1") (pinfunction "OUTB_OUTB@1") (pintype "passive"))
      (node (ref "M2R") (pin "A") (pinfunction "A_A") (pintype "passive"))
      (node (ref "PAD83") (pin "1") (pinfunction "P_1") (pintype "passive"))
      (node (ref "PAD84") (pin "1") (pinfunction "P_1") (pintype "passive"))
      (node (ref "PAD85") (pin "1") (pinfunction "P_1") (pintype "passive"))
      (node (ref "PAD86") (pin "1") (pinfunction "P_1") (pintype "passive"))
      (node (ref "PAD87") (pin "1") (pinfunction "P_1") (pintype "passive"))
      (node (ref "PAD88") (pin "1") (pinfunction "P_1") (pintype "passive"))
      (node (ref "PAD89") (pin "1") (pinfunction "P_1") (pintype "passive"))
      (node (ref "PAD90") (pin "1") (pinfunction "P_1") (pintype "passive"))
      (node (ref "PAD91") (pin "1") (pinfunction "P_1") (pintype "passive"))
      (node (ref "PAD93") (pin "1") (pinfunction "P_1") (pintype "passive"))
    )
    (net (code "74") (name "N$16") (class "Default")
      (node (ref "J6") (pin "19") (pinfunction "19_19") (pintype "passive"))
      (node (ref "PANDA2") (pin "A") (pinfunction "A_A") (pintype "passive"))
    )
    (net (code "75") (name "N$19") (class "Default")
      (node (ref "J6") (pin "17") (pinfunction "17_17") (pintype "passive"))
      (node (ref "PANDA1") (pin "A") (pinfunction "A_A") (pintype "passive"))
    )
    (net (code "76") (name "N$46") (class "Default")
      (node (ref "J1") (pin "22") (pinfunction "MS_22") (pintype "passive"))
      (node (ref "R18") (pin "1") (pinfunction "1_1") (pintype "passive"))
      (node (ref "TP9") (pin "TP") (pinfunction "TP_TP") (pintype "input"))
    )
    (net (code "77") (name "N$47") (class "Default")
      (node (ref "FB_OLED") (pin "TP") (pinfunction "TP_TP") (pintype "input"))
      (node (ref "J1") (pin "27") (pinfunction "MS_27") (pintype "passive"))
      (node (ref "R17") (pin "2") (pinfunction "2_2") (pintype "passive"))
    )
    (net (code "78") (name "NSD") (class "Default")
      (node (ref "MCU") (pin "6") (pinfunction "NSD_6") (pintype "input"))
      (node (ref "R45") (pin "2") (pinfunction "2_2") (pintype "passive"))
    )
    (net (code "79") (name "Net-(C10-Pad2)") (class "Default")
      (node (ref "C10") (pin "2") (pinfunction "2_2") (pintype "passive"))
      (node (ref "R11") (pin "2") (pinfunction "2_2") (pintype "passive"))
    )
    (net (code "80") (name "Net-(C47-Pad2)") (class "Default")
      (node (ref "C47") (pin "2") (pinfunction "2_2") (pintype "passive"))
      (node (ref "R9") (pin "2") (pinfunction "2_2") (pintype "passive"))
    )
    (net (code "81") (name "Net-(CHG-PadC)") (class "Default")
      (node (ref "CHG") (pin "C") (pinfunction "C_C") (pintype "passive"))
      (node (ref "R111") (pin "2") (pinfunction "2_2") (pintype "passive"))
    )
    (net (code "82") (name "Net-(CHGLED1-PadA)") (class "Default")
      (node (ref "CHGLED1") (pin "A") (pinfunction "A_A") (pintype "passive"))
      (node (ref "CHGLED2") (pin "C") (pinfunction "C_C") (pintype "passive"))
    )
    (net (code "83") (name "Net-(D1-PadA)") (class "Default")
      (node (ref "D1") (pin "A") (pinfunction "A_A") (pintype "passive"))
      (node (ref "U$1") (pin "12") (pinfunction "12_12") (pintype "bidirectional"))
    )
    (net (code "84") (name "Net-(D2-A1)") (class "Default")
      (node (ref "D2") (pin "1") (pinfunction "A1_1") (pintype "passive"))
      (node (ref "R17") (pin "1") (pinfunction "1_1") (pintype "passive"))
    )
    (net (code "85") (name "Net-(D100-C)") (class "Default")
      (node (ref "BOOT") (pin "TP") (pinfunction "TP_TP") (pintype "input"))
      (node (ref "C15") (pin "1") (pinfunction "1_1") (pintype "passive"))
      (node (ref "D100") (pin "3") (pinfunction "C_3") (pintype "passive"))
      (node (ref "L1") (pin "1") (pinfunction "1_1") (pintype "passive"))
      (node (ref "U$3") (pin "8") (pinfunction "PH_8") (pintype "bidirectional"))
    )
    (net (code "86") (name "Net-(ENABLEPANDA-PadC)") (class "Default")
      (node (ref "ENABLEPANDA") (pin "C") (pinfunction "C_C") (pintype "passive"))
      (node (ref "R40") (pin "2") (pinfunction "2_2") (pintype "passive"))
    )
    (net (code "87") (name "Net-(EN_MELEXIS-PadC)") (class "Default")
      (node (ref "EN_MELEXIS") (pin "C") (pinfunction "C_C") (pintype "passive"))
      (node (ref "R49") (pin "2") (pinfunction "2_2") (pintype "passive"))
    )
    (net (code "88") (name "Net-(ERROR-PadC)") (class "Default")
      (node (ref "ERROR") (pin "C") (pinfunction "C_C") (pintype "passive"))
      (node (ref "R52") (pin "2") (pinfunction "2_2") (pintype "passive"))
    )
    (net (code "89") (name "Net-(HEARTBEAT-PadC)") (class "Default")
      (node (ref "HEARTBEAT") (pin "C") (pinfunction "C_C") (pintype "passive"))
      (node (ref "R19") (pin "2") (pinfunction "2_2") (pintype "passive"))
    )
    (net (code "90") (name "Net-(IC2-INA)") (class "Default")
      (node (ref "IC2") (pin "5") (pinfunction "INA_5") (pintype "input"))
      (node (ref "R3") (pin "2") (pinfunction "2_2") (pintype "passive"))
    )
    (net (code "91") (name "Net-(IC2-INB)") (class "Default")
      (node (ref "IC2") (pin "11") (pinfunction "INB_11") (pintype "input"))
      (node (ref "R4") (pin "2") (pinfunction "2_2") (pintype "passive"))
    )
    (net (code "92") (name "Net-(J1Y-MS)") (class "Default")
      (node (ref "C53") (pin "1") (pinfunction "1_1") (pintype "passive"))
      (node (ref "J1") (pin "4") (pinfunction "MS_4") (pintype "passive"))
      (node (ref "TP82") (pin "TP") (pinfunction "TP_TP") (pintype "input"))
    )
    (net (code "93") (name "Net-(L2-2)") (class "Default")
      (node (ref "D3") (pin "A") (pinfunction "A_A") (pintype "passive"))
      (node (ref "L2") (pin "1") (pinfunction "2_1") (pintype "passive"))
      (node (ref "U$2") (pin "1") (pinfunction "VOUT_1") (pintype "output"))
    )
    (net (code "94") (name "Net-(L3-1)") (class "Default")
      (node (ref "C55") (pin "1") (pinfunction "1_1") (pintype "passive"))
      (node (ref "L3") (pin "2") (pinfunction "1_2") (pintype "passive"))
      (node (ref "MCU") (pin "96") (pinfunction "VREF_96") (pintype "input"))
      (node (ref "MCU") (pin "97") (pinfunction "AVCC_97") (pintype "input"))
    )
    (net (code "95") (name "Net-(LEFTPWM-PadC)") (class "Default")
      (node (ref "LEFTPWM") (pin "C") (pinfunction "C_C") (pintype "passive"))
      (node (ref "R39") (pin "2") (pinfunction "2_2") (pintype "passive"))
    )
    (net (code "96") (name "Net-(LT3750-G)") (class "Default")
      (node (ref "G") (pin "TP") (pinfunction "TP_TP") (pintype "input"))
      (node (ref "LT3750") (pin "7") (pinfunction "G_7") (pintype "bidirectional"))
      (node (ref "U$102") (pin "4") (pinfunction "G_4") (pintype "passive"))
    )
    (net (code "97") (name "Net-(LT3750-RBG)") (class "Default")
      (node (ref "C32") (pin "1") (pinfunction "1_1") (pintype "passive"))
      (node (ref "LT3750") (pin "10") (pinfunction "RBG_10") (pintype "bidirectional"))
      (node (ref "R22") (pin "1") (pinfunction "1_1") (pintype "passive"))
      (node (ref "RBG") (pin "TP") (pinfunction "TP_TP") (pintype "input"))
    )
    (net (code "98") (name "Net-(LT3750-RD)") (class "Default")
      (node (ref "LT3750") (pin "8") (pinfunction "RD_8") (pintype "bidirectional"))
      (node (ref "R21") (pin "1") (pinfunction "1_1") (pintype "passive"))
      (node (ref "RD") (pin "TP") (pinfunction "TP_TP") (pintype "input"))
    )
    (net (code "99") (name "Net-(LT3750-RV)") (class "Default")
      (node (ref "LT3750") (pin "9") (pinfunction "RV_9") (pintype "bidirectional"))
      (node (ref "R24") (pin "1") (pinfunction "1_1") (pintype "passive"))
      (node (ref "RV") (pin "TP") (pinfunction "TP_TP") (pintype "input"))
    )
    (net (code "100") (name "Net-(LT3750-S)") (class "Default")
      (node (ref "LT3750") (pin "6") (pinfunction "S_6") (pintype "bidirectional"))
      (node (ref "R20") (pin "1") (pinfunction "1_1") (pintype "passive"))
      (node (ref "S") (pin "TP") (pinfunction "TP_TP") (pintype "input"))
      (node (ref "U$102") (pin "1") (pinfunction "S_1") (pintype "passive"))
      (node (ref "U$102") (pin "2") (pinfunction "S_2") (pintype "passive"))
      (node (ref "U$102") (pin "3") (pinfunction "S_3") (pintype "passive"))
    )
    (net (code "101") (name "Net-(M1L-PadC)") (class "Default")
      (node (ref "M1L") (pin "C") (pinfunction "C_C") (pintype "passive"))
      (node (ref "M1R") (pin "C") (pinfunction "C_C") (pintype "passive"))
      (node (ref "R56") (pin "2") (pinfunction "2_2") (pintype "passive"))
    )
    (net (code "102") (name "Net-(M2L-PadC)") (class "Default")
      (node (ref "M2L") (pin "C") (pinfunction "C_C") (pintype "passive"))
      (node (ref "M2R") (pin "C") (pinfunction "C_C") (pintype "passive"))
      (node (ref "R41") (pin "2") (pinfunction "2_2") (pintype "passive"))
    )
    (net (code "103") (name "Net-(MCU-P85{slash}NMI)") (class "Default")
      (node (ref "MCU") (pin "15") (pinfunction "P85/NMI_15") (pintype "input"))
      (node (ref "R44") (pin "2") (pinfunction "2_2") (pintype "passive"))
    )
    (net (code "104") (name "Net-(MCU-P86{slash}XCOUT)") (class "Default")
      (node (ref "MCU") (pin "9") (pinfunction "P86/XCOUT_9") (pintype "bidirectional"))
      (node (ref "Q1") (pin "4") (pinfunction "2_4") (pintype "passive"))
    )
    (net (code "105") (name "Net-(MCU-P87{slash}XCIN)") (class "Default")
      (node (ref "MCU") (pin "8") (pinfunction "P87/XCIN_8") (pintype "bidirectional"))
      (node (ref "Q1") (pin "1") (pinfunction "1_1") (pintype "passive"))
    )
    (net (code "106") (name "Net-(MCU-XIN)") (class "Default")
      (node (ref "MCU") (pin "13") (pinfunction "XIN_13") (pintype "input"))
      (node (ref "Y2") (pin "3") (pinfunction "3_3") (pintype "passive"))
    )
    (net (code "107") (name "Net-(MCU-XOUT)") (class "Default")
      (node (ref "MCU") (pin "11") (pinfunction "XOUT_11") (pintype "output"))
      (node (ref "Y2") (pin "1") (pinfunction "1_1") (pintype "passive"))
    )
    (net (code "108") (name "Net-(PAD25-P)") (class "Default")
      (node (ref "DRAIN") (pin "TP") (pinfunction "TP_TP") (pintype "input"))
      (node (ref "PAD25") (pin "1") (pinfunction "P_1") (pintype "passive"))
      (node (ref "R21") (pin "2") (pinfunction "2_2") (pintype "passive"))
      (node (ref "R24") (pin "2") (pinfunction "2_2") (pintype "passive"))
      (node (ref "U$1") (pin "3") (pinfunction "3_3") (pintype "bidirectional"))
      (node (ref "U$1") (pin "4") (pinfunction "4_4") (pintype "bidirectional"))
      (node (ref "U$1") (pin "5") (pinfunction "5_5") (pintype "bidirectional"))
      (node (ref "U$1") (pin "6") (pinfunction "6_6") (pintype "bidirectional"))
      (node (ref "U$102") (pin "5") (pinfunction "D_5") (pintype "passive"))
      (node (ref "U$102") (pin "6") (pinfunction "D_6") (pintype "passive"))
      (node (ref "U$102") (pin "7") (pinfunction "D_7") (pintype "passive"))
      (node (ref "U$102") (pin "8") (pinfunction "D_8") (pintype "passive"))
    )
    (net (code "109") (name "Net-(PANDA1-PadC)") (class "Default")
      (node (ref "PANDA1") (pin "C") (pinfunction "C_C") (pintype "passive"))
      (node (ref "R43") (pin "2") (pinfunction "2_2") (pintype "passive"))
    )
    (net (code "110") (name "Net-(PANDA2-PadC)") (class "Default")
      (node (ref "PANDA2") (pin "C") (pinfunction "C_C") (pintype "passive"))
      (node (ref "R38") (pin "2") (pinfunction "2_2") (pintype "passive"))
    )
    (net (code "111") (name "Net-(POWER-PadC)") (class "Default")
      (node (ref "POWER") (pin "C") (pinfunction "C_C") (pintype "passive"))
      (node (ref "R42") (pin "1") (pinfunction "1_1") (pintype "passive"))
    )
    (net (code "112") (name "Net-(Q2-G)") (class "Default")
      (node (ref "Q2") (pin "1") (pinfunction "G_1") (pintype "passive"))
      (node (ref "Q3") (pin "3") (pinfunction "C_3") (pintype "passive"))
      (node (ref "R16") (pin "1") (pinfunction "1_1") (pintype "passive"))
    )
    (net (code "113") (name "Net-(R10-Pad2)") (class "Default")
      (node (ref "R10") (pin "2") (pinfunction "2_2") (pintype "passive"))
      (node (ref "RIGHTPWM") (pin "C") (pinfunction "C_C") (pintype "passive"))
    )
    (net (code "114") (name "Net-(R47-Pad1)") (class "Default")
      (node (ref "R47") (pin "1") (pinfunction "1_1") (pintype "passive"))
      (node (ref "SG2") (pin "1") (pinfunction "1_1") (pintype "passive"))
    )
    (net (code "115") (name "Net-(U$3-BOOT)") (class "Default")
      (node (ref "C15") (pin "2") (pinfunction "2_2") (pintype "passive"))
      (node (ref "U$3") (pin "1") (pinfunction "BOOT_1") (pintype "bidirectional"))
    )
    (net (code "116") (name "Net-(U$3-COMP)") (class "Default")
      (node (ref "C10") (pin "1") (pinfunction "1_1") (pintype "passive"))
      (node (ref "C11") (pin "1") (pinfunction "1_1") (pintype "passive"))
      (node (ref "COMP") (pin "TP") (pinfunction "TP_TP") (pintype "input"))
      (node (ref "U$3") (pin "6") (pinfunction "COMP_6") (pintype "bidirectional"))
    )
    (net (code "117") (name "Net-(U$3-SS)") (class "Default")
      (node (ref "C27") (pin "2") (pinfunction "2_2") (pintype "passive"))
      (node (ref "U$3") (pin "4") (pinfunction "SS_4") (pintype "bidirectional"))
    )
    (net (code "118") (name "Net-(U$3-VSENSE)") (class "Default")
      (node (ref "R26") (pin "1") (pinfunction "1_1") (pintype "passive"))
      (node (ref "R37") (pin "2") (pinfunction "2_2") (pintype "passive"))
      (node (ref "U$3") (pin "5") (pinfunction "VSENSE_5") (pintype "bidirectional"))
      (node (ref "VSENSE") (pin "TP") (pinfunction "TP_TP") (pintype "input"))
    )
    (net (code "119") (name "Net-(U2-PLL)") (class "Default")
      (node (ref "C47") (pin "1") (pinfunction "1_1") (pintype "passive"))
      (node (ref "C48") (pin "1") (pinfunction "1_1") (pintype "passive"))
      (node (ref "U2") (pin "14") (pinfunction "PLL_14") (pintype "bidirectional"))
    )
    (net (code "120") (name "OLED_ENA") (class "Default")
      (node (ref "EN_OLED") (pin "TP") (pinfunction "TP_TP") (pintype "input"))
      (node (ref "MCU") (pin "48") (pinfunction "P44/CS3/A20/RTS6_48") (pintype "bidirectional"))
      (node (ref "Q3") (pin "1") (pinfunction "B_1") (pintype "passive"))
    )
    (net (code "121") (name "RESET") (class "Default")
      (node (ref "IC3") (pin "2") (pinfunction "~{RES}_2") (pintype "output"))
      (node (ref "JP1") (pin "13") (pinfunction "13_13") (pintype "passive"))
      (node (ref "MCU") (pin "10") (pinfunction "RESET_10") (pintype "input"))
      (node (ref "R46") (pin "2") (pinfunction "2_2") (pintype "passive"))
      (node (ref "RESET") (pin "TP") (pinfunction "TP_TP") (pintype "input"))
      (node (ref "X1") (pin "10") (pinfunction "S_10") (pintype "passive"))
    )
    (net (code "122") (name "RES_LCD") (class "Default")
      (node (ref "J1") (pin "20") (pinfunction "MS_20") (pintype "passive"))
      (node (ref "MCU") (pin "50") (pinfunction "P42/A18/RX3_50") (pintype "bidirectional"))
      (node (ref "RES_OLED") (pin "TP") (pinfunction "TP_TP") (pintype "input"))
    )
    (net (code "123") (name "RIGHT_DIAGA") (class "Default")
      (node (ref "MCU") (pin "66") (pinfunction "P24/AN24/A4/[A4/D4]_66") (pintype "bidirectional"))
      (node (ref "R5") (pin "1") (pinfunction "1_1") (pintype "passive"))
      (node (ref "R_ENA") (pin "TP") (pinfunction "TP_TP") (pintype "input"))
    )
    (net (code "124") (name "RIGHT_DIAGB") (class "Default")
      (node (ref "MCU") (pin "65") (pinfunction "P25/AN25/A5/[A5/D5]_65") (pintype "bidirectional"))
      (node (ref "R6") (pin "1") (pinfunction "1_1") (pintype "passive"))
      (node (ref "R_ENB") (pin "TP") (pinfunction "TP_TP") (pintype "input"))
    )
    (net (code "125") (name "RIGHT_INA") (class "Default")
      (node (ref "MCU") (pin "70") (pinfunction "P20/AN20/A0/[A0/D0]/BC0_70") (pintype "bidirectional"))
      (node (ref "R3") (pin "1") (pinfunction "1_1") (pintype "passive"))
      (node (ref "R_INA") (pin "TP") (pinfunction "TP_TP") (pintype "input"))
    )
    (net (code "126") (name "RIGHT_INB") (class "Default")
      (node (ref "MCU") (pin "69") (pinfunction "P21/AN21/A1/[A1/D1]_69") (pintype "bidirectional"))
      (node (ref "R4") (pin "1") (pinfunction "1_1") (pintype "passive"))
      (node (ref "R_INB") (pin "TP") (pinfunction "TP_TP") (pintype "input"))
    )
    (net (code "127") (name "RIGHT_PWM") (class "Default")
      (node (ref "MCU") (pin "56") (pinfunction "P34/A12/[A12/D12]_56") (pintype "bidirectional"))
      (node (ref "R7") (pin "1") (pinfunction "1_1") (pintype "passive"))
      (node (ref "RIGHTPWM") (pin "A") (pinfunction "A_A") (pintype "passive"))
      (node (ref "R_PWM") (pin "TP") (pinfunction "TP_TP") (pintype "input"))
    )
    (net (code "128") (name "RX0") (class "Default")
      (node (ref "IC4") (pin "25") (pinfunction "TXD_25") (pintype "output"))
      (node (ref "MCU") (pin "34") (pinfunction "P62/RXDO/SCL0/STX0_34") (pintype "bidirectional"))
      (node (ref "RX0") (pin "TP") (pinfunction "TP_TP") (pintype "input"))
    )
    (net (code "129") (name "RX2") (class "Default")
      (node (ref "MCU") (pin "27") (pinfunction "P71/RXD2/SCL2/TA0IN/TB5IN/SX2_27") (pintype "bidirectional"))
      (node (ref "R62") (pin "1") (pinfunction "1_1") (pintype "passive"))
      (node (ref "RX2") (pin "TP") (pinfunction "TP_TP") (pintype "input"))
      (node (ref "U$5") (pin "12") (pinfunction "SDO_12") (pintype "bidirectional"))
    )
    (net (code "130") (name "RX4") (class "Default")
      (node (ref "J4") (pin "2") (pinfunction "MS_2") (pintype "passive"))
      (node (ref "MCU") (pin "98") (pinfunction "P97/ADTRG/RX4/SCL4_98") (pintype "bidirectional"))
      (node (ref "Q4") (pin "2") (pinfunction "S_2") (pintype "passive"))
      (node (ref "R48") (pin "1") (pinfunction "1_1") (pintype "passive"))
      (node (ref "RX4") (pin "TP") (pinfunction "TP_TP") (pintype "input"))
    )
    (net (code "131") (name "RX5") (class "Default")
      (node (ref "MCU") (pin "20") (pinfunction "P80/TA4OUT/U/RX5_20") (pintype "bidirectional"))
      (node (ref "PANDA") (pin "1") (pinfunction "1_1") (pintype "passive"))
    )
    (net (code "132") (name "RX6") (class "Default")
      (node (ref "MCU") (pin "46") (pinfunction "P46/CS1/A22/RX6_46") (pintype "bidirectional"))
      (node (ref "RX6") (pin "TP") (pinfunction "TP_TP") (pintype "input"))
      (node (ref "U2") (pin "4") (pinfunction "SDO_4") (pintype "bidirectional"))
    )
    (net (code "133") (name "RX7") (class "Default")
      (node (ref "J5") (pin "2") (pinfunction "MS_2") (pintype "passive"))
      (node (ref "MCU") (pin "38") (pinfunction "P56/ALE/RX7_38") (pintype "bidirectional"))
      (node (ref "Q5") (pin "2") (pinfunction "S_2") (pintype "passive"))
      (node (ref "R53") (pin "1") (pinfunction "1_1") (pintype "passive"))
      (node (ref "RX7") (pin "TP") (pinfunction "TP_TP") (pintype "input"))
    )
    (net (code "134") (name "SDMMC2_CD") (class "Default")
      (node (ref "CD") (pin "TP") (pinfunction "TP_TP") (pintype "input"))
      (node (ref "J6") (pin "25") (pinfunction "25_25") (pintype "passive"))
      (node (ref "R59") (pin "1") (pinfunction "1_1") (pintype "passive"))
      (node (ref "X7") (pin "SW1") (pinfunction "SW1_SW1") (pintype "passive"))
    )
    (net (code "135") (name "SDMMC2_CLK") (class "Default")
      (node (ref "CLK") (pin "TP") (pinfunction "TP_TP") (pintype "input"))
      (node (ref "J3") (pin "21") (pinfunction "21_21") (pintype "passive"))
      (node (ref "U1") (pin "7") (pinfunction "A6_7") (pintype "bidirectional"))
    )
    (net (code "136") (name "SDMMC2_CMD") (class "Default")
      (node (ref "CMD") (pin "TP") (pinfunction "TP_TP") (pintype "input"))
      (node (ref "J3") (pin "19") (pinfunction "19_19") (pintype "passive"))
      (node (ref "U1") (pin "6") (pinfunction "A5_6") (pintype "bidirectional"))
    )
    (net (code "137") (name "SDMMC2_DAT0") (class "Default")
      (node (ref "DAT0") (pin "TP") (pinfunction "TP_TP") (pintype "input"))
      (node (ref "J3") (pin "17") (pinfunction "17_17") (pintype "passive"))
      (node (ref "U1") (pin "5") (pinfunction "A4_5") (pintype "bidirectional"))
    )
    (net (code "138") (name "SDMMC2_DAT1") (class "Default")
      (node (ref "DAT1") (pin "TP") (pinfunction "TP_TP") (pintype "input"))
      (node (ref "J3") (pin "15") (pinfunction "15_15") (pintype "passive"))
      (node (ref "U1") (pin "4") (pinfunction "A3_4") (pintype "bidirectional"))
    )
    (net (code "139") (name "SDMMC2_DAT2") (class "Default")
      (node (ref "DAT2") (pin "TP") (pinfunction "TP_TP") (pintype "input"))
      (node (ref "J3") (pin "13") (pinfunction "13_13") (pintype "passive"))
      (node (ref "U1") (pin "3") (pinfunction "A2_3") (pintype "bidirectional"))
    )
    (net (code "140") (name "SDMMC2_DAT3") (class "Default")
      (node (ref "DAT3") (pin "TP") (pinfunction "TP_TP") (pintype "input"))
      (node (ref "J3") (pin "11") (pinfunction "11_11") (pintype "passive"))
      (node (ref "U1") (pin "1") (pinfunction "A1_1") (pintype "bidirectional"))
    )
    (net (code "141") (name "SDMMC2_WP") (class "Default")
      (node (ref "J6") (pin "27") (pinfunction "27_27") (pintype "passive"))
      (node (ref "R60") (pin "1") (pinfunction "1_1") (pintype "passive"))
      (node (ref "WP") (pin "TP") (pinfunction "TP_TP") (pintype "input"))
      (node (ref "X7") (pin "SW2") (pinfunction "SW2_SW2") (pintype "passive"))
    )
    (net (code "142") (name "TX0") (class "Default")
      (node (ref "IC4") (pin "24") (pinfunction "RXD_24") (pintype "input"))
      (node (ref "MCU") (pin "33") (pinfunction "P63/TXDO/SDA0/SRX0_33") (pintype "bidirectional"))
      (node (ref "TX0") (pin "TP") (pinfunction "TP_TP") (pintype "input"))
    )
    (net (code "143") (name "TX2") (class "Default")
      (node (ref "MCU") (pin "28") (pinfunction "P70/TXD2/SDA2/TA0OUT/SRX2_28") (pintype "bidirectional"))
      (node (ref "R61") (pin "1") (pinfunction "1_1") (pintype "passive"))
      (node (ref "TX2") (pin "TP") (pinfunction "TP_TP") (pintype "input"))
      (node (ref "U$5") (pin "13") (pinfunction "SDA/SDI/SDO_13") (pintype "bidirectional"))
    )
    (net (code "144") (name "TX4") (class "Default")
      (node (ref "MCU") (pin "99") (pinfunction "P96/ANEX1/TX4/SDA4_99") (pintype "bidirectional"))
      (node (ref "Q4") (pin "1") (pinfunction "G_1") (pintype "passive"))
      (node (ref "TX4") (pin "TP") (pinfunction "TP_TP") (pintype "input"))
    )
    (net (code "145") (name "TX5") (class "Default")
      (node (ref "MCU") (pin "22") (pinfunction "P76/TA3OUT/TX5_22") (pintype "bidirectional"))
      (node (ref "PANDA") (pin "3") (pinfunction "3_3") (pintype "passive"))
    )
    (net (code "146") (name "TX6") (class "Default")
      (node (ref "MCU") (pin "45") (pinfunction "P47/CS0/A23/TX6_45") (pintype "bidirectional"))
      (node (ref "TX6") (pin "TP") (pinfunction "TP_TP") (pintype "input"))
      (node (ref "U2") (pin "3") (pinfunction "SDA/SDI_3") (pintype "bidirectional"))
    )
    (net (code "147") (name "TX7") (class "Default")
      (node (ref "MCU") (pin "40") (pinfunction "P54/HLDA/TX7_40") (pintype "bidirectional"))
      (node (ref "Q5") (pin "1") (pinfunction "G_1") (pintype "passive"))
      (node (ref "TX7") (pin "TP") (pinfunction "TP_TP") (pintype "input"))
    )
    (net (code "148") (name "USBH3_DM") (class "Default")
      (node (ref "J6") (pin "3") (pinfunction "3_3") (pintype "passive"))
      (node (ref "X4") (pin "D-") (pinfunction "D-_D-") (pintype "bidirectional"))
    )
    (net (code "149") (name "USBH3_DP") (class "Default")
      (node (ref "J6") (pin "5") (pinfunction "5_5") (pintype "passive"))
      (node (ref "X4") (pin "D+") (pinfunction "D+_D+") (pintype "bidirectional"))
    )
    (net (code "150") (name "USBH4_DM") (class "Default")
      (node (ref "IC4") (pin "4") (pinfunction "D-_4") (pintype "bidirectional"))
      (node (ref "J6") (pin "4") (pinfunction "4_4") (pintype "passive"))
    )
    (net (code "151") (name "USBH4_DP") (class "Default")
      (node (ref "IC4") (pin "3") (pinfunction "D+_3") (pintype "bidirectional"))
      (node (ref "J6") (pin "6") (pinfunction "6_6") (pintype "passive"))
    )
    (net (code "152") (name "VBAT") (class "Default")
      (node (ref "10UF/16V") (pin "P$1") (pinfunction "+_P$1") (pintype "passive"))
      (node (ref "C1") (pin "+") (pinfunction "+_+") (pintype "passive"))
      (node (ref "C12") (pin "+") (pinfunction "+_+") (pintype "passive"))
      (node (ref "C13") (pin "+") (pinfunction "+_+") (pintype "passive"))
      (node (ref "C14") (pin "+") (pinfunction "+_+") (pintype "passive"))
      (node (ref "C18") (pin "1") (pinfunction "1_1") (pintype "passive"))
      (node (ref "C19") (pin "1") (pinfunction "1_1") (pintype "passive"))
      (node (ref "C2") (pin "+") (pinfunction "+_+") (pintype "passive"))
      (node (ref "C31") (pin "1") (pinfunction "1_1") (pintype "passive"))
      (node (ref "C41") (pin "1") (pinfunction "1_1") (pintype "passive"))
      (node (ref "C45") (pin "1") (pinfunction "1_1") (pintype "passive"))
      (node (ref "C46") (pin "1") (pinfunction "1_1") (pintype "passive"))
      (node (ref "COILGUN") (pin "4") (pinfunction "4_4") (pintype "passive"))
      (node (ref "IC1") (pin "5") (pinfunction "IN_5") (pintype "input"))
      (node (ref "IC1") (pin "6") (pinfunction "IN_6") (pintype "input"))
      (node (ref "IC2") (pin "13") (pinfunction "VCC_13") (pintype "power_in"))
      (node (ref "IC2") (pin "23") (pinfunction "VCC_23") (pintype "power_in"))
      (node (ref "IC2") (pin "3") (pinfunction "VCC_3") (pintype "power_in"))
      (node (ref "IC2") (pin "VCC") (pinfunction "VCC_VCC") (pintype "power_in"))
      (node (ref "IC2") (pin "VCC@1") (pinfunction "VCC_VCC@1") (pintype "power_in"))
      (node (ref "IC6") (pin "13") (pinfunction "VCC_13") (pintype "power_in"))
      (node (ref "IC6") (pin "23") (pinfunction "VCC_23") (pintype "power_in"))
      (node (ref "IC6") (pin "3") (pinfunction "VCC_3") (pintype "power_in"))
      (node (ref "IC6") (pin "VCC") (pinfunction "VCC_VCC") (pintype "power_in"))
      (node (ref "IC6") (pin "VCC@1") (pinfunction "VCC_VCC@1") (pintype "power_in"))
      (node (ref "IC8") (pin "1") (pinfunction "VIN_1") (pintype "input"))
      (node (ref "LT3750") (pin "1") (pinfunction "VT_1") (pintype "bidirectional"))
      (node (ref "LT3750") (pin "4") (pinfunction "VCC_4") (pintype "bidirectional"))
      (node (ref "PAD26") (pin "1") (pinfunction "P_1") (pintype "passive"))
      (node (ref "PAD27") (pin "1") (pinfunction "P_1") (pintype "passive"))
      (node (ref "PAD28") (pin "1") (pinfunction "P_1") (pintype "passive"))
      (node (ref "PAD29") (pin "1") (pinfunction "P_1") (pintype "passive"))
      (node (ref "PAD30") (pin "1") (pinfunction "P_1") (pintype "passive"))
      (node (ref "PAD31") (pin "1") (pinfunction "P_1") (pintype "passive"))
      (node (ref "PAD32") (pin "1") (pinfunction "P_1") (pintype "passive"))
      (node (ref "PAD33") (pin "1") (pinfunction "P_1") (pintype "passive"))
      (node (ref "PAD34") (pin "1") (pinfunction "P_1") (pintype "passive"))
      (node (ref "PAD35") (pin "1") (pinfunction "P_1") (pintype "passive"))
      (node (ref "PAD36") (pin "1") (pinfunction "P_1") (pintype "passive"))
      (node (ref "PAD37") (pin "1") (pinfunction "P_1") (pintype "passive"))
      (node (ref "PAD38") (pin "1") (pinfunction "P_1") (pintype "passive"))
      (node (ref "PAD39") (pin "1") (pinfunction "P_1") (pintype "passive"))
      (node (ref "PAD40") (pin "1") (pinfunction "P_1") (pintype "passive"))
      (node (ref "PAD41") (pin "1") (pinfunction "P_1") (pintype "passive"))
      (node (ref "PAD42") (pin "1") (pinfunction "P_1") (pintype "passive"))
      (node (ref "PAD43") (pin "1") (pinfunction "P_1") (pintype "passive"))
      (node (ref "PAD44") (pin "1") (pinfunction "P_1") (pintype "passive"))
      (node (ref "PAD45") (pin "1") (pinfunction "P_1") (pintype "passive"))
      (node (ref "PAD46") (pin "1") (pinfunction "P_1") (pintype "passive"))
      (node (ref "PAD47") (pin "1") (pinfunction "P_1") (pintype "passive"))
      (node (ref "PAD48") (pin "1") (pinfunction "P_1") (pintype "passive"))
      (node (ref "PAD49") (pin "1") (pinfunction "P_1") (pintype "passive"))
      (node (ref "PAD50") (pin "1") (pinfunction "P_1") (pintype "passive"))
      (node (ref "PAD51") (pin "1") (pinfunction "P_1") (pintype "passive"))
      (node (ref "PAD52") (pin "1") (pinfunction "P_1") (pintype "passive"))
      (node (ref "PAD53") (pin "1") (pinfunction "P_1") (pintype "passive"))
      (node (ref "PAD54") (pin "1") (pinfunction "P_1") (pintype "passive"))
      (node (ref "PAD55") (pin "1") (pinfunction "P_1") (pintype "passive"))
      (node (ref "Q2") (pin "2") (pinfunction "S_2") (pintype "passive"))
      (node (ref "R16") (pin "2") (pinfunction "2_2") (pintype "passive"))
      (node (ref "R50") (pin "1") (pinfunction "1_1") (pintype "passive"))
      (node (ref "U$1") (pin "10") (pinfunction "10_10") (pintype "bidirectional"))
      (node (ref "U$1") (pin "7") (pinfunction "7_7") (pintype "bidirectional"))
      (node (ref "U$1") (pin "8") (pinfunction "8_8") (pintype "bidirectional"))
      (node (ref "U$1") (pin "9") (pinfunction "9_9") (pintype "bidirectional"))
      (node (ref "U$3") (pin "2") (pinfunction "VIN_2") (pintype "bidirectional"))
      (node (ref "VBAT") (pin "1") (pinfunction "P_1") (pintype "passive"))
    )
    (net (code "153") (name "VBUS_3") (class "Default")
      (node (ref "J6") (pin "1") (pinfunction "1_1") (pintype "passive"))
      (node (ref "X4") (pin "VBUS") (pinfunction "VBUS_VBUS") (pintype "bidirectional"))
    )
    (net (code "154") (name "VBUS_4") (class "Default")
      (node (ref "IC4") (pin "7") (pinfunction "REGIN_7") (pintype "passive"))
      (node (ref "IC4") (pin "8") (pinfunction "VBUS_8") (pintype "input"))
      (node (ref "J6") (pin "2") (pinfunction "2_2") (pintype "passive"))
    )
    (net (code "155") (name "VCORE") (class "Default")
      (node (ref "C60") (pin "1") (pinfunction "1_1") (pintype "passive"))
      (node (ref "C63") (pin "1") (pinfunction "1_1") (pintype "passive"))
      (node (ref "J1") (pin "25") (pinfunction "MS_25") (pintype "passive"))
      (node (ref "VCORE") (pin "TP") (pinfunction "TP_TP") (pintype "input"))
    )
    (net (code "156") (name "VDC0") (class "Default")
      (node (ref "C57") (pin "2") (pinfunction "2_2") (pintype "passive"))
      (node (ref "MCU") (pin "3") (pinfunction "VDC0_3") (pintype "power_in"))
    )
    (net (code "157") (name "VDC1") (class "Default")
      (node (ref "C57") (pin "1") (pinfunction "1_1") (pintype "passive"))
      (node (ref "MCU") (pin "5") (pinfunction "VDC1_5") (pintype "power_in"))
    )
    (net (code "158") (name "VIO_1V8") (class "Default")
      (node (ref "J3") (pin "1") (pinfunction "1_1") (pintype "passive"))
      (node (ref "R59") (pin "2") (pinfunction "2_2") (pintype "passive"))
      (node (ref "R60") (pin "2") (pinfunction "2_2") (pintype "passive"))
      (node (ref "U1") (pin "10") (pinfunction "OE_10") (pintype "bidirectional"))
      (node (ref "U1") (pin "2") (pinfunction "VCCA_2") (pintype "bidirectional"))
    )
    (net (code "159") (name "WR") (class "Default")
      (node (ref "JP1") (pin "7") (pinfunction "7_7") (pintype "passive"))
      (node (ref "MCU") (pin "44") (pinfunction "P50/WR0/WR_44") (pintype "bidirectional"))
      (node (ref "WR") (pin "TP") (pinfunction "TP_TP") (pintype "input"))
      (node (ref "X1") (pin "7") (pinfunction "S_7") (pintype "passive"))
    )
    (net (code "160") (name "unconnected-(D2-C1A2-Pad3)") (class "Default")
      (node (ref "D2") (pin "3") (pinfunction "C1A2_3") (pintype "passive"))
    )
    (net (code "161") (name "unconnected-(IC1-~{RESET}-Pad2)") (class "Default")
      (node (ref "IC1") (pin "2") (pinfunction "~{RESET}_2") (pintype "input"))
    )
    (net (code "162") (name "unconnected-(IC4-CTS-Pad22)") (class "Default")
      (node (ref "IC4") (pin "22") (pinfunction "CTS_22") (pintype "input"))
    )
    (net (code "163") (name "unconnected-(IC4-DCD-Pad28)") (class "Default")
      (node (ref "IC4") (pin "28") (pinfunction "DCD_28") (pintype "input"))
    )
    (net (code "164") (name "unconnected-(IC4-GPIO_0-Pad19)") (class "Default")
      (node (ref "IC4") (pin "19") (pinfunction "GPIO_0_19") (pintype "bidirectional"))
    )
    (net (code "165") (name "unconnected-(IC4-GPIO_1-Pad18)") (class "Default")
      (node (ref "IC4") (pin "18") (pinfunction "GPIO_1_18") (pintype "bidirectional"))
    )
    (net (code "166") (name "unconnected-(IC4-GPIO_2-Pad17)") (class "Default")
      (node (ref "IC4") (pin "17") (pinfunction "GPIO_2_17") (pintype "bidirectional"))
    )
    (net (code "167") (name "unconnected-(IC4-GPIO_3-Pad16)") (class "Default")
      (node (ref "IC4") (pin "16") (pinfunction "GPIO_3_16") (pintype "bidirectional"))
    )
    (net (code "168") (name "unconnected-(IC4-RI-Pad1)") (class "Default")
      (node (ref "IC4") (pin "1") (pinfunction "RI_1") (pintype "input"))
    )
    (net (code "169") (name "unconnected-(IC4-RTS-Pad23)") (class "Default")
      (node (ref "IC4") (pin "23") (pinfunction "RTS_23") (pintype "output"))
    )
    (net (code "170") (name "unconnected-(IC4-SUSPEND-Pad12)") (class "Default")
      (node (ref "IC4") (pin "12") (pinfunction "SUSPEND_12") (pintype "output"))
    )
    (net (code "171") (name "unconnected-(IC4-~{RST}-Pad9)") (class "Default")
      (node (ref "IC4") (pin "9") (pinfunction "~{RST}_9") (pintype "bidirectional"))
    )
    (net (code "172") (name "unconnected-(IC4-~{SUSPEND}-Pad11)") (class "Default")
      (node (ref "IC4") (pin "11") (pinfunction "~{SUSPEND}_11") (pintype "output"))
    )
    (net (code "173") (name "unconnected-(J1C-MS-Pad11)") (class "Default")
      (node (ref "J1") (pin "11") (pinfunction "MS_11") (pintype "passive"))
    )
    (net (code "174") (name "unconnected-(J1N-MS-Pad21)") (class "Default")
      (node (ref "J1") (pin "21") (pinfunction "MS_21") (pintype "passive"))
    )
    (net (code "175") (name "unconnected-(J1P-MS-Pad23)") (class "Default")
      (node (ref "J1") (pin "23") (pinfunction "MS_23") (pintype "passive"))
    )
    (net (code "176") (name "unconnected-(J3-Pad2)") (class "Default")
      (node (ref "J3") (pin "2") (pinfunction "2_2") (pintype "passive"))
    )
    (net (code "177") (name "unconnected-(J3-Pad3)") (class "Default")
      (node (ref "J3") (pin "3") (pinfunction "3_3") (pintype "passive"))
    )
    (net (code "178") (name "unconnected-(J3-Pad4)") (class "Default")
      (node (ref "J3") (pin "4") (pinfunction "4_4") (pintype "passive"))
    )
    (net (code "179") (name "unconnected-(J3-Pad5)") (class "Default")
      (node (ref "J3") (pin "5") (pinfunction "5_5") (pintype "passive"))
    )
    (net (code "180") (name "unconnected-(J3-Pad6)") (class "Default")
      (node (ref "J3") (pin "6") (pinfunction "6_6") (pintype "passive"))
    )
    (net (code "181") (name "unconnected-(J3-Pad7)") (class "Default")
      (node (ref "J3") (pin "7") (pinfunction "7_7") (pintype "passive"))
    )
    (net (code "182") (name "unconnected-(J3-Pad8)") (class "Default")
      (node (ref "J3") (pin "8") (pinfunction "8_8") (pintype "passive"))
    )
    (net (code "183") (name "unconnected-(J3-Pad9)") (class "Default")
      (node (ref "J3") (pin "9") (pinfunction "9_9") (pintype "passive"))
    )
    (net (code "184") (name "unconnected-(J3-Pad10)") (class "Default")
      (node (ref "J3") (pin "10") (pinfunction "10_10") (pintype "passive"))
    )
    (net (code "185") (name "unconnected-(J3-Pad12)") (class "Default")
      (node (ref "J3") (pin "12") (pinfunction "12_12") (pintype "passive"))
    )
    (net (code "186") (name "unconnected-(J3-Pad14)") (class "Default")
      (node (ref "J3") (pin "14") (pinfunction "14_14") (pintype "passive"))
    )
    (net (code "187") (name "unconnected-(J3-Pad16)") (class "Default")
      (node (ref "J3") (pin "16") (pinfunction "16_16") (pintype "passive"))
    )
    (net (code "188") (name "unconnected-(J3-Pad18)") (class "Default")
      (node (ref "J3") (pin "18") (pinfunction "18_18") (pintype "passive"))
    )
    (net (code "189") (name "unconnected-(J3-Pad20)") (class "Default")
      (node (ref "J3") (pin "20") (pinfunction "20_20") (pintype "passive"))
    )
    (net (code "190") (name "unconnected-(J3-Pad22)") (class "Default")
      (node (ref "J3") (pin "22") (pinfunction "22_22") (pintype "passive"))
    )
    (net (code "191") (name "unconnected-(J3-Pad23)") (class "Default")
      (node (ref "J3") (pin "23") (pinfunction "23_23") (pintype "passive"))
    )
    (net (code "192") (name "unconnected-(J3-Pad24)") (class "Default")
      (node (ref "J3") (pin "24") (pinfunction "24_24") (pintype "passive"))
    )
    (net (code "193") (name "unconnected-(J3-Pad25)") (class "Default")
      (node (ref "J3") (pin "25") (pinfunction "25_25") (pintype "passive"))
    )
    (net (code "194") (name "unconnected-(J3-Pad26)") (class "Default")
      (node (ref "J3") (pin "26") (pinfunction "26_26") (pintype "passive"))
    )
    (net (code "195") (name "unconnected-(J6-Pad9)") (class "Default")
      (node (ref "J6") (pin "9") (pinfunction "9_9") (pintype "passive"))
    )
    (net (code "196") (name "unconnected-(J6-Pad10)") (class "Default")
      (node (ref "J6") (pin "10") (pinfunction "10_10") (pintype "passive"))
    )
    (net (code "197") (name "unconnected-(J6-Pad11)") (class "Default")
      (node (ref "J6") (pin "11") (pinfunction "11_11") (pintype "passive"))
    )
    (net (code "198") (name "unconnected-(J6-Pad12)") (class "Default")
      (node (ref "J6") (pin "12") (pinfunction "12_12") (pintype "passive"))
    )
    (net (code "199") (name "unconnected-(J6-Pad13)") (class "Default")
      (node (ref "J6") (pin "13") (pinfunction "13_13") (pintype "passive"))
    )
    (net (code "200") (name "unconnected-(J6-Pad14)") (class "Default")
      (node (ref "J6") (pin "14") (pinfunction "14_14") (pintype "passive"))
    )
    (net (code "201") (name "unconnected-(J6-Pad15)") (class "Default")
      (node (ref "J6") (pin "15") (pinfunction "15_15") (pintype "passive"))
    )
    (net (code "202") (name "unconnected-(J6-Pad16)") (class "Default")
      (node (ref "J6") (pin "16") (pinfunction "16_16") (pintype "passive"))
    )
    (net (code "203") (name "unconnected-(J6-Pad18)") (class "Default")
      (node (ref "J6") (pin "18") (pinfunction "18_18") (pintype "passive"))
    )
    (net (code "204") (name "unconnected-(J6-Pad20)") (class "Default")
      (node (ref "J6") (pin "20") (pinfunction "20_20") (pintype "passive"))
    )
    (net (code "205") (name "unconnected-(J6-Pad21)") (class "Default")
      (node (ref "J6") (pin "21") (pinfunction "21_21") (pintype "passive"))
    )
    (net (code "206") (name "unconnected-(J6-Pad22)") (class "Default")
      (node (ref "J6") (pin "22") (pinfunction "22_22") (pintype "passive"))
    )
    (net (code "207") (name "unconnected-(J6-Pad23)") (class "Default")
      (node (ref "J6") (pin "23") (pinfunction "23_23") (pintype "passive"))
    )
    (net (code "208") (name "unconnected-(J6-Pad24)") (class "Default")
      (node (ref "J6") (pin "24") (pinfunction "24_24") (pintype "passive"))
    )
    (net (code "209") (name "unconnected-(J6-Pad26)") (class "Default")
      (node (ref "J6") (pin "26") (pinfunction "26_26") (pintype "passive"))
    )
    (net (code "210") (name "unconnected-(J6-Pad28)") (class "Default")
      (node (ref "J6") (pin "28") (pinfunction "28_28") (pintype "passive"))
    )
    (net (code "211") (name "unconnected-(MCU-P00{slash}D0{slash}AN10-Pad86)") (class "Default")
      (node (ref "MCU") (pin "86") (pinfunction "P00/D0/AN10_86") (pintype "bidirectional"))
    )
    (net (code "212") (name "unconnected-(MCU-P01{slash}D1{slash}AN11-Pad85)") (class "Default")
      (node (ref "MCU") (pin "85") (pinfunction "P01/D1/AN11_85") (pintype "bidirectional"))
    )
    (net (code "213") (name "unconnected-(MCU-P02{slash}D2{slash}AN12-Pad84)") (class "Default")
      (node (ref "MCU") (pin "84") (pinfunction "P02/D2/AN12_84") (pintype "bidirectional"))
    )
    (net (code "214") (name "unconnected-(MCU-P03{slash}D3{slash}AN13-Pad83)") (class "Default")
      (node (ref "MCU") (pin "83") (pinfunction "P03/D3/AN13_83") (pintype "bidirectional"))
    )
    (net (code "215") (name "unconnected-(MCU-P04{slash}D4{slash}AN14-Pad82)") (class "Default")
      (node (ref "MCU") (pin "82") (pinfunction "P04/D4/AN14_82") (pintype "bidirectional"))
    )
    (net (code "216") (name "unconnected-(MCU-P05{slash}D5{slash}AN15-Pad81)") (class "Default")
      (node (ref "MCU") (pin "81") (pinfunction "P05/D5/AN15_81") (pintype "bidirectional"))
    )
    (net (code "217") (name "unconnected-(MCU-P06{slash}D6{slash}AN16-Pad80)") (class "Default")
      (node (ref "MCU") (pin "80") (pinfunction "P06/D6/AN16_80") (pintype "bidirectional"))
    )
    (net (code "218") (name "unconnected-(MCU-P07{slash}D7{slash}AN17-Pad79)") (class "Default")
      (node (ref "MCU") (pin "79") (pinfunction "P07/D7/AN17_79") (pintype "bidirectional"))
    )
    (net (code "219") (name "unconnected-(MCU-P10{slash}D8{slash}IIO00(10)-Pad78)") (class "Default")
      (node (ref "MCU") (pin "78") (pinfunction "P10/D8/IIO00(10)_78") (pintype "bidirectional"))
    )
    (net (code "220") (name "unconnected-(MCU-P11{slash}D9{slash}IIO01(11)-Pad77)") (class "Default")
      (node (ref "MCU") (pin "77") (pinfunction "P11/D9/IIO01(11)_77") (pintype "bidirectional"))
    )
    (net (code "221") (name "unconnected-(MCU-P31{slash}A9{slash}[A9{slash}D9]-Pad59)") (class "Default")
      (node (ref "MCU") (pin "59") (pinfunction "P31/A9/[A9/D9]_59") (pintype "bidirectional"))
    )
    (net (code "222") (name "unconnected-(MCU-P74{slash}TA2OUT{slash}W{slash}CLK8-Pad24)") (class "Default")
      (node (ref "MCU") (pin "24") (pinfunction "P74/TA2OUT/W/CLK8_24") (pintype "bidirectional"))
    )
    (net (code "223") (name "unconnected-(MCU-P81{slash}TA4IN{slash}U{slash}CTS5-Pad19)") (class "Default")
      (node (ref "MCU") (pin "19") (pinfunction "P81/TA4IN/U/CTS5_19") (pintype "bidirectional"))
    )
    (net (code "224") (name "unconnected-(MCU-P91-Pad4)") (class "Default")
      (node (ref "MCU") (pin "4") (pinfunction "P91_4") (pintype "bidirectional"))
    )
    (net (code "225") (name "unconnected-(MCU-P93{slash}DA0{slash}TB3IN-Pad2)") (class "Default")
      (node (ref "MCU") (pin "2") (pinfunction "P93/DA0/TB3IN_2") (pintype "bidirectional"))
    )
    (net (code "226") (name "unconnected-(MCU-P104{slash}AN04{slash}KL0-Pad90)") (class "Default")
      (node (ref "MCU") (pin "90") (pinfunction "P104/AN04/KL0_90") (pintype "bidirectional"))
    )
    (net (code "227") (name "unconnected-(MCU-P105{slash}AN05{slash}KL1-Pad89)") (class "Default")
      (node (ref "MCU") (pin "89") (pinfunction "P105/AN05/KL1_89") (pintype "bidirectional"))
    )
    (net (code "228") (name "unconnected-(MCU-P106{slash}AN06{slash}KL2-Pad88)") (class "Default")
      (node (ref "MCU") (pin "88") (pinfunction "P106/AN06/KL2_88") (pintype "bidirectional"))
    )
    (net (code "229") (name "unconnected-(MCU-P107{slash}AN07{slash}KL3-Pad87)") (class "Default")
      (node (ref "MCU") (pin "87") (pinfunction "P107/AN07/KL3_87") (pintype "bidirectional"))
    )
    (net (code "230") (name "unconnected-(U$5-INT2-Pad9)") (class "Default")
      (node (ref "U$5") (pin "9") (pinfunction "INT2_9") (pintype "bidirectional"))
    )
    (net (code "231") (name "unconnected-(U1-A7-Pad8)") (class "Default")
      (node (ref "U1") (pin "8") (pinfunction "A7_8") (pintype "bidirectional"))
    )
    (net (code "232") (name "unconnected-(U1-A8-Pad9)") (class "Default")
      (node (ref "U1") (pin "9") (pinfunction "A8_9") (pintype "bidirectional"))
    )
    (net (code "233") (name "unconnected-(U1-B7-Pad13)") (class "Default")
      (node (ref "U1") (pin "13") (pinfunction "B7_13") (pintype "bidirectional"))
    )
    (net (code "234") (name "unconnected-(U1-B8-Pad12)") (class "Default")
      (node (ref "U1") (pin "12") (pinfunction "B8_12") (pintype "bidirectional"))
    )
  )
)
